# DiscoRap_V11.net
KiCad netlist of a schematic drawn in EAGLE
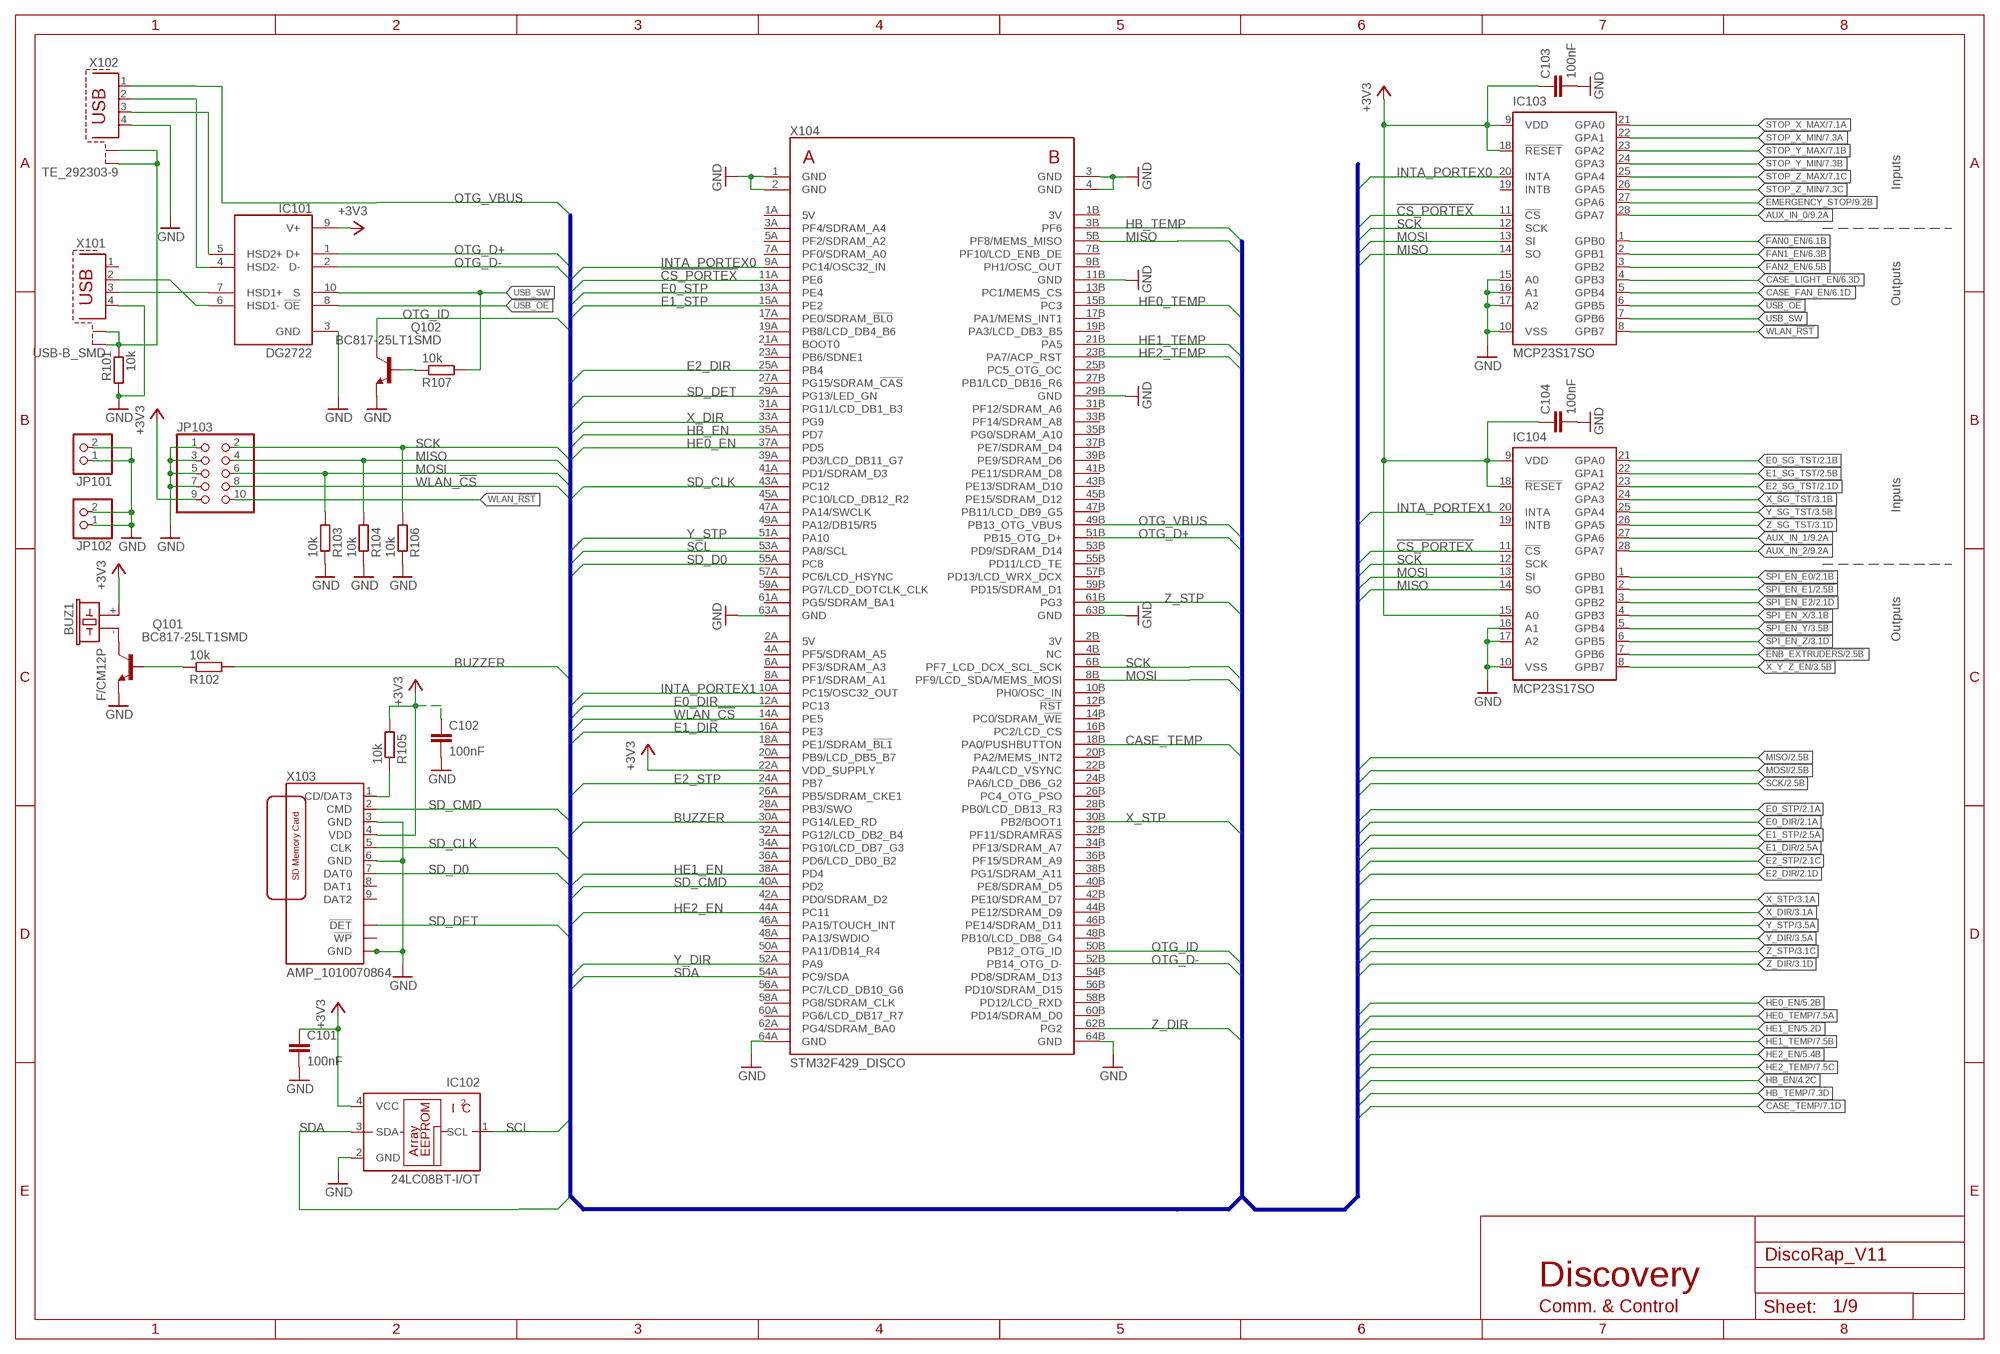
[diagram p0: schematic, sheet 1]
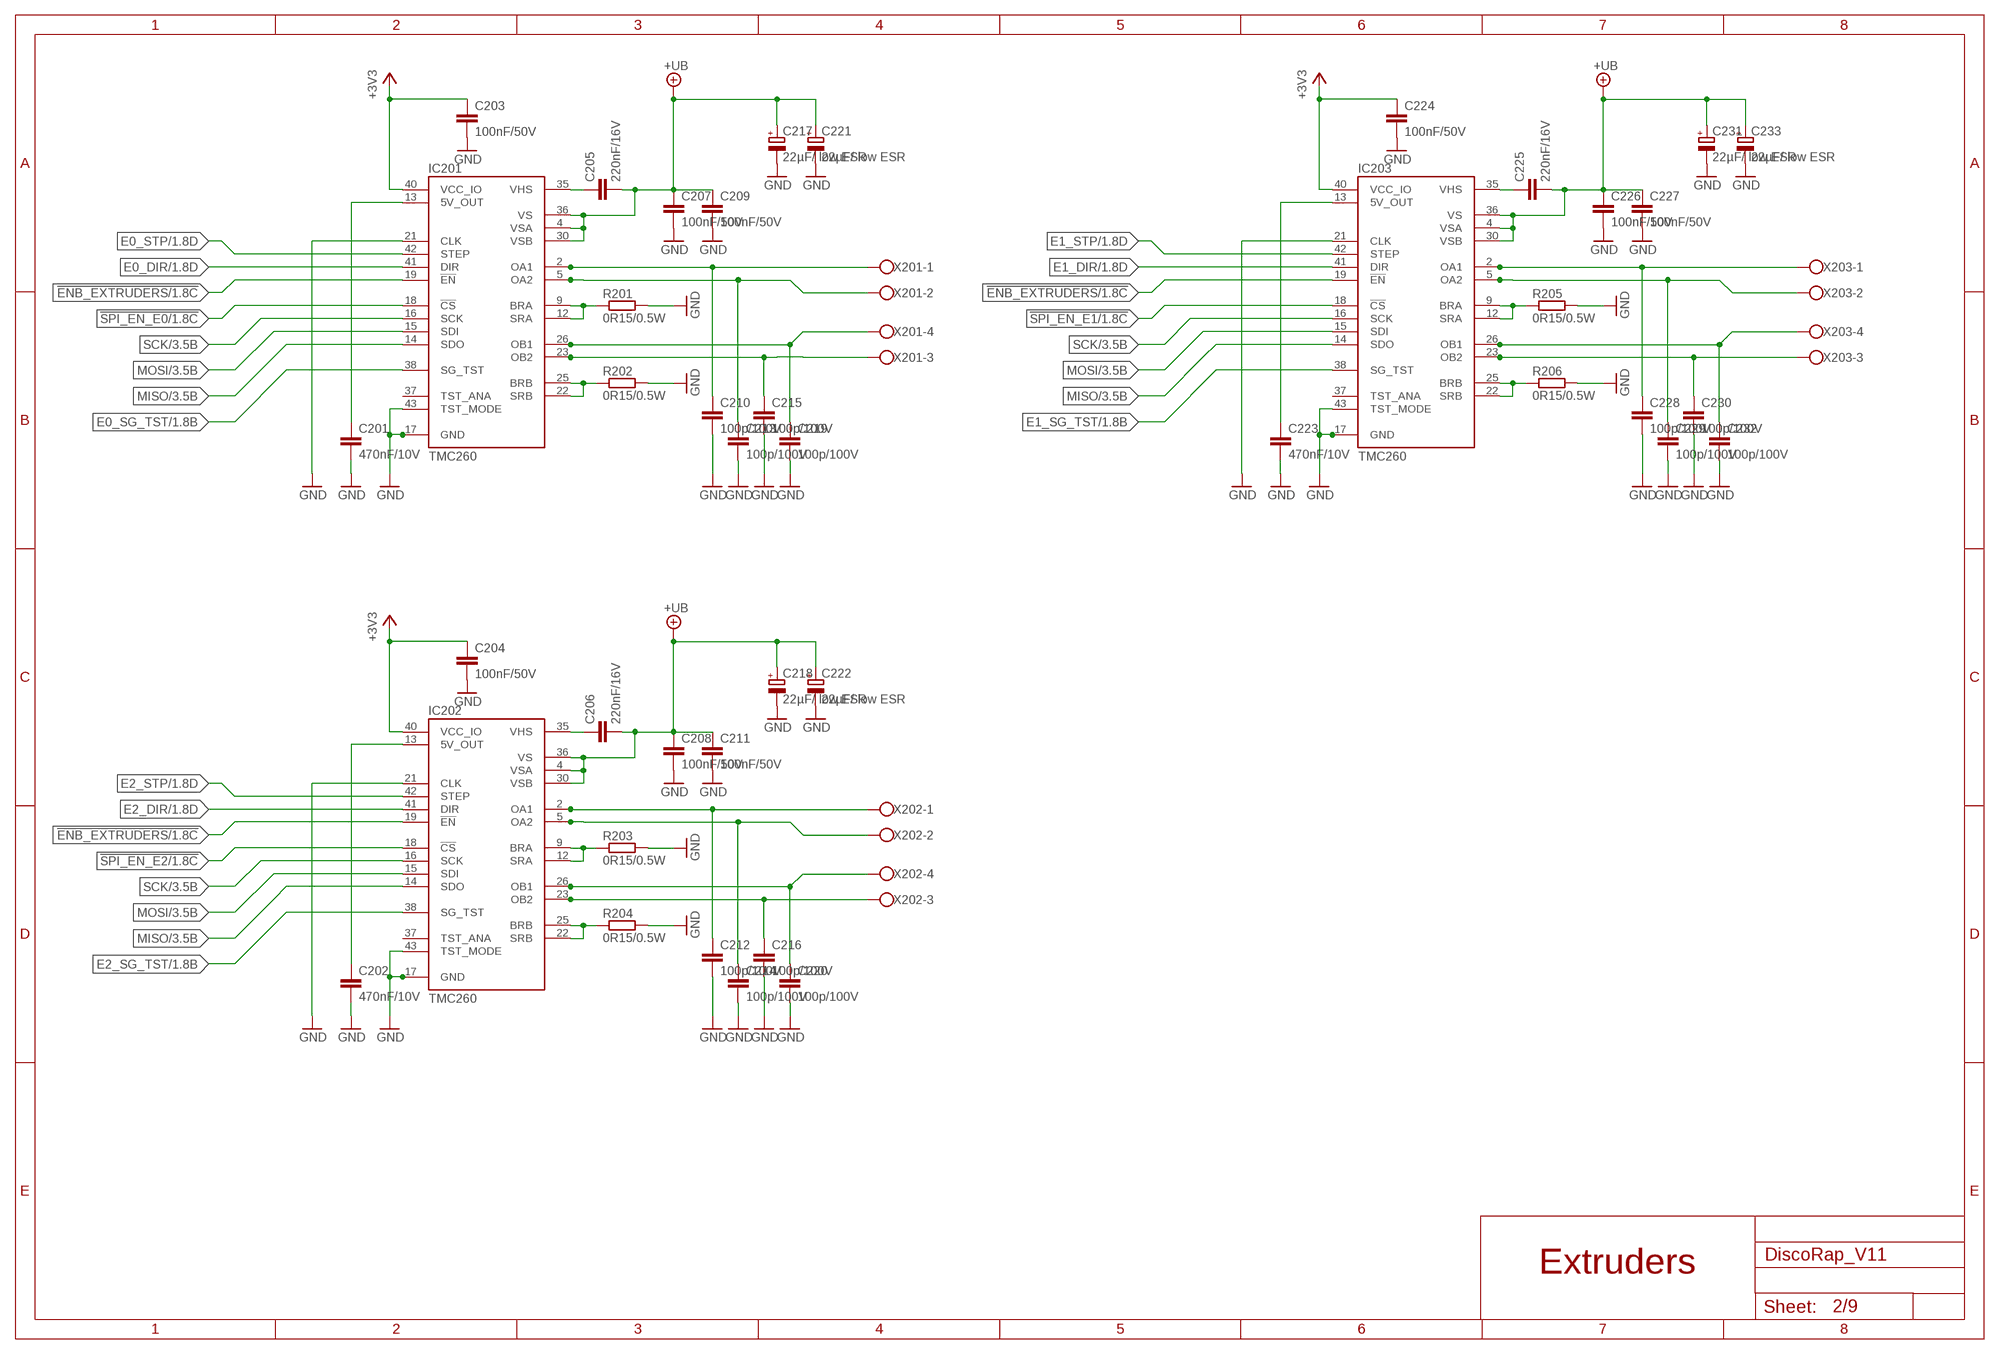
[diagram p1: schematic, sheet 2]
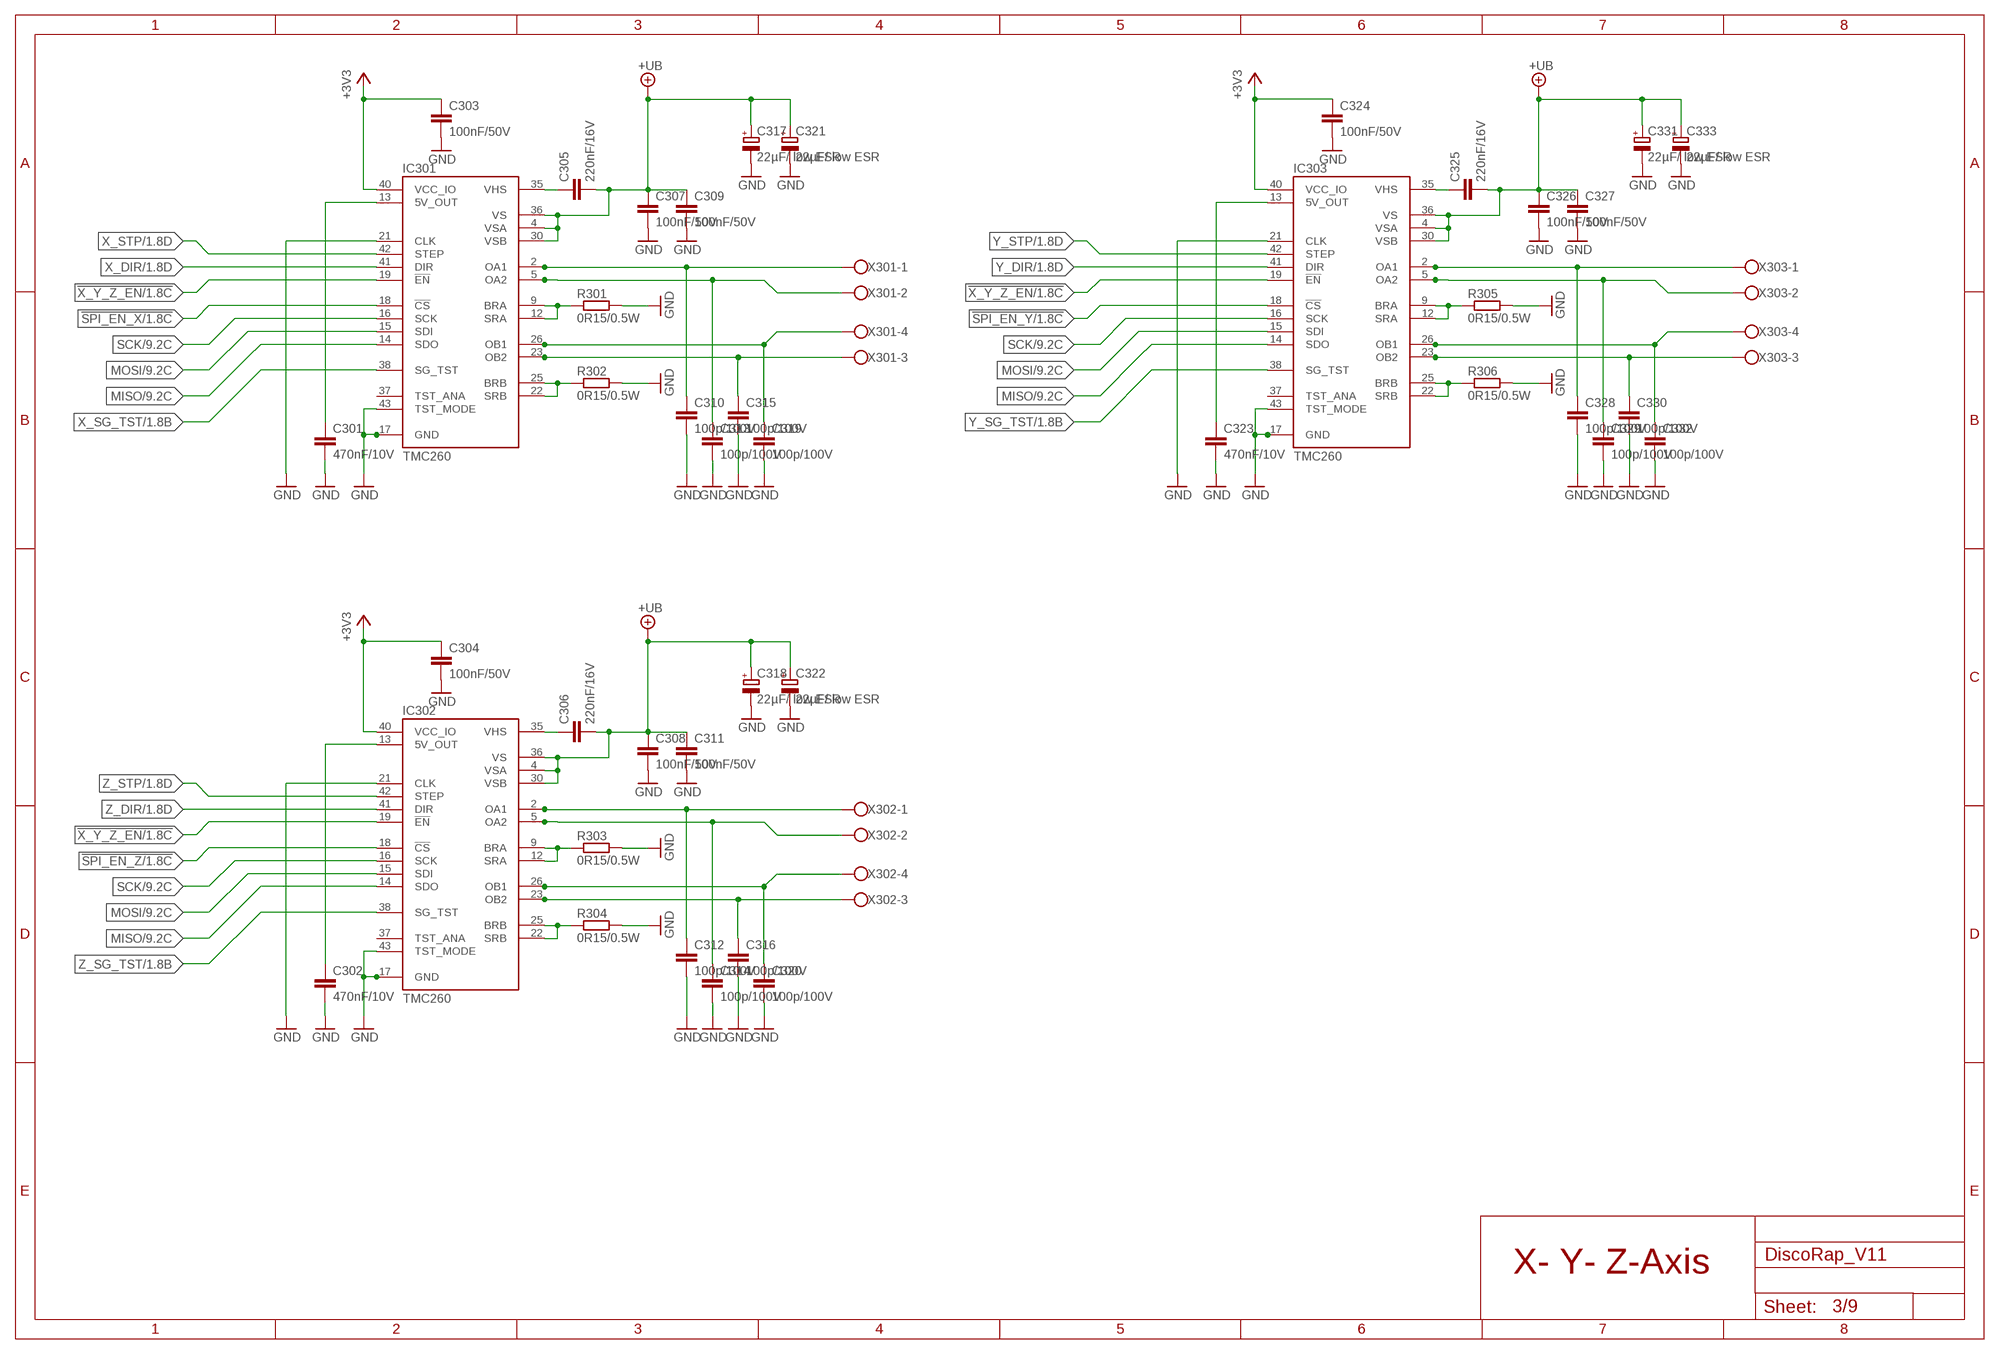
[diagram p2: schematic, sheet 3]
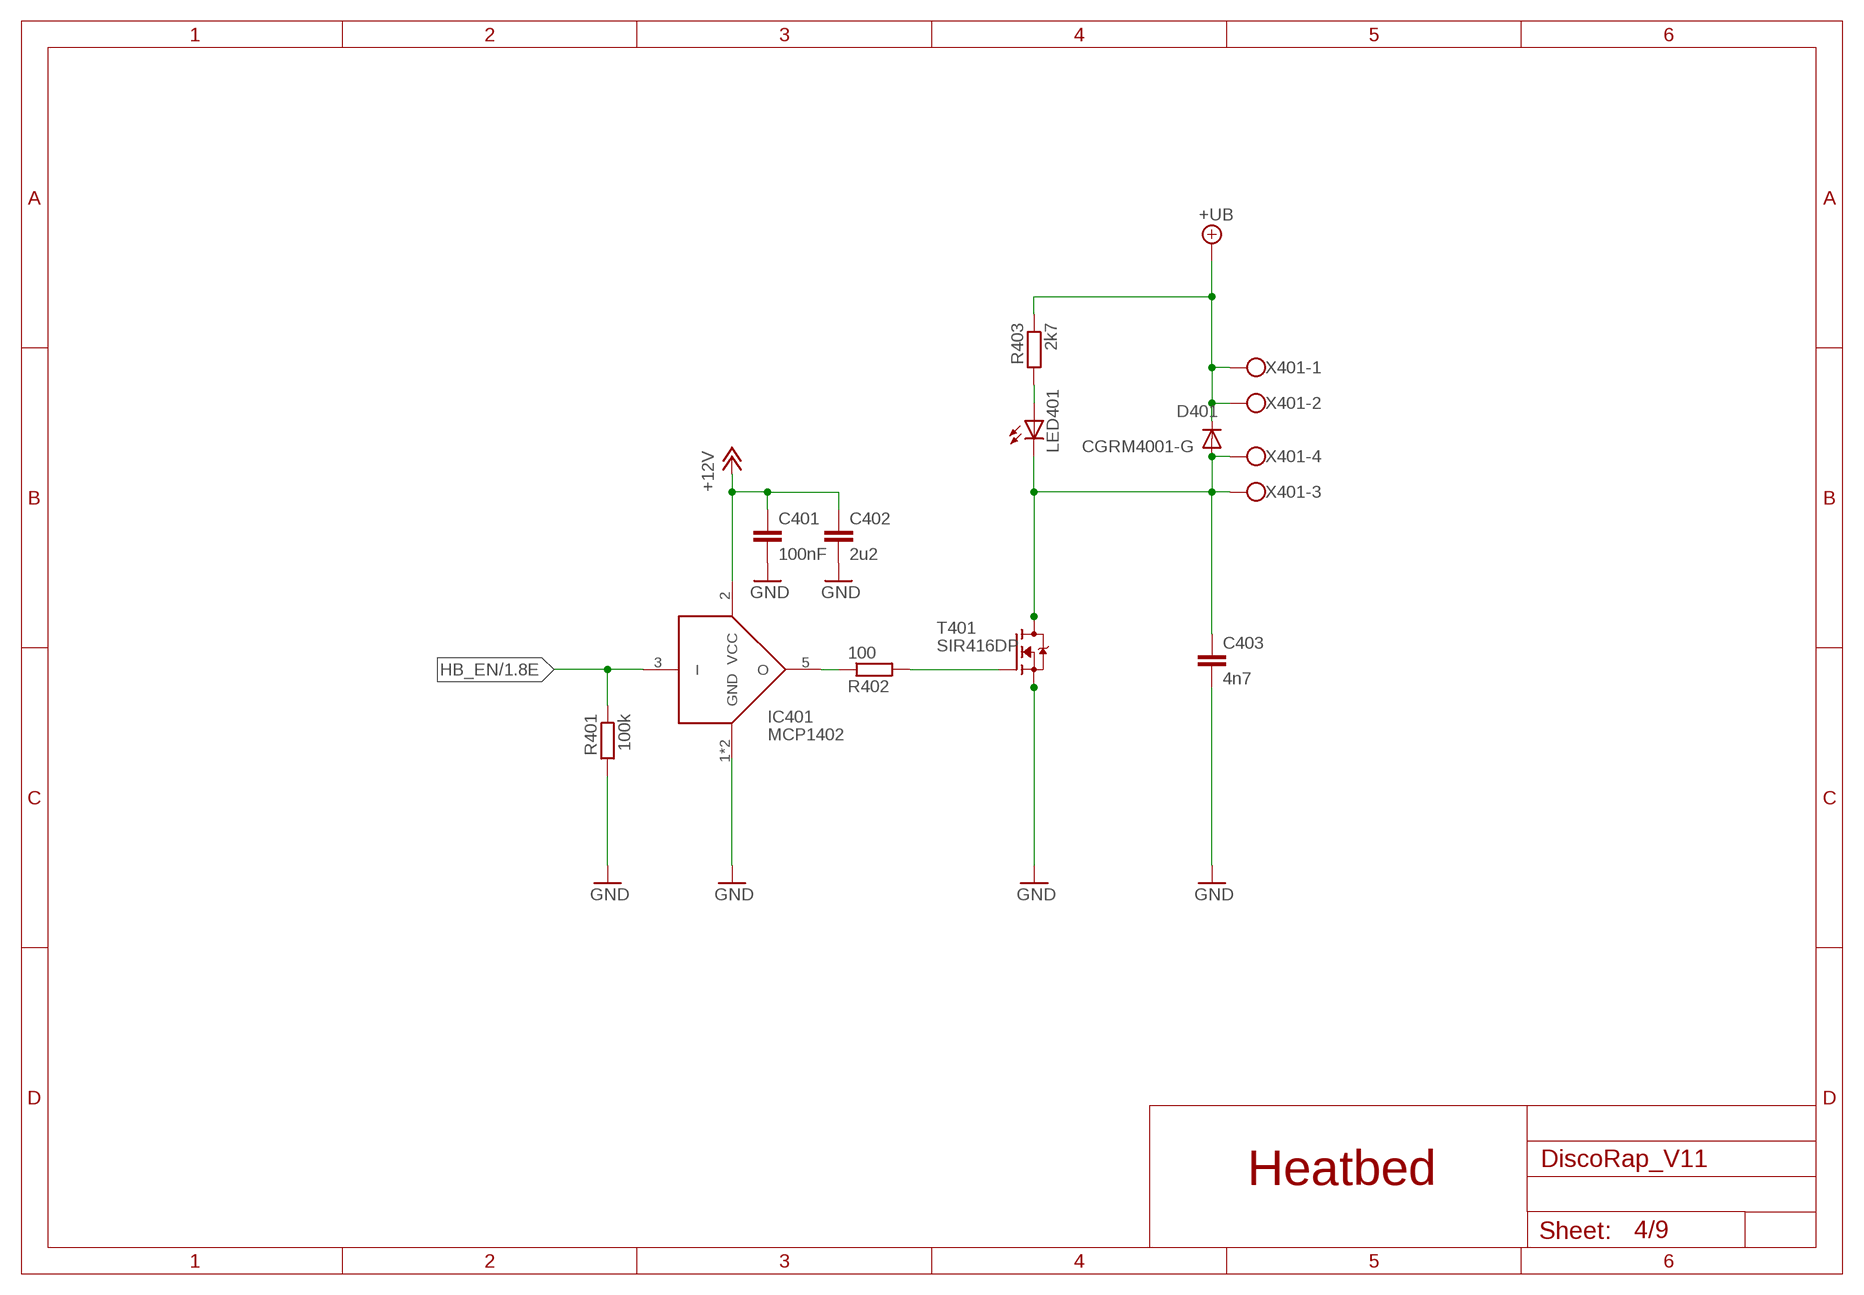
[diagram p3: schematic, sheet 4]
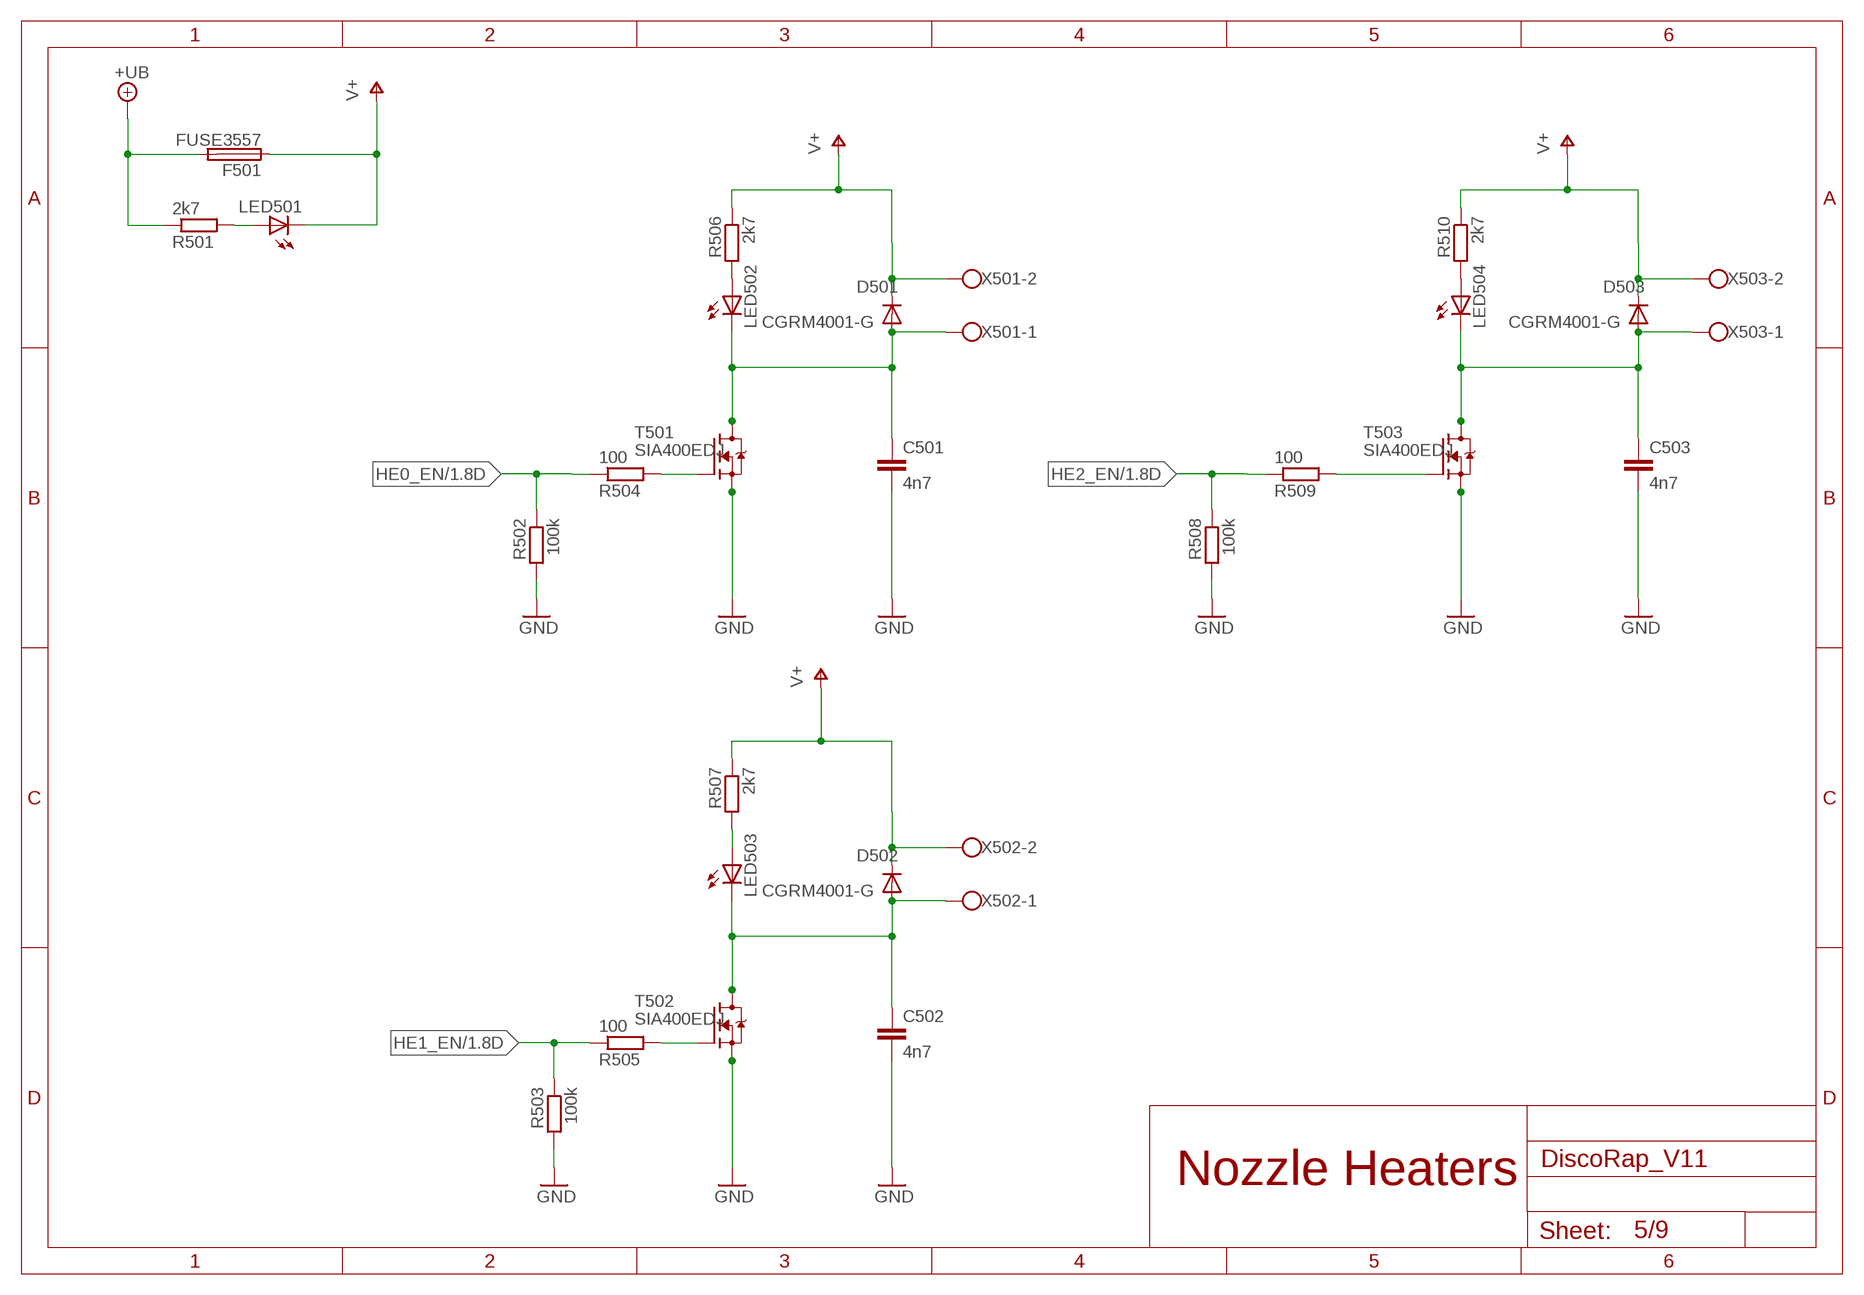
[diagram p4: schematic, sheet 5]
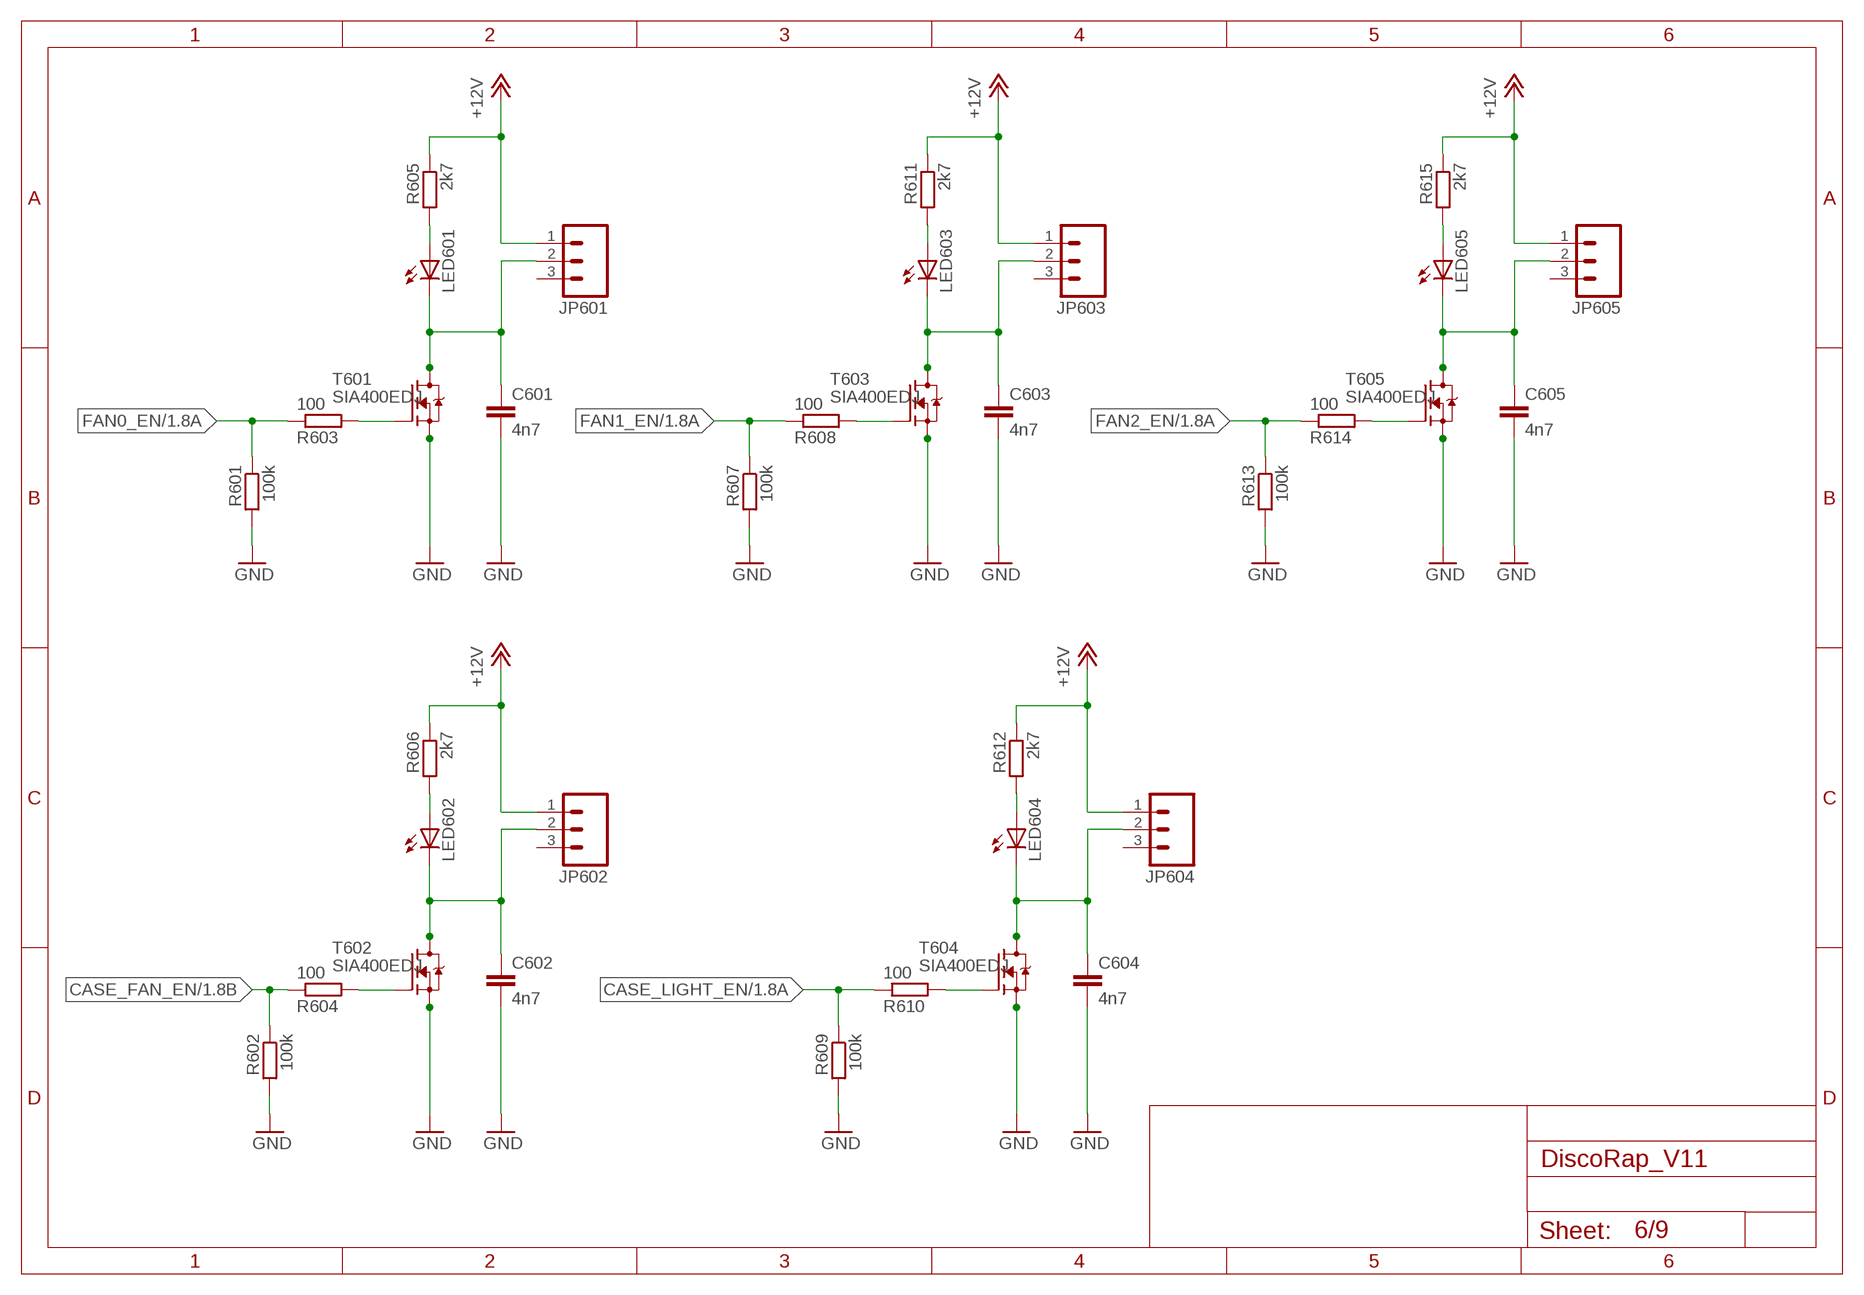
[diagram p5: schematic, sheet 6]
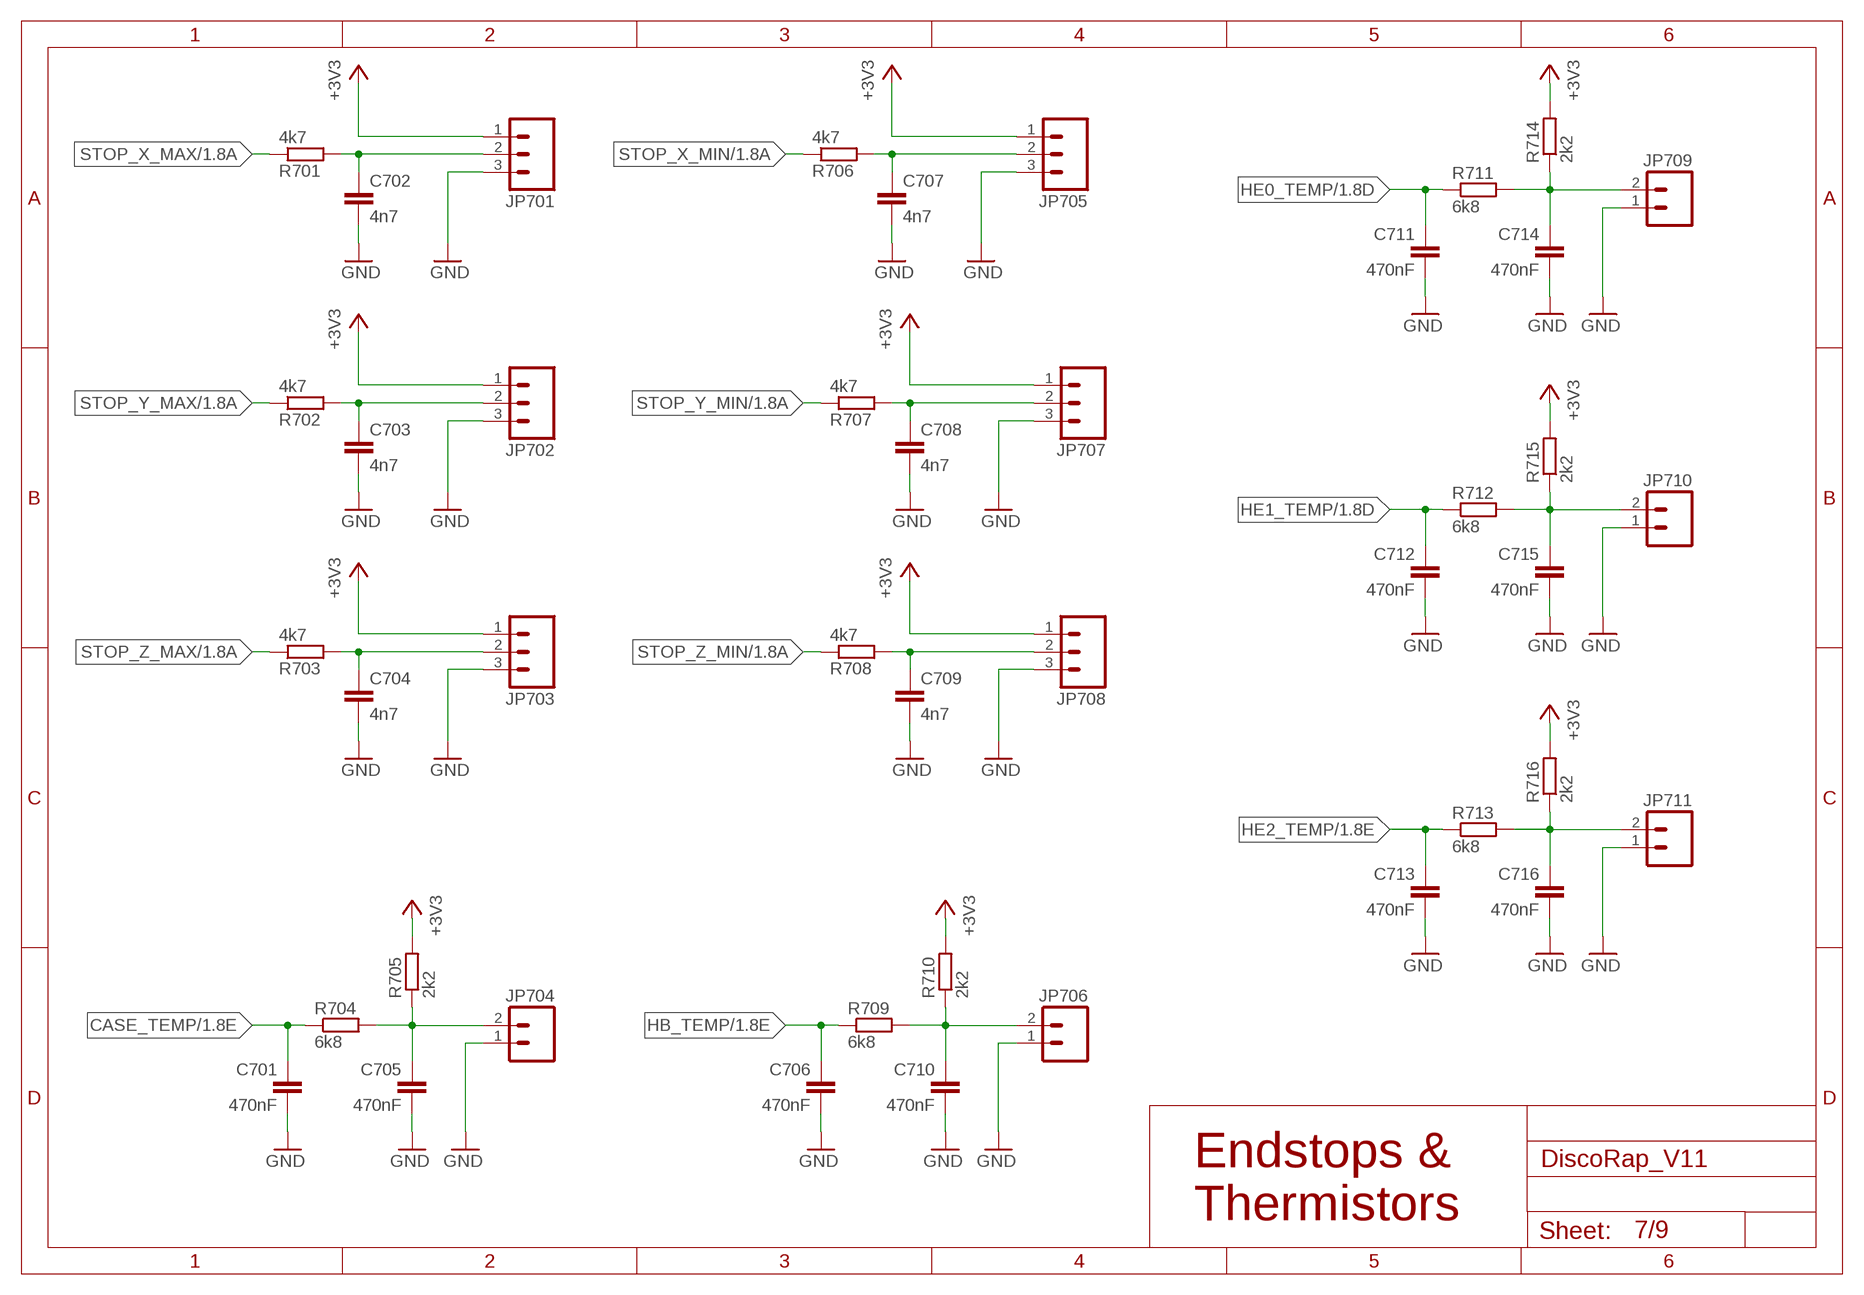
[diagram p6: schematic, sheet 7]
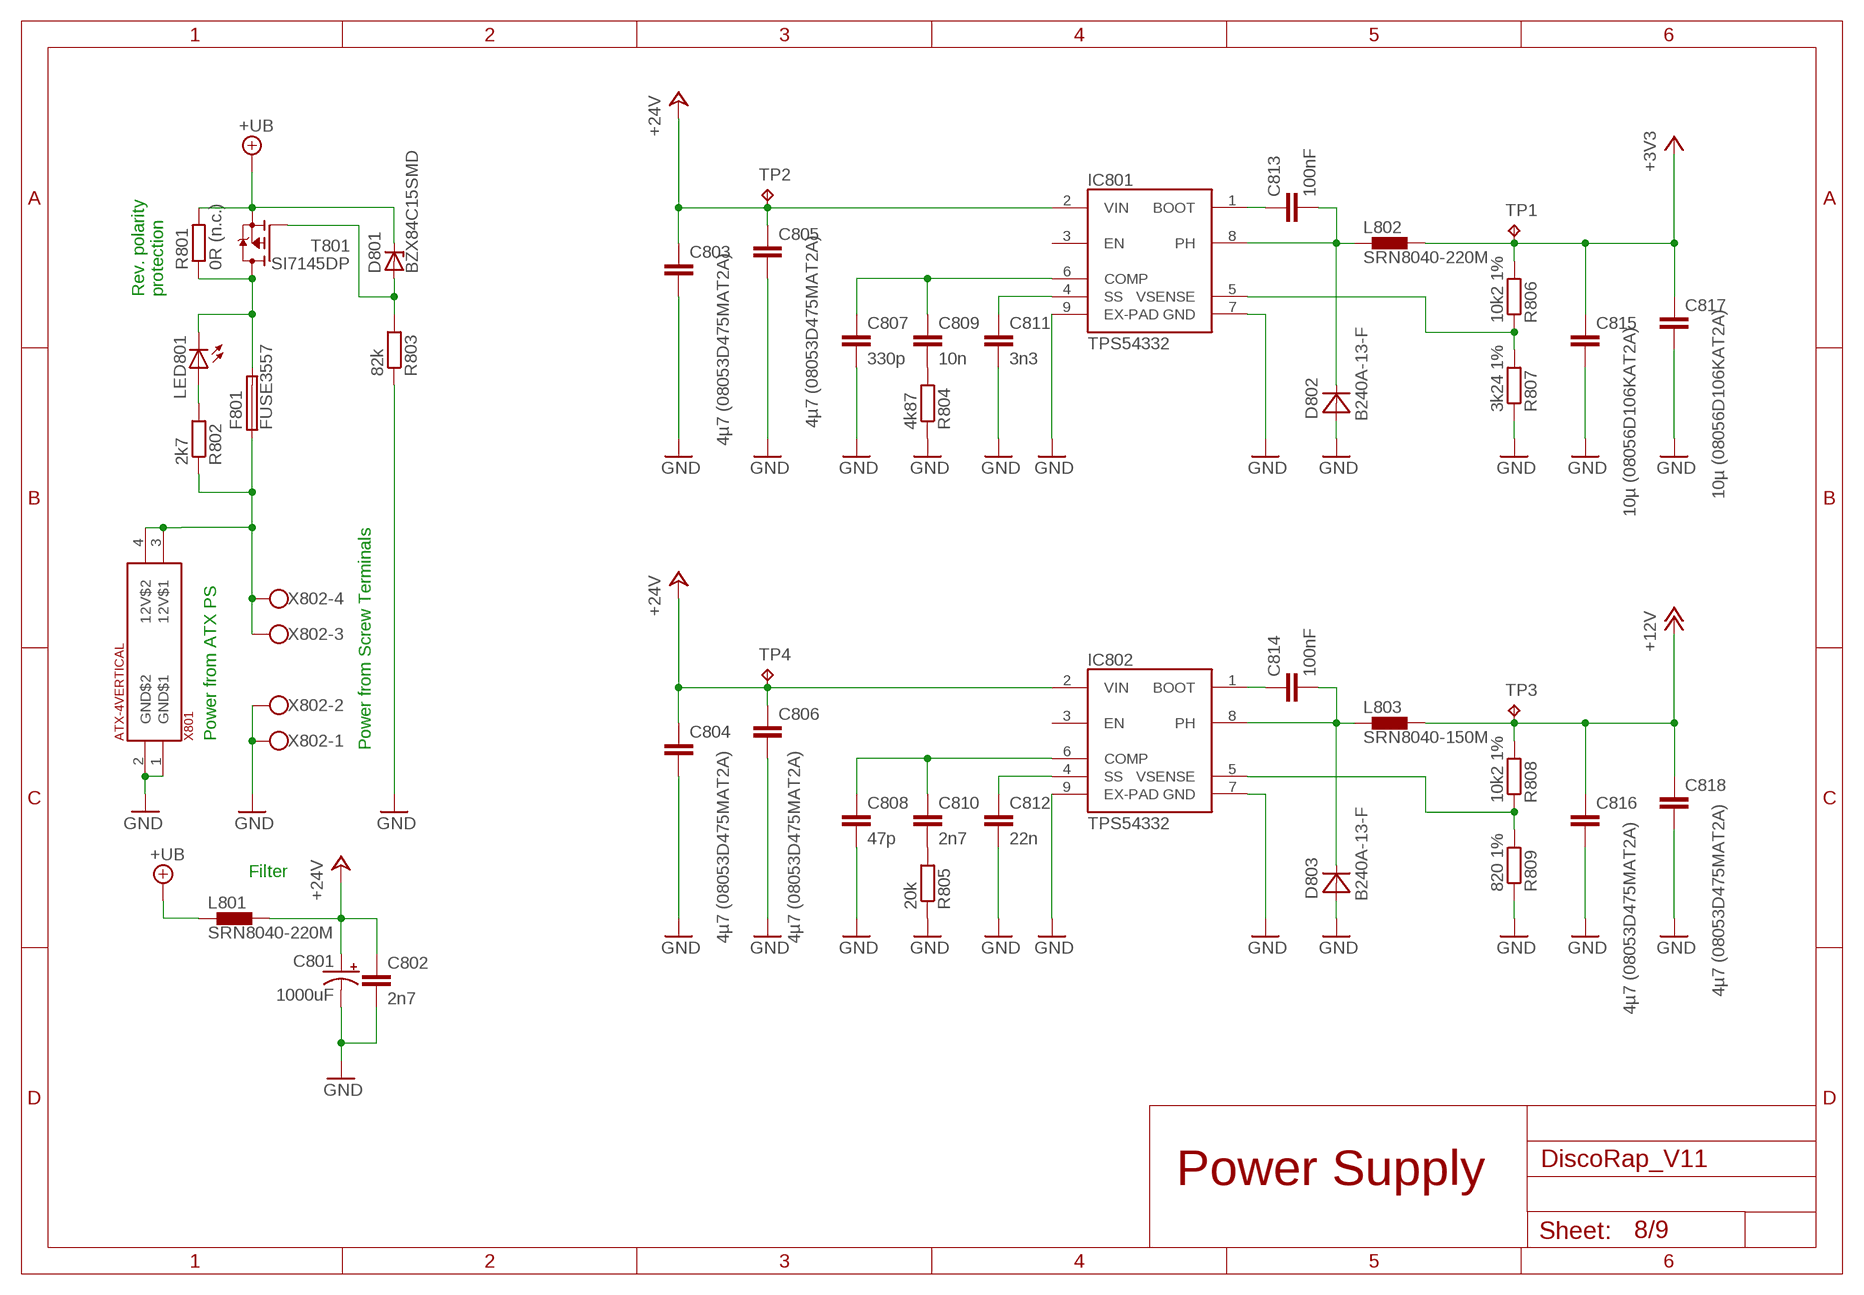
[diagram p7: schematic, sheet 8]
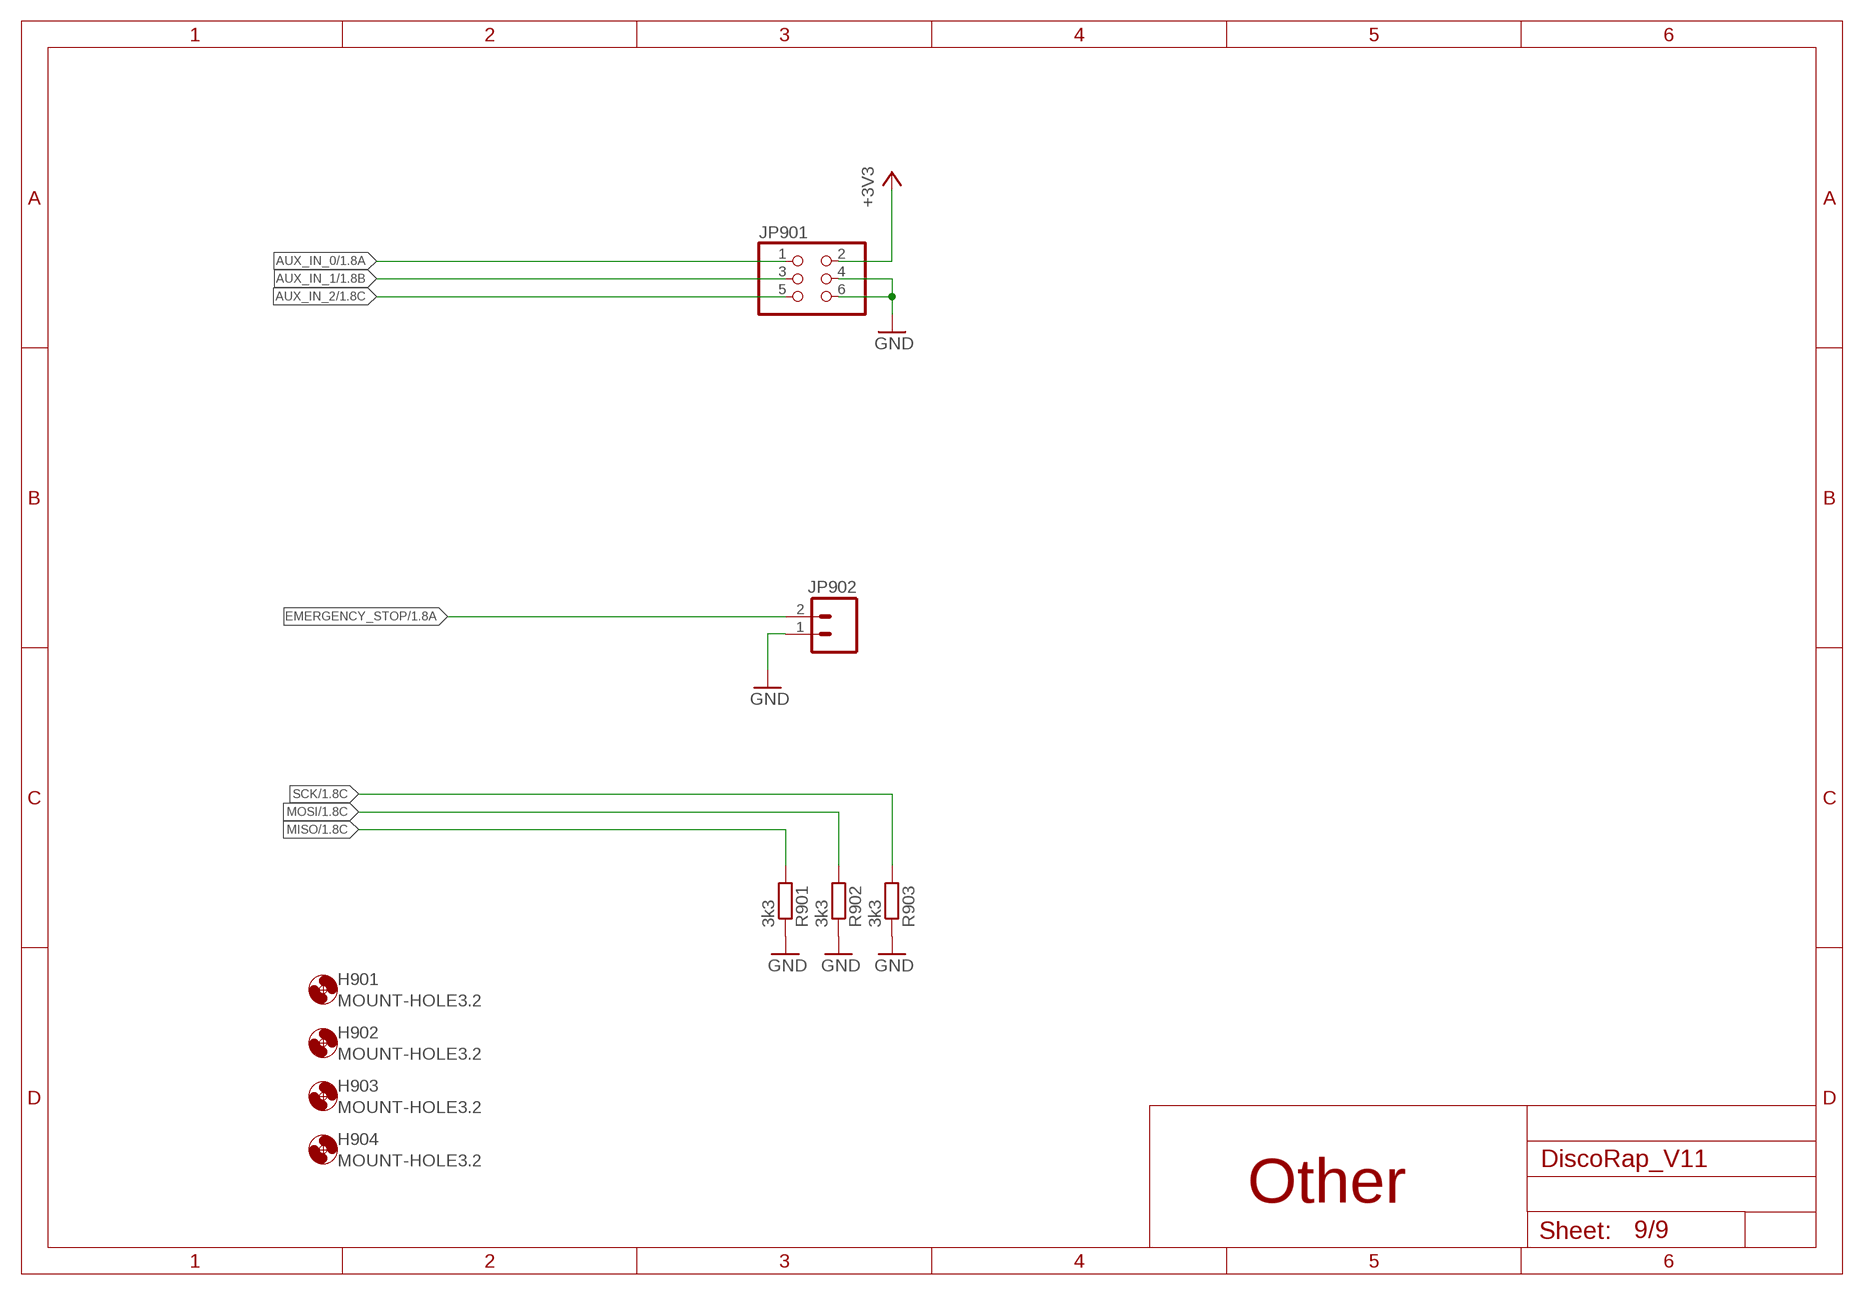
[diagram p8: schematic, sheet 9]

(export (version "E")
  (design (tool "Eeschema 10.0.6"))
  (components
    (comp (ref "H901")
      (value "MOUNT-HOLE3.2")
      (footprint "eagle-import:3,2")
      (libsource (lib "eagle-import") (part "MOUNT-HOLE3.2"))
    )
    (comp (ref "H902")
      (value "MOUNT-HOLE3.2")
      (footprint "eagle-import:3,2")
      (libsource (lib "eagle-import") (part "MOUNT-HOLE3.2"))
    )
    (comp (ref "H903")
      (value "MOUNT-HOLE3.2")
      (footprint "eagle-import:3,2")
      (libsource (lib "eagle-import") (part "MOUNT-HOLE3.2"))
    )
    (comp (ref "H904")
      (value "MOUNT-HOLE3.2")
      (footprint "eagle-import:3,2")
      (libsource (lib "eagle-import") (part "MOUNT-HOLE3.2"))
    )
    (comp (ref "JP901")
      (value "PINHD-2X3")
      (footprint "eagle-import:2X03")
      (libsource (lib "eagle-import") (part "PINHD-2X3"))
    )
    (comp (ref "JP902")
      (value "M02POLAR")
      (footprint "eagle-import:MOLEX-1X2")
      (libsource (lib "eagle-import") (part "M02POLAR"))
    )
    (comp (ref "R901")
      (value "3k3")
      (footprint "eagle-import:0805")
      (libsource (lib "eagle-import") (part "R-EU0805"))
    )
    (comp (ref "R902")
      (value "3k3")
      (footprint "eagle-import:0805")
      (libsource (lib "eagle-import") (part "R-EU0805"))
    )
    (comp (ref "R903")
      (value "3k3")
      (footprint "eagle-import:0805")
      (libsource (lib "eagle-import") (part "R-EU0805"))
    )
    (comp (ref "C301")
      (value "470nF/10V")
      (footprint "eagle-import:0805")
      (libsource (lib "eagle-import") (part "C-EU0805"))
    )
    (comp (ref "C302")
      (value "470nF/10V")
      (footprint "eagle-import:0805")
      (libsource (lib "eagle-import") (part "C-EU0805"))
    )
    (comp (ref "C303")
      (value "100nF/50V")
      (footprint "eagle-import:0805")
      (libsource (lib "eagle-import") (part "C-EU0805"))
    )
    (comp (ref "C304")
      (value "100nF/50V")
      (footprint "eagle-import:0805")
      (libsource (lib "eagle-import") (part "C-EU0805"))
    )
    (comp (ref "C305")
      (value "220nF/16V")
      (footprint "eagle-import:0805")
      (libsource (lib "eagle-import") (part "C-EU0805"))
    )
    (comp (ref "C306")
      (value "220nF/16V")
      (footprint "eagle-import:0805")
      (libsource (lib "eagle-import") (part "C-EU0805"))
    )
    (comp (ref "C307")
      (value "100nF/50V")
      (footprint "eagle-import:0805")
      (libsource (lib "eagle-import") (part "C-EU0805"))
    )
    (comp (ref "C308")
      (value "100nF/50V")
      (footprint "eagle-import:0805")
      (libsource (lib "eagle-import") (part "C-EU0805"))
    )
    (comp (ref "C309")
      (value "100nF/50V")
      (footprint "eagle-import:0805")
      (libsource (lib "eagle-import") (part "C-EU0805"))
    )
    (comp (ref "C310")
      (value "100p/100V")
      (footprint "eagle-import:0805")
      (libsource (lib "eagle-import") (part "C-EU0805"))
    )
    (comp (ref "C311")
      (value "100nF/50V")
      (footprint "eagle-import:0805")
      (libsource (lib "eagle-import") (part "C-EU0805"))
    )
    (comp (ref "C312")
      (value "100p/100V")
      (footprint "eagle-import:0805")
      (libsource (lib "eagle-import") (part "C-EU0805"))
    )
    (comp (ref "C313")
      (value "100p/100V")
      (footprint "eagle-import:0805")
      (libsource (lib "eagle-import") (part "C-EU0805"))
    )
    (comp (ref "C314")
      (value "100p/100V")
      (footprint "eagle-import:0805")
      (libsource (lib "eagle-import") (part "C-EU0805"))
    )
    (comp (ref "C315")
      (value "100p/100V")
      (footprint "eagle-import:0805")
      (libsource (lib "eagle-import") (part "C-EU0805"))
    )
    (comp (ref "C316")
      (value "100p/100V")
      (footprint "eagle-import:0805")
      (libsource (lib "eagle-import") (part "C-EU0805"))
    )
    (comp (ref "C317")
      (value "22µF/ low ESR")
      (footprint "eagle-import:SANYO-OSCON_SMD_B6")
      (libsource (lib "eagle-import") (part "CPOL-EUSANYO_SMD_B6"))
    )
    (comp (ref "C318")
      (value "22µF/ low ESR")
      (footprint "eagle-import:SANYO-OSCON_SMD_B6")
      (libsource (lib "eagle-import") (part "CPOL-EUSANYO_SMD_B6"))
    )
    (comp (ref "C319")
      (value "100p/100V")
      (footprint "eagle-import:0805")
      (libsource (lib "eagle-import") (part "C-EU0805"))
    )
    (comp (ref "C320")
      (value "100p/100V")
      (footprint "eagle-import:0805")
      (libsource (lib "eagle-import") (part "C-EU0805"))
    )
    (comp (ref "C321")
      (value "22µF/ low ESR")
      (footprint "eagle-import:SANYO-OSCON_SMD_B6")
      (libsource (lib "eagle-import") (part "CPOL-EUSANYO_SMD_B6"))
    )
    (comp (ref "C322")
      (value "22µF/ low ESR")
      (footprint "eagle-import:SANYO-OSCON_SMD_B6")
      (libsource (lib "eagle-import") (part "CPOL-EUSANYO_SMD_B6"))
    )
    (comp (ref "C323")
      (value "470nF/10V")
      (footprint "eagle-import:0805")
      (libsource (lib "eagle-import") (part "C-EU0805"))
    )
    (comp (ref "C324")
      (value "100nF/50V")
      (footprint "eagle-import:0805")
      (libsource (lib "eagle-import") (part "C-EU0805"))
    )
    (comp (ref "C325")
      (value "220nF/16V")
      (footprint "eagle-import:0805")
      (libsource (lib "eagle-import") (part "C-EU0805"))
    )
    (comp (ref "C326")
      (value "100nF/50V")
      (footprint "eagle-import:0805")
      (libsource (lib "eagle-import") (part "C-EU0805"))
    )
    (comp (ref "C327")
      (value "100nF/50V")
      (footprint "eagle-import:0805")
      (libsource (lib "eagle-import") (part "C-EU0805"))
    )
    (comp (ref "C328")
      (value "100p/100V")
      (footprint "eagle-import:0805")
      (libsource (lib "eagle-import") (part "C-EU0805"))
    )
    (comp (ref "C329")
      (value "100p/100V")
      (footprint "eagle-import:0805")
      (libsource (lib "eagle-import") (part "C-EU0805"))
    )
    (comp (ref "C330")
      (value "100p/100V")
      (footprint "eagle-import:0805")
      (libsource (lib "eagle-import") (part "C-EU0805"))
    )
    (comp (ref "C331")
      (value "22µF/ low ESR")
      (footprint "eagle-import:SANYO-OSCON_SMD_B6")
      (libsource (lib "eagle-import") (part "CPOL-EUSANYO_SMD_B6"))
    )
    (comp (ref "C332")
      (value "100p/100V")
      (footprint "eagle-import:0805")
      (libsource (lib "eagle-import") (part "C-EU0805"))
    )
    (comp (ref "C333")
      (value "22µF/ low ESR")
      (footprint "eagle-import:SANYO-OSCON_SMD_B6")
      (libsource (lib "eagle-import") (part "CPOL-EUSANYO_SMD_B6"))
    )
    (comp (ref "IC301")
      (value "TMC260")
      (footprint "eagle-import:SQFP-S-10X10-44")
      (libsource (lib "eagle-import") (part "TMC260"))
    )
    (comp (ref "IC302")
      (value "TMC260")
      (footprint "eagle-import:SQFP-S-10X10-44")
      (libsource (lib "eagle-import") (part "TMC260"))
    )
    (comp (ref "IC303")
      (value "TMC260")
      (footprint "eagle-import:SQFP-S-10X10-44")
      (libsource (lib "eagle-import") (part "TMC260"))
    )
    (comp (ref "R301")
      (value "0R15/0.5W")
      (footprint "eagle-import:R1206")
      (libsource (lib "eagle-import") (part "R-EU_R1206"))
    )
    (comp (ref "R302")
      (value "0R15/0.5W")
      (footprint "eagle-import:R1206")
      (libsource (lib "eagle-import") (part "R-EU_R1206"))
    )
    (comp (ref "R303")
      (value "0R15/0.5W")
      (footprint "eagle-import:R1206")
      (libsource (lib "eagle-import") (part "R-EU_R1206"))
    )
    (comp (ref "R304")
      (value "0R15/0.5W")
      (footprint "eagle-import:R1206")
      (libsource (lib "eagle-import") (part "R-EU_R1206"))
    )
    (comp (ref "R305")
      (value "0R15/0.5W")
      (footprint "eagle-import:R1206")
      (libsource (lib "eagle-import") (part "R-EU_R1206"))
    )
    (comp (ref "R306")
      (value "0R15/0.5W")
      (footprint "eagle-import:R1206")
      (libsource (lib "eagle-import") (part "R-EU_R1206"))
    )
    (comp (ref "X301")
      (value "W237-4")
      (footprint "eagle-import:W237-4")
      (libsource (lib "eagle-import") (part "W237-4"))
    )
    (comp (ref "X302")
      (value "W237-4")
      (footprint "eagle-import:W237-4")
      (libsource (lib "eagle-import") (part "W237-4"))
    )
    (comp (ref "X303")
      (value "W237-4")
      (footprint "eagle-import:W237-4")
      (libsource (lib "eagle-import") (part "W237-4"))
    )
    (comp (ref "C701")
      (value "470nF")
      (footprint "eagle-import:0805")
      (libsource (lib "eagle-import") (part "C-EU0805"))
    )
    (comp (ref "C702")
      (value "4n7")
      (footprint "eagle-import:0805")
      (libsource (lib "eagle-import") (part "C-EU0805"))
    )
    (comp (ref "C703")
      (value "4n7")
      (footprint "eagle-import:0805")
      (libsource (lib "eagle-import") (part "C-EU0805"))
    )
    (comp (ref "C704")
      (value "4n7")
      (footprint "eagle-import:0805")
      (libsource (lib "eagle-import") (part "C-EU0805"))
    )
    (comp (ref "C705")
      (value "470nF")
      (footprint "eagle-import:0805")
      (libsource (lib "eagle-import") (part "C-EU0805"))
    )
    (comp (ref "C706")
      (value "470nF")
      (footprint "eagle-import:0805")
      (libsource (lib "eagle-import") (part "C-EU0805"))
    )
    (comp (ref "C707")
      (value "4n7")
      (footprint "eagle-import:0805")
      (libsource (lib "eagle-import") (part "C-EU0805"))
    )
    (comp (ref "C708")
      (value "4n7")
      (footprint "eagle-import:0805")
      (libsource (lib "eagle-import") (part "C-EU0805"))
    )
    (comp (ref "C709")
      (value "4n7")
      (footprint "eagle-import:0805")
      (libsource (lib "eagle-import") (part "C-EU0805"))
    )
    (comp (ref "C710")
      (value "470nF")
      (footprint "eagle-import:0805")
      (libsource (lib "eagle-import") (part "C-EU0805"))
    )
    (comp (ref "C711")
      (value "470nF")
      (footprint "eagle-import:0805")
      (libsource (lib "eagle-import") (part "C-EU0805"))
    )
    (comp (ref "C712")
      (value "470nF")
      (footprint "eagle-import:0805")
      (libsource (lib "eagle-import") (part "C-EU0805"))
    )
    (comp (ref "C713")
      (value "470nF")
      (footprint "eagle-import:0805")
      (libsource (lib "eagle-import") (part "C-EU0805"))
    )
    (comp (ref "C714")
      (value "470nF")
      (footprint "eagle-import:0805")
      (libsource (lib "eagle-import") (part "C-EU0805"))
    )
    (comp (ref "C715")
      (value "470nF")
      (footprint "eagle-import:0805")
      (libsource (lib "eagle-import") (part "C-EU0805"))
    )
    (comp (ref "C716")
      (value "470nF")
      (footprint "eagle-import:0805")
      (libsource (lib "eagle-import") (part "C-EU0805"))
    )
    (comp (ref "JP701")
      (value "M03POLAR")
      (footprint "eagle-import:MOLEX-1X3")
      (libsource (lib "eagle-import") (part "M03POLAR"))
    )
    (comp (ref "JP702")
      (value "M03POLAR")
      (footprint "eagle-import:MOLEX-1X3")
      (libsource (lib "eagle-import") (part "M03POLAR"))
    )
    (comp (ref "JP703")
      (value "M03POLAR")
      (footprint "eagle-import:MOLEX-1X3")
      (libsource (lib "eagle-import") (part "M03POLAR"))
    )
    (comp (ref "JP704")
      (value "M02POLAR")
      (footprint "eagle-import:MOLEX-1X2")
      (libsource (lib "eagle-import") (part "M02POLAR"))
    )
    (comp (ref "JP705")
      (value "M03POLAR")
      (footprint "eagle-import:MOLEX-1X3")
      (libsource (lib "eagle-import") (part "M03POLAR"))
    )
    (comp (ref "JP706")
      (value "M02POLAR")
      (footprint "eagle-import:MOLEX-1X2")
      (libsource (lib "eagle-import") (part "M02POLAR"))
    )
    (comp (ref "JP707")
      (value "M03POLAR")
      (footprint "eagle-import:MOLEX-1X3")
      (libsource (lib "eagle-import") (part "M03POLAR"))
    )
    (comp (ref "JP708")
      (value "M03POLAR")
      (footprint "eagle-import:MOLEX-1X3")
      (libsource (lib "eagle-import") (part "M03POLAR"))
    )
    (comp (ref "JP709")
      (value "M02POLAR")
      (footprint "eagle-import:MOLEX-1X2")
      (libsource (lib "eagle-import") (part "M02POLAR"))
    )
    (comp (ref "JP710")
      (value "M02POLAR")
      (footprint "eagle-import:MOLEX-1X2")
      (libsource (lib "eagle-import") (part "M02POLAR"))
    )
    (comp (ref "JP711")
      (value "M02POLAR")
      (footprint "eagle-import:MOLEX-1X2")
      (libsource (lib "eagle-import") (part "M02POLAR"))
    )
    (comp (ref "R701")
      (value "4k7")
      (footprint "eagle-import:0805")
      (libsource (lib "eagle-import") (part "R-EU0805"))
    )
    (comp (ref "R702")
      (value "4k7")
      (footprint "eagle-import:0805")
      (libsource (lib "eagle-import") (part "R-EU0805"))
    )
    (comp (ref "R703")
      (value "4k7")
      (footprint "eagle-import:0805")
      (libsource (lib "eagle-import") (part "R-EU0805"))
    )
    (comp (ref "R704")
      (value "6k8")
      (footprint "eagle-import:0805")
      (libsource (lib "eagle-import") (part "R-EU0805"))
    )
    (comp (ref "R705")
      (value "2k2")
      (footprint "eagle-import:0805")
      (libsource (lib "eagle-import") (part "R-EU0805"))
    )
    (comp (ref "R706")
      (value "4k7")
      (footprint "eagle-import:0805")
      (libsource (lib "eagle-import") (part "R-EU0805"))
    )
    (comp (ref "R707")
      (value "4k7")
      (footprint "eagle-import:0805")
      (libsource (lib "eagle-import") (part "R-EU0805"))
    )
    (comp (ref "R708")
      (value "4k7")
      (footprint "eagle-import:0805")
      (libsource (lib "eagle-import") (part "R-EU0805"))
    )
    (comp (ref "R709")
      (value "6k8")
      (footprint "eagle-import:0805")
      (libsource (lib "eagle-import") (part "R-EU0805"))
    )
    (comp (ref "R710")
      (value "2k2")
      (footprint "eagle-import:0805")
      (libsource (lib "eagle-import") (part "R-EU0805"))
    )
    (comp (ref "R711")
      (value "6k8")
      (footprint "eagle-import:0805")
      (libsource (lib "eagle-import") (part "R-EU0805"))
    )
    (comp (ref "R712")
      (value "6k8")
      (footprint "eagle-import:0805")
      (libsource (lib "eagle-import") (part "R-EU0805"))
    )
    (comp (ref "R713")
      (value "6k8")
      (footprint "eagle-import:0805")
      (libsource (lib "eagle-import") (part "R-EU0805"))
    )
    (comp (ref "R714")
      (value "2k2")
      (footprint "eagle-import:0805")
      (libsource (lib "eagle-import") (part "R-EU0805"))
    )
    (comp (ref "R715")
      (value "2k2")
      (footprint "eagle-import:0805")
      (libsource (lib "eagle-import") (part "R-EU0805"))
    )
    (comp (ref "R716")
      (value "2k2")
      (footprint "eagle-import:0805")
      (libsource (lib "eagle-import") (part "R-EU0805"))
    )
    (comp (ref "C401")
      (value "100nF")
      (footprint "eagle-import:0805")
      (libsource (lib "eagle-import") (part "C-EU0805"))
    )
    (comp (ref "C402")
      (value "2u2")
      (footprint "eagle-import:0805")
      (libsource (lib "eagle-import") (part "C-EU0805"))
    )
    (comp (ref "C403")
      (value "4n7")
      (footprint "eagle-import:0805")
      (libsource (lib "eagle-import") (part "C-EU0805"))
    )
    (comp (ref "D401")
      (value "CGRM4001-G")
      (footprint "eagle-import:SOD-123_MINI-SMA")
      (libsource (lib "eagle-import") (part "CGRM400-G1"))
    )
    (comp (ref "IC401")
      (value "MCP1402")
      (footprint "eagle-import:SOT23-5L")
      (libsource (lib "eagle-import") (part "MCP1402"))
    )
    (comp (ref "LED401")
      (value "LEDCHIPLED_0805")
      (footprint "eagle-import:CHIPLED_0805")
      (libsource (lib "eagle-import") (part "LEDCHIPLED_0805"))
    )
    (comp (ref "R401")
      (value "100k")
      (footprint "eagle-import:0805")
      (libsource (lib "eagle-import") (part "R-EU0805"))
    )
    (comp (ref "R402")
      (value "100")
      (footprint "eagle-import:0805")
      (libsource (lib "eagle-import") (part "R-EU0805"))
    )
    (comp (ref "R403")
      (value "2k7")
      (footprint "eagle-import:0805")
      (libsource (lib "eagle-import") (part "R-EU0805"))
    )
    (comp (ref "T401")
      (value "SIR416DP")
      (footprint "eagle-import:SO-8_POWERPACK")
      (libsource (lib "eagle-import") (part "SIR416DP"))
    )
    (comp (ref "X401")
      (value "W237-4")
      (footprint "eagle-import:W237-4")
      (libsource (lib "eagle-import") (part "W237-4"))
    )
    (comp (ref "C601")
      (value "4n7")
      (footprint "eagle-import:0805")
      (libsource (lib "eagle-import") (part "C-EU0805"))
    )
    (comp (ref "C602")
      (value "4n7")
      (footprint "eagle-import:0805")
      (libsource (lib "eagle-import") (part "C-EU0805"))
    )
    (comp (ref "C603")
      (value "4n7")
      (footprint "eagle-import:0805")
      (libsource (lib "eagle-import") (part "C-EU0805"))
    )
    (comp (ref "C604")
      (value "4n7")
      (footprint "eagle-import:0805")
      (libsource (lib "eagle-import") (part "C-EU0805"))
    )
    (comp (ref "C605")
      (value "4n7")
      (footprint "eagle-import:0805")
      (libsource (lib "eagle-import") (part "C-EU0805"))
    )
    (comp (ref "JP601")
      (value "M03POLAR")
      (footprint "eagle-import:MOLEX-1X3")
      (libsource (lib "eagle-import") (part "M03POLAR"))
    )
    (comp (ref "JP602")
      (value "M03POLAR")
      (footprint "eagle-import:MOLEX-1X3")
      (libsource (lib "eagle-import") (part "M03POLAR"))
    )
    (comp (ref "JP603")
      (value "M03POLAR")
      (footprint "eagle-import:MOLEX-1X3")
      (libsource (lib "eagle-import") (part "M03POLAR"))
    )
    (comp (ref "JP604")
      (value "M03POLAR")
      (footprint "eagle-import:MOLEX-1X3")
      (libsource (lib "eagle-import") (part "M03POLAR"))
    )
    (comp (ref "JP605")
      (value "M03POLAR")
      (footprint "eagle-import:MOLEX-1X3")
      (libsource (lib "eagle-import") (part "M03POLAR"))
    )
    (comp (ref "LED601")
      (value "LEDCHIPLED_0805")
      (footprint "eagle-import:CHIPLED_0805")
      (libsource (lib "eagle-import") (part "LEDCHIPLED_0805"))
    )
    (comp (ref "LED602")
      (value "LEDCHIPLED_0805")
      (footprint "eagle-import:CHIPLED_0805")
      (libsource (lib "eagle-import") (part "LEDCHIPLED_0805"))
    )
    (comp (ref "LED603")
      (value "LEDCHIPLED_0805")
      (footprint "eagle-import:CHIPLED_0805")
      (libsource (lib "eagle-import") (part "LEDCHIPLED_0805"))
    )
    (comp (ref "LED604")
      (value "LEDCHIPLED_0805")
      (footprint "eagle-import:CHIPLED_0805")
      (libsource (lib "eagle-import") (part "LEDCHIPLED_0805"))
    )
    (comp (ref "LED605")
      (value "LEDCHIPLED_0805")
      (footprint "eagle-import:CHIPLED_0805")
      (libsource (lib "eagle-import") (part "LEDCHIPLED_0805"))
    )
    (comp (ref "R601")
      (value "100k")
      (footprint "eagle-import:0805")
      (libsource (lib "eagle-import") (part "R-EU0805"))
    )
    (comp (ref "R602")
      (value "100k")
      (footprint "eagle-import:0805")
      (libsource (lib "eagle-import") (part "R-EU0805"))
    )
    (comp (ref "R603")
      (value "100")
      (footprint "eagle-import:0805")
      (libsource (lib "eagle-import") (part "R-EU0805"))
    )
    (comp (ref "R604")
      (value "100")
      (footprint "eagle-import:0805")
      (libsource (lib "eagle-import") (part "R-EU0805"))
    )
    (comp (ref "R605")
      (value "2k7")
      (footprint "eagle-import:0805")
      (libsource (lib "eagle-import") (part "R-EU0805"))
    )
    (comp (ref "R606")
      (value "2k7")
      (footprint "eagle-import:0805")
      (libsource (lib "eagle-import") (part "R-EU0805"))
    )
    (comp (ref "R607")
      (value "100k")
      (footprint "eagle-import:0805")
      (libsource (lib "eagle-import") (part "R-EU0805"))
    )
    (comp (ref "R608")
      (value "100")
      (footprint "eagle-import:0805")
      (libsource (lib "eagle-import") (part "R-EU0805"))
    )
    (comp (ref "R609")
      (value "100k")
      (footprint "eagle-import:0805")
      (libsource (lib "eagle-import") (part "R-EU0805"))
    )
    (comp (ref "R610")
      (value "100")
      (footprint "eagle-import:0805")
      (libsource (lib "eagle-import") (part "R-EU0805"))
    )
    (comp (ref "R611")
      (value "2k7")
      (footprint "eagle-import:0805")
      (libsource (lib "eagle-import") (part "R-EU0805"))
    )
    (comp (ref "R612")
      (value "2k7")
      (footprint "eagle-import:0805")
      (libsource (lib "eagle-import") (part "R-EU0805"))
    )
    (comp (ref "R613")
      (value "100k")
      (footprint "eagle-import:0805")
      (libsource (lib "eagle-import") (part "R-EU0805"))
    )
    (comp (ref "R614")
      (value "100")
      (footprint "eagle-import:0805")
      (libsource (lib "eagle-import") (part "R-EU0805"))
    )
    (comp (ref "R615")
      (value "2k7")
      (footprint "eagle-import:0805")
      (libsource (lib "eagle-import") (part "R-EU0805"))
    )
    (comp (ref "T601")
      (value "SIA400EDJ")
      (footprint "eagle-import:SC70-6L")
      (libsource (lib "eagle-import") (part "SIA400EDJ"))
    )
    (comp (ref "T602")
      (value "SIA400EDJ")
      (footprint "eagle-import:SC70-6L")
      (libsource (lib "eagle-import") (part "SIA400EDJ"))
    )
    (comp (ref "T603")
      (value "SIA400EDJ")
      (footprint "eagle-import:SC70-6L")
      (libsource (lib "eagle-import") (part "SIA400EDJ"))
    )
    (comp (ref "T604")
      (value "SIA400EDJ")
      (footprint "eagle-import:SC70-6L")
      (libsource (lib "eagle-import") (part "SIA400EDJ"))
    )
    (comp (ref "T605")
      (value "SIA400EDJ")
      (footprint "eagle-import:SC70-6L")
      (libsource (lib "eagle-import") (part "SIA400EDJ"))
    )
    (comp (ref "C801")
      (value "1000uF")
      (footprint "eagle-import:CPOL-RADIAL-1000UF-25V")
      (libsource (lib "eagle-import") (part "CAP_POLPTH4"))
    )
    (comp (ref "C802")
      (value "2n7")
      (footprint "eagle-import:0805")
      (libsource (lib "eagle-import") (part "C-EU0805"))
    )
    (comp (ref "C803")
      (value "4µ7 (08053D475MAT2A)")
      (footprint "eagle-import:0805")
      (libsource (lib "eagle-import") (part "C-EU0805"))
    )
    (comp (ref "C804")
      (value "4µ7 (08053D475MAT2A)")
      (footprint "eagle-import:0805")
      (libsource (lib "eagle-import") (part "C-EU0805"))
    )
    (comp (ref "C805")
      (value "4µ7 (08053D475MAT2A)")
      (footprint "eagle-import:0805")
      (libsource (lib "eagle-import") (part "C-EU0805"))
    )
    (comp (ref "C806")
      (value "4µ7 (08053D475MAT2A)")
      (footprint "eagle-import:0805")
      (libsource (lib "eagle-import") (part "C-EU0805"))
    )
    (comp (ref "C807")
      (value "330p")
      (footprint "eagle-import:0805")
      (libsource (lib "eagle-import") (part "C-EU0805"))
    )
    (comp (ref "C808")
      (value "47p")
      (footprint "eagle-import:0805")
      (libsource (lib "eagle-import") (part "C-EU0805"))
    )
    (comp (ref "C809")
      (value "10n")
      (footprint "eagle-import:0805")
      (libsource (lib "eagle-import") (part "C-EU0805"))
    )
    (comp (ref "C810")
      (value "2n7")
      (footprint "eagle-import:0805")
      (libsource (lib "eagle-import") (part "C-EU0805"))
    )
    (comp (ref "C811")
      (value "3n3")
      (footprint "eagle-import:0805")
      (libsource (lib "eagle-import") (part "C-EU0805"))
    )
    (comp (ref "C812")
      (value "22n")
      (footprint "eagle-import:0805")
      (libsource (lib "eagle-import") (part "C-EU0805"))
    )
    (comp (ref "C813")
      (value "100nF")
      (footprint "eagle-import:0805")
      (libsource (lib "eagle-import") (part "C-EU0805"))
    )
    (comp (ref "C814")
      (value "100nF")
      (footprint "eagle-import:0805")
      (libsource (lib "eagle-import") (part "C-EU0805"))
    )
    (comp (ref "C815")
      (value "10µ (08056D106KAT2A)")
      (footprint "eagle-import:0805")
      (libsource (lib "eagle-import") (part "C-EU0805"))
    )
    (comp (ref "C816")
      (value "4µ7 (08053D475MAT2A)")
      (footprint "eagle-import:0805")
      (libsource (lib "eagle-import") (part "C-EU0805"))
    )
    (comp (ref "C817")
      (value "10µ (08056D106KAT2A)")
      (footprint "eagle-import:0805")
      (libsource (lib "eagle-import") (part "C-EU0805"))
    )
    (comp (ref "C818")
      (value "4µ7 (08053D475MAT2A)")
      (footprint "eagle-import:0805")
      (libsource (lib "eagle-import") (part "C-EU0805"))
    )
    (comp (ref "D801")
      (value "BZX84C15SMD")
      (footprint "eagle-import:TO236")
      (libsource (lib "eagle-import") (part "BZX84CSMD"))
    )
    (comp (ref "D802")
      (value "B240A-13-F")
      (footprint "eagle-import:SMA")
      (libsource (lib "eagle-import") (part "MBRA340T3"))
    )
    (comp (ref "D803")
      (value "B240A-13-F")
      (footprint "eagle-import:SMA")
      (libsource (lib "eagle-import") (part "MBRA340T3"))
    )
    (comp (ref "F801")
      (value "FUSE3557")
      (footprint "eagle-import:3557")
      (libsource (lib "eagle-import") (part "FUSE3557"))
    )
    (comp (ref "IC801")
      (value "TPS54332")
      (footprint "eagle-import:PDSO-G8")
      (libsource (lib "eagle-import") (part "TPS54332"))
    )
    (comp (ref "IC802")
      (value "TPS54332")
      (footprint "eagle-import:PDSO-G8")
      (libsource (lib "eagle-import") (part "TPS54332"))
    )
    (comp (ref "L801")
      (value "SRN8040-220M")
      (footprint "eagle-import:SRN8040")
      (libsource (lib "eagle-import") (part "SRN8040"))
    )
    (comp (ref "L802")
      (value "SRN8040-220M")
      (footprint "eagle-import:SRN8040")
      (libsource (lib "eagle-import") (part "SRN8040"))
    )
    (comp (ref "L803")
      (value "SRN8040-150M")
      (footprint "eagle-import:SRN8040")
      (libsource (lib "eagle-import") (part "SRN8040"))
    )
    (comp (ref "LED801")
      (value "LEDCHIPLED_0805")
      (footprint "eagle-import:CHIPLED_0805")
      (libsource (lib "eagle-import") (part "LEDCHIPLED_0805"))
    )
    (comp (ref "R801")
      (value "0R (n.c.)")
      (footprint "eagle-import:R2512")
      (libsource (lib "eagle-import") (part "R-EU_R2512"))
    )
    (comp (ref "R802")
      (value "2k7")
      (footprint "eagle-import:0805")
      (libsource (lib "eagle-import") (part "R-EU0805"))
    )
    (comp (ref "R803")
      (value "82k")
      (footprint "eagle-import:0805")
      (libsource (lib "eagle-import") (part "R-EU0805"))
    )
    (comp (ref "R804")
      (value "4k87")
      (footprint "eagle-import:0805")
      (libsource (lib "eagle-import") (part "R-EU0805"))
    )
    (comp (ref "R805")
      (value "20k")
      (footprint "eagle-import:0805")
      (libsource (lib "eagle-import") (part "R-EU0805"))
    )
    (comp (ref "R806")
      (value "10k2 1%")
      (footprint "eagle-import:0805")
      (libsource (lib "eagle-import") (part "R-EU0805"))
    )
    (comp (ref "R807")
      (value "3k24 1%")
      (footprint "eagle-import:0805")
      (libsource (lib "eagle-import") (part "R-EU0805"))
    )
    (comp (ref "R808")
      (value "10k2 1%")
      (footprint "eagle-import:0805")
      (libsource (lib "eagle-import") (part "R-EU0805"))
    )
    (comp (ref "R809")
      (value "820 1%")
      (footprint "eagle-import:0805")
      (libsource (lib "eagle-import") (part "R-EU0805"))
    )
    (comp (ref "T801")
      (value "SI7145DP")
      (footprint "eagle-import:SO-8_POWERPACK")
      (libsource (lib "eagle-import") (part "SI7145DP"))
    )
    (comp (ref "TP1")
      (value "TPB1,27")
      (footprint "eagle-import:B1,27")
      (libsource (lib "eagle-import") (part "TPB1,27"))
    )
    (comp (ref "TP2")
      (value "TPB1,27")
      (footprint "eagle-import:B1,27")
      (libsource (lib "eagle-import") (part "TPB1,27"))
    )
    (comp (ref "TP3")
      (value "TPB1,27")
      (footprint "eagle-import:B1,27")
      (libsource (lib "eagle-import") (part "TPB1,27"))
    )
    (comp (ref "TP4")
      (value "TPB1,27")
      (footprint "eagle-import:B1,27")
      (libsource (lib "eagle-import") (part "TPB1,27"))
    )
    (comp (ref "X801")
      (value "ATX-4VERTICAL")
      (footprint "eagle-import:MINIFITJR-4-VERTICAL")
      (libsource (lib "eagle-import") (part "ATX-4VERTICAL"))
    )
    (comp (ref "X802")
      (value "W237-4")
      (footprint "eagle-import:W237-4")
      (libsource (lib "eagle-import") (part "W237-4"))
    )
    (comp (ref "BUZ1")
      (value "F/CM12P")
      (footprint "eagle-import:F_CM12P")
      (libsource (lib "eagle-import") (part "F/CM12P"))
    )
    (comp (ref "C101")
      (value "100nF")
      (footprint "eagle-import:0805")
      (libsource (lib "eagle-import") (part "C-EU0805"))
    )
    (comp (ref "C102")
      (value "100nF")
      (footprint "eagle-import:0805")
      (libsource (lib "eagle-import") (part "C-EU0805"))
    )
    (comp (ref "C103")
      (value "100nF")
      (footprint "eagle-import:0805")
      (libsource (lib "eagle-import") (part "C-EU0805"))
    )
    (comp (ref "C104")
      (value "100nF")
      (footprint "eagle-import:0805")
      (libsource (lib "eagle-import") (part "C-EU0805"))
    )
    (comp (ref "IC101")
      (value "DG2722")
      (footprint "eagle-import:MINI_QFN_10L")
      (libsource (lib "eagle-import") (part "DG2722"))
    )
    (comp (ref "IC102")
      (value "24LC08BT-I/OT")
      (footprint "eagle-import:SOT23-5L")
      (fields (field (name "MF") "MICROCHIP") (field (name "MPN") "24LC00T-I/OT"))
      (libsource (lib "eagle-import") (part "2400OTLC"))
    )
    (comp (ref "IC103")
      (value "MCP23S17SO")
      (footprint "eagle-import:SO28W")
      (fields (field (name "MF") "MICROCHIP") (field (name "MPN") "MCP23S17-E/SO"))
      (libsource (lib "eagle-import") (part "MCP23S17SO"))
    )
    (comp (ref "IC104")
      (value "MCP23S17SO")
      (footprint "eagle-import:SO28W")
      (fields (field (name "MF") "MICROCHIP") (field (name "MPN") "MCP23S17-E/SO"))
      (libsource (lib "eagle-import") (part "MCP23S17SO"))
    )
    (comp (ref "JP101")
      (value "PINHD-1X2")
      (footprint "eagle-import:1X02")
      (libsource (lib "eagle-import") (part "PINHD-1X2"))
    )
    (comp (ref "JP102")
      (value "PINHD-1X2")
      (footprint "eagle-import:1X02")
      (libsource (lib "eagle-import") (part "PINHD-1X2"))
    )
    (comp (ref "JP103")
      (value "PINHD-2X5")
      (footprint "eagle-import:2X05")
      (libsource (lib "eagle-import") (part "PINHD-2X5"))
    )
    (comp (ref "Q101")
      (value "BC817-25LT1SMD")
      (footprint "eagle-import:SOT23-BEC")
      (libsource (lib "eagle-import") (part "BC817SMD-25LT1"))
    )
    (comp (ref "Q102")
      (value "BC817-25LT1SMD")
      (footprint "eagle-import:SOT23-BEC")
      (libsource (lib "eagle-import") (part "BC817SMD-25LT1"))
    )
    (comp (ref "R101")
      (value "10k")
      (footprint "eagle-import:0805")
      (libsource (lib "eagle-import") (part "R-EU0805"))
    )
    (comp (ref "R102")
      (value "10k")
      (footprint "eagle-import:0805")
      (libsource (lib "eagle-import") (part "R-EU0805"))
    )
    (comp (ref "R103")
      (value "10k")
      (footprint "eagle-import:0805")
      (libsource (lib "eagle-import") (part "R-EU0805"))
    )
    (comp (ref "R104")
      (value "10k")
      (footprint "eagle-import:0805")
      (libsource (lib "eagle-import") (part "R-EU0805"))
    )
    (comp (ref "R105")
      (value "10k")
      (footprint "eagle-import:0805")
      (libsource (lib "eagle-import") (part "R-EU0805"))
    )
    (comp (ref "R106")
      (value "10k")
      (footprint "eagle-import:0805")
      (libsource (lib "eagle-import") (part "R-EU0805"))
    )
    (comp (ref "R107")
      (value "10k")
      (footprint "eagle-import:0805")
      (libsource (lib "eagle-import") (part "R-EU0805"))
    )
    (comp (ref "X101")
      (value "USB-B_SMD")
      (footprint "eagle-import:USB_B_SMD")
      (libsource (lib "eagle-import") (part "USB-B_SMD"))
    )
    (comp (ref "X102")
      (value "TE_292303-9")
      (footprint "eagle-import:TE_USB_A_SMD")
      (libsource (lib "eagle-import") (part "TE_292303-9"))
    )
    (comp (ref "X103")
      (value "AMP_1010070864")
      (footprint "eagle-import:AMP_1010070864")
      (libsource (lib "eagle-import") (part "AMP_1010070864"))
    )
    (comp (ref "X104")
      (value "STM32F429_DISCO")
      (footprint "eagle-import:STM429_DISCOVERY")
      (libsource (lib "eagle-import") (part "STM32F429_DISCO"))
    )
    (comp (ref "C501")
      (value "4n7")
      (footprint "eagle-import:0805")
      (libsource (lib "eagle-import") (part "C-EU0805"))
    )
    (comp (ref "C502")
      (value "4n7")
      (footprint "eagle-import:0805")
      (libsource (lib "eagle-import") (part "C-EU0805"))
    )
    (comp (ref "C503")
      (value "4n7")
      (footprint "eagle-import:0805")
      (libsource (lib "eagle-import") (part "C-EU0805"))
    )
    (comp (ref "D501")
      (value "CGRM4001-G")
      (footprint "eagle-import:SOD-123_MINI-SMA")
      (libsource (lib "eagle-import") (part "CGRM400-G1"))
    )
    (comp (ref "D502")
      (value "CGRM4001-G")
      (footprint "eagle-import:SOD-123_MINI-SMA")
      (libsource (lib "eagle-import") (part "CGRM400-G1"))
    )
    (comp (ref "D503")
      (value "CGRM4001-G")
      (footprint "eagle-import:SOD-123_MINI-SMA")
      (libsource (lib "eagle-import") (part "CGRM400-G1"))
    )
    (comp (ref "F501")
      (value "FUSE3557")
      (footprint "eagle-import:3557")
      (libsource (lib "eagle-import") (part "FUSE3557"))
    )
    (comp (ref "LED501")
      (value "LEDCHIPLED_0805")
      (footprint "eagle-import:CHIPLED_0805")
      (libsource (lib "eagle-import") (part "LEDCHIPLED_0805"))
    )
    (comp (ref "LED502")
      (value "LEDCHIPLED_0805")
      (footprint "eagle-import:CHIPLED_0805")
      (libsource (lib "eagle-import") (part "LEDCHIPLED_0805"))
    )
    (comp (ref "LED503")
      (value "LEDCHIPLED_0805")
      (footprint "eagle-import:CHIPLED_0805")
      (libsource (lib "eagle-import") (part "LEDCHIPLED_0805"))
    )
    (comp (ref "LED504")
      (value "LEDCHIPLED_0805")
      (footprint "eagle-import:CHIPLED_0805")
      (libsource (lib "eagle-import") (part "LEDCHIPLED_0805"))
    )
    (comp (ref "R501")
      (value "2k7")
      (footprint "eagle-import:0805")
      (libsource (lib "eagle-import") (part "R-EU0805"))
    )
    (comp (ref "R502")
      (value "100k")
      (footprint "eagle-import:0805")
      (libsource (lib "eagle-import") (part "R-EU0805"))
    )
    (comp (ref "R503")
      (value "100k")
      (footprint "eagle-import:0805")
      (libsource (lib "eagle-import") (part "R-EU0805"))
    )
    (comp (ref "R504")
      (value "100")
      (footprint "eagle-import:0805")
      (libsource (lib "eagle-import") (part "R-EU0805"))
    )
    (comp (ref "R505")
      (value "100")
      (footprint "eagle-import:0805")
      (libsource (lib "eagle-import") (part "R-EU0805"))
    )
    (comp (ref "R506")
      (value "2k7")
      (footprint "eagle-import:0805")
      (libsource (lib "eagle-import") (part "R-EU0805"))
    )
    (comp (ref "R507")
      (value "2k7")
      (footprint "eagle-import:0805")
      (libsource (lib "eagle-import") (part "R-EU0805"))
    )
    (comp (ref "R508")
      (value "100k")
      (footprint "eagle-import:0805")
      (libsource (lib "eagle-import") (part "R-EU0805"))
    )
    (comp (ref "R509")
      (value "100")
      (footprint "eagle-import:0805")
      (libsource (lib "eagle-import") (part "R-EU0805"))
    )
    (comp (ref "R510")
      (value "2k7")
      (footprint "eagle-import:0805")
      (libsource (lib "eagle-import") (part "R-EU0805"))
    )
    (comp (ref "T501")
      (value "SIA400EDJ")
      (footprint "eagle-import:SC70-6L")
      (libsource (lib "eagle-import") (part "SIA400EDJ"))
    )
    (comp (ref "T502")
      (value "SIA400EDJ")
      (footprint "eagle-import:SC70-6L")
      (libsource (lib "eagle-import") (part "SIA400EDJ"))
    )
    (comp (ref "T503")
      (value "SIA400EDJ")
      (footprint "eagle-import:SC70-6L")
      (libsource (lib "eagle-import") (part "SIA400EDJ"))
    )
    (comp (ref "X501")
      (value "W237-102")
      (footprint "eagle-import:W237-102")
      (fields (field (name "MPN") "237-102"))
      (libsource (lib "eagle-import") (part "W237-102"))
    )
    (comp (ref "X502")
      (value "W237-102")
      (footprint "eagle-import:W237-102")
      (fields (field (name "MPN") "237-102"))
      (libsource (lib "eagle-import") (part "W237-102"))
    )
    (comp (ref "X503")
      (value "W237-102")
      (footprint "eagle-import:W237-102")
      (fields (field (name "MPN") "237-102"))
      (libsource (lib "eagle-import") (part "W237-102"))
    )
    (comp (ref "C201")
      (value "470nF/10V")
      (footprint "eagle-import:0805")
      (libsource (lib "eagle-import") (part "C-EU0805"))
    )
    (comp (ref "C202")
      (value "470nF/10V")
      (footprint "eagle-import:0805")
      (libsource (lib "eagle-import") (part "C-EU0805"))
    )
    (comp (ref "C203")
      (value "100nF/50V")
      (footprint "eagle-import:0805")
      (libsource (lib "eagle-import") (part "C-EU0805"))
    )
    (comp (ref "C204")
      (value "100nF/50V")
      (footprint "eagle-import:0805")
      (libsource (lib "eagle-import") (part "C-EU0805"))
    )
    (comp (ref "C205")
      (value "220nF/16V")
      (footprint "eagle-import:0805")
      (libsource (lib "eagle-import") (part "C-EU0805"))
    )
    (comp (ref "C206")
      (value "220nF/16V")
      (footprint "eagle-import:0805")
      (libsource (lib "eagle-import") (part "C-EU0805"))
    )
    (comp (ref "C207")
      (value "100nF/50V")
      (footprint "eagle-import:0805")
      (libsource (lib "eagle-import") (part "C-EU0805"))
    )
    (comp (ref "C208")
      (value "100nF/50V")
      (footprint "eagle-import:0805")
      (libsource (lib "eagle-import") (part "C-EU0805"))
    )
    (comp (ref "C209")
      (value "100nF/50V")
      (footprint "eagle-import:0805")
      (libsource (lib "eagle-import") (part "C-EU0805"))
    )
    (comp (ref "C210")
      (value "100p/100V")
      (footprint "eagle-import:0805")
      (libsource (lib "eagle-import") (part "C-EU0805"))
    )
    (comp (ref "C211")
      (value "100nF/50V")
      (footprint "eagle-import:0805")
      (libsource (lib "eagle-import") (part "C-EU0805"))
    )
    (comp (ref "C212")
      (value "100p/100V")
      (footprint "eagle-import:0805")
      (libsource (lib "eagle-import") (part "C-EU0805"))
    )
    (comp (ref "C213")
      (value "100p/100V")
      (footprint "eagle-import:0805")
      (libsource (lib "eagle-import") (part "C-EU0805"))
    )
    (comp (ref "C214")
      (value "100p/100V")
      (footprint "eagle-import:0805")
      (libsource (lib "eagle-import") (part "C-EU0805"))
    )
    (comp (ref "C215")
      (value "100p/100V")
      (footprint "eagle-import:0805")
      (libsource (lib "eagle-import") (part "C-EU0805"))
    )
    (comp (ref "C216")
      (value "100p/100V")
      (footprint "eagle-import:0805")
      (libsource (lib "eagle-import") (part "C-EU0805"))
    )
    (comp (ref "C217")
      (value "22µF/ low ESR")
      (footprint "eagle-import:SANYO-OSCON_SMD_B6")
      (libsource (lib "eagle-import") (part "CPOL-EUSANYO_SMD_B6"))
    )
    (comp (ref "C218")
      (value "22µF/ low ESR")
      (footprint "eagle-import:SANYO-OSCON_SMD_B6")
      (libsource (lib "eagle-import") (part "CPOL-EUSANYO_SMD_B6"))
    )
    (comp (ref "C219")
      (value "100p/100V")
      (footprint "eagle-import:0805")
      (libsource (lib "eagle-import") (part "C-EU0805"))
    )
    (comp (ref "C220")
      (value "100p/100V")
      (footprint "eagle-import:0805")
      (libsource (lib "eagle-import") (part "C-EU0805"))
    )
    (comp (ref "C221")
      (value "22µF/ low ESR")
      (footprint "eagle-import:SANYO-OSCON_SMD_B6")
      (libsource (lib "eagle-import") (part "CPOL-EUSANYO_SMD_B6"))
    )
    (comp (ref "C222")
      (value "22µF/ low ESR")
      (footprint "eagle-import:SANYO-OSCON_SMD_B6")
      (libsource (lib "eagle-import") (part "CPOL-EUSANYO_SMD_B6"))
    )
    (comp (ref "C223")
      (value "470nF/10V")
      (footprint "eagle-import:0805")
      (libsource (lib "eagle-import") (part "C-EU0805"))
    )
    (comp (ref "C224")
      (value "100nF/50V")
      (footprint "eagle-import:0805")
      (libsource (lib "eagle-import") (part "C-EU0805"))
    )
    (comp (ref "C225")
      (value "220nF/16V")
      (footprint "eagle-import:0805")
      (libsource (lib "eagle-import") (part "C-EU0805"))
    )
    (comp (ref "C226")
      (value "100nF/50V")
      (footprint "eagle-import:0805")
      (libsource (lib "eagle-import") (part "C-EU0805"))
    )
    (comp (ref "C227")
      (value "100nF/50V")
      (footprint "eagle-import:0805")
      (libsource (lib "eagle-import") (part "C-EU0805"))
    )
    (comp (ref "C228")
      (value "100p/100V")
      (footprint "eagle-import:0805")
      (libsource (lib "eagle-import") (part "C-EU0805"))
    )
    (comp (ref "C229")
      (value "100p/100V")
      (footprint "eagle-import:0805")
      (libsource (lib "eagle-import") (part "C-EU0805"))
    )
    (comp (ref "C230")
      (value "100p/100V")
      (footprint "eagle-import:0805")
      (libsource (lib "eagle-import") (part "C-EU0805"))
    )
    (comp (ref "C231")
      (value "22µF/ low ESR")
      (footprint "eagle-import:SANYO-OSCON_SMD_B6")
      (libsource (lib "eagle-import") (part "CPOL-EUSANYO_SMD_B6"))
    )
    (comp (ref "C232")
      (value "100p/100V")
      (footprint "eagle-import:0805")
      (libsource (lib "eagle-import") (part "C-EU0805"))
    )
    (comp (ref "C233")
      (value "22µF/ low ESR")
      (footprint "eagle-import:SANYO-OSCON_SMD_B6")
      (libsource (lib "eagle-import") (part "CPOL-EUSANYO_SMD_B6"))
    )
    (comp (ref "IC201")
      (value "TMC260")
      (footprint "eagle-import:SQFP-S-10X10-44")
      (libsource (lib "eagle-import") (part "TMC260"))
    )
    (comp (ref "IC202")
      (value "TMC260")
      (footprint "eagle-import:SQFP-S-10X10-44")
      (libsource (lib "eagle-import") (part "TMC260"))
    )
    (comp (ref "IC203")
      (value "TMC260")
      (footprint "eagle-import:SQFP-S-10X10-44")
      (libsource (lib "eagle-import") (part "TMC260"))
    )
    (comp (ref "R201")
      (value "0R15/0.5W")
      (footprint "eagle-import:R1206")
      (libsource (lib "eagle-import") (part "R-EU_R1206"))
    )
    (comp (ref "R202")
      (value "0R15/0.5W")
      (footprint "eagle-import:R1206")
      (libsource (lib "eagle-import") (part "R-EU_R1206"))
    )
    (comp (ref "R203")
      (value "0R15/0.5W")
      (footprint "eagle-import:R1206")
      (libsource (lib "eagle-import") (part "R-EU_R1206"))
    )
    (comp (ref "R204")
      (value "0R15/0.5W")
      (footprint "eagle-import:R1206")
      (libsource (lib "eagle-import") (part "R-EU_R1206"))
    )
    (comp (ref "R205")
      (value "0R15/0.5W")
      (footprint "eagle-import:R1206")
      (libsource (lib "eagle-import") (part "R-EU_R1206"))
    )
    (comp (ref "R206")
      (value "0R15/0.5W")
      (footprint "eagle-import:R1206")
      (libsource (lib "eagle-import") (part "R-EU_R1206"))
    )
    (comp (ref "X201")
      (value "W237-4")
      (footprint "eagle-import:W237-4")
      (libsource (lib "eagle-import") (part "W237-4"))
    )
    (comp (ref "X202")
      (value "W237-4")
      (footprint "eagle-import:W237-4")
      (libsource (lib "eagle-import") (part "W237-4"))
    )
    (comp (ref "X203")
      (value "W237-4")
      (footprint "eagle-import:W237-4")
      (libsource (lib "eagle-import") (part "W237-4"))
    )
  )
  (nets
    (net (code "1") (name "+3V3") (class "Default")
      (node (ref "BUZ1") (pin "+") (pinfunction "1_+") (pintype "passive"))
      (node (ref "C101") (pin "1") (pinfunction "1_1") (pintype "passive"))
      (node (ref "C102") (pin "1") (pinfunction "1_1") (pintype "passive"))
      (node (ref "C103") (pin "1") (pinfunction "1_1") (pintype "passive"))
      (node (ref "C104") (pin "1") (pinfunction "1_1") (pintype "passive"))
      (node (ref "C203") (pin "1") (pinfunction "1_1") (pintype "passive"))
      (node (ref "C204") (pin "1") (pinfunction "1_1") (pintype "passive"))
      (node (ref "C224") (pin "1") (pinfunction "1_1") (pintype "passive"))
      (node (ref "C303") (pin "1") (pinfunction "1_1") (pintype "passive"))
      (node (ref "C304") (pin "1") (pinfunction "1_1") (pintype "passive"))
      (node (ref "C324") (pin "1") (pinfunction "1_1") (pintype "passive"))
      (node (ref "C815") (pin "1") (pinfunction "1_1") (pintype "passive"))
      (node (ref "C817") (pin "1") (pinfunction "1_1") (pintype "passive"))
      (node (ref "IC101") (pin "9") (pinfunction "V+_9") (pintype "passive"))
      (node (ref "IC102") (pin "4") (pinfunction "VCC_4") (pintype "power_in"))
      (node (ref "IC103") (pin "18") (pinfunction "~{RESET}_18") (pintype "input"))
      (node (ref "IC103") (pin "9") (pinfunction "VDD_9") (pintype "power_in"))
      (node (ref "IC104") (pin "15") (pinfunction "A0_15") (pintype "input"))
      (node (ref "IC104") (pin "18") (pinfunction "~{RESET}_18") (pintype "input"))
      (node (ref "IC104") (pin "9") (pinfunction "VDD_9") (pintype "power_in"))
      (node (ref "IC201") (pin "40") (pinfunction "VCC_IO_40") (pintype "passive"))
      (node (ref "IC202") (pin "40") (pinfunction "VCC_IO_40") (pintype "passive"))
      (node (ref "IC203") (pin "40") (pinfunction "VCC_IO_40") (pintype "passive"))
      (node (ref "IC301") (pin "40") (pinfunction "VCC_IO_40") (pintype "passive"))
      (node (ref "IC302") (pin "40") (pinfunction "VCC_IO_40") (pintype "passive"))
      (node (ref "IC303") (pin "40") (pinfunction "VCC_IO_40") (pintype "passive"))
      (node (ref "JP103") (pin "9") (pinfunction "9_9") (pintype "passive"))
      (node (ref "JP701") (pin "1") (pinfunction "1_1") (pintype "passive"))
      (node (ref "JP702") (pin "1") (pinfunction "1_1") (pintype "passive"))
      (node (ref "JP703") (pin "1") (pinfunction "1_1") (pintype "passive"))
      (node (ref "JP705") (pin "1") (pinfunction "1_1") (pintype "passive"))
      (node (ref "JP707") (pin "1") (pinfunction "1_1") (pintype "passive"))
      (node (ref "JP708") (pin "1") (pinfunction "1_1") (pintype "passive"))
      (node (ref "JP901") (pin "2") (pinfunction "2_2") (pintype "passive"))
      (node (ref "L802") (pin "2") (pinfunction "2_2") (pintype "passive"))
      (node (ref "R105") (pin "2") (pinfunction "2_2") (pintype "passive"))
      (node (ref "R705") (pin "2") (pinfunction "2_2") (pintype "passive"))
      (node (ref "R710") (pin "2") (pinfunction "2_2") (pintype "passive"))
      (node (ref "R714") (pin "2") (pinfunction "2_2") (pintype "passive"))
      (node (ref "R715") (pin "2") (pinfunction "2_2") (pintype "passive"))
      (node (ref "R716") (pin "2") (pinfunction "2_2") (pintype "passive"))
      (node (ref "R806") (pin "2") (pinfunction "2_2") (pintype "passive"))
      (node (ref "TP1") (pin "TP") (pinfunction "TP_TP") (pintype "input"))
      (node (ref "X103") (pin "4") (pinfunction "VDD_4") (pintype "passive"))
      (node (ref "X104") (pin "22A") (pinfunction "VDD_SUPPLY_22A") (pintype "input"))
    )
    (net (code "2") (name "+12V") (class "Default")
      (node (ref "C401") (pin "1") (pinfunction "1_1") (pintype "passive"))
      (node (ref "C402") (pin "1") (pinfunction "1_1") (pintype "passive"))
      (node (ref "C816") (pin "1") (pinfunction "1_1") (pintype "passive"))
      (node (ref "C818") (pin "1") (pinfunction "1_1") (pintype "passive"))
      (node (ref "IC401") (pin "2") (pinfunction "VCC_2") (pintype "power_in"))
      (node (ref "JP601") (pin "1") (pinfunction "1_1") (pintype "passive"))
      (node (ref "JP602") (pin "1") (pinfunction "1_1") (pintype "passive"))
      (node (ref "JP603") (pin "1") (pinfunction "1_1") (pintype "passive"))
      (node (ref "JP604") (pin "1") (pinfunction "1_1") (pintype "passive"))
      (node (ref "JP605") (pin "1") (pinfunction "1_1") (pintype "passive"))
      (node (ref "L803") (pin "2") (pinfunction "2_2") (pintype "passive"))
      (node (ref "R605") (pin "1") (pinfunction "1_1") (pintype "passive"))
      (node (ref "R606") (pin "1") (pinfunction "1_1") (pintype "passive"))
      (node (ref "R611") (pin "1") (pinfunction "1_1") (pintype "passive"))
      (node (ref "R612") (pin "1") (pinfunction "1_1") (pintype "passive"))
      (node (ref "R615") (pin "1") (pinfunction "1_1") (pintype "passive"))
      (node (ref "R808") (pin "2") (pinfunction "2_2") (pintype "passive"))
      (node (ref "TP3") (pin "TP") (pinfunction "TP_TP") (pintype "input"))
    )
    (net (code "3") (name "+24V") (class "Default")
      (node (ref "C801") (pin "1") (pinfunction "+_1") (pintype "passive"))
      (node (ref "C802") (pin "1") (pinfunction "1_1") (pintype "passive"))
      (node (ref "C803") (pin "1") (pinfunction "1_1") (pintype "passive"))
      (node (ref "C804") (pin "1") (pinfunction "1_1") (pintype "passive"))
      (node (ref "C805") (pin "1") (pinfunction "1_1") (pintype "passive"))
      (node (ref "C806") (pin "1") (pinfunction "1_1") (pintype "passive"))
      (node (ref "IC801") (pin "2") (pinfunction "VIN_2") (pintype "passive"))
      (node (ref "IC802") (pin "2") (pinfunction "VIN_2") (pintype "passive"))
      (node (ref "L801") (pin "2") (pinfunction "2_2") (pintype "passive"))
      (node (ref "TP2") (pin "TP") (pinfunction "TP_TP") (pintype "input"))
      (node (ref "TP4") (pin "TP") (pinfunction "TP_TP") (pintype "input"))
    )
    (net (code "4") (name "+UB") (class "Default")
      (node (ref "C205") (pin "2") (pinfunction "2_2") (pintype "passive"))
      (node (ref "C206") (pin "2") (pinfunction "2_2") (pintype "passive"))
      (node (ref "C207") (pin "1") (pinfunction "1_1") (pintype "passive"))
      (node (ref "C208") (pin "1") (pinfunction "1_1") (pintype "passive"))
      (node (ref "C209") (pin "1") (pinfunction "1_1") (pintype "passive"))
      (node (ref "C211") (pin "1") (pinfunction "1_1") (pintype "passive"))
      (node (ref "C217") (pin "+") (pinfunction "+_+") (pintype "passive"))
      (node (ref "C218") (pin "+") (pinfunction "+_+") (pintype "passive"))
      (node (ref "C221") (pin "+") (pinfunction "+_+") (pintype "passive"))
      (node (ref "C222") (pin "+") (pinfunction "+_+") (pintype "passive"))
      (node (ref "C225") (pin "2") (pinfunction "2_2") (pintype "passive"))
      (node (ref "C226") (pin "1") (pinfunction "1_1") (pintype "passive"))
      (node (ref "C227") (pin "1") (pinfunction "1_1") (pintype "passive"))
      (node (ref "C231") (pin "+") (pinfunction "+_+") (pintype "passive"))
      (node (ref "C233") (pin "+") (pinfunction "+_+") (pintype "passive"))
      (node (ref "C305") (pin "2") (pinfunction "2_2") (pintype "passive"))
      (node (ref "C306") (pin "2") (pinfunction "2_2") (pintype "passive"))
      (node (ref "C307") (pin "1") (pinfunction "1_1") (pintype "passive"))
      (node (ref "C308") (pin "1") (pinfunction "1_1") (pintype "passive"))
      (node (ref "C309") (pin "1") (pinfunction "1_1") (pintype "passive"))
      (node (ref "C311") (pin "1") (pinfunction "1_1") (pintype "passive"))
      (node (ref "C317") (pin "+") (pinfunction "+_+") (pintype "passive"))
      (node (ref "C318") (pin "+") (pinfunction "+_+") (pintype "passive"))
      (node (ref "C321") (pin "+") (pinfunction "+_+") (pintype "passive"))
      (node (ref "C322") (pin "+") (pinfunction "+_+") (pintype "passive"))
      (node (ref "C325") (pin "2") (pinfunction "2_2") (pintype "passive"))
      (node (ref "C326") (pin "1") (pinfunction "1_1") (pintype "passive"))
      (node (ref "C327") (pin "1") (pinfunction "1_1") (pintype "passive"))
      (node (ref "C331") (pin "+") (pinfunction "+_+") (pintype "passive"))
      (node (ref "C333") (pin "+") (pinfunction "+_+") (pintype "passive"))
      (node (ref "D401") (pin "C") (pinfunction "C_C") (pintype "passive"))
      (node (ref "D801") (pin "C") (pinfunction "C_C") (pintype "passive"))
      (node (ref "F501") (pin "3") (pinfunction "2_3") (pintype "passive"))
      (node (ref "F501") (pin "4") (pinfunction "2_4") (pintype "passive"))
      (node (ref "IC201") (pin "30") (pinfunction "VSB_30") (pintype "passive"))
      (node (ref "IC201") (pin "36") (pinfunction "VS_36") (pintype "passive"))
      (node (ref "IC201") (pin "4") (pinfunction "VSA_4") (pintype "passive"))
      (node (ref "IC202") (pin "30") (pinfunction "VSB_30") (pintype "passive"))
      (node (ref "IC202") (pin "36") (pinfunction "VS_36") (pintype "passive"))
      (node (ref "IC202") (pin "4") (pinfunction "VSA_4") (pintype "passive"))
      (node (ref "IC203") (pin "30") (pinfunction "VSB_30") (pintype "passive"))
      (node (ref "IC203") (pin "36") (pinfunction "VS_36") (pintype "passive"))
      (node (ref "IC203") (pin "4") (pinfunction "VSA_4") (pintype "passive"))
      (node (ref "IC301") (pin "30") (pinfunction "VSB_30") (pintype "passive"))
      (node (ref "IC301") (pin "36") (pinfunction "VS_36") (pintype "passive"))
      (node (ref "IC301") (pin "4") (pinfunction "VSA_4") (pintype "passive"))
      (node (ref "IC302") (pin "30") (pinfunction "VSB_30") (pintype "passive"))
      (node (ref "IC302") (pin "36") (pinfunction "VS_36") (pintype "passive"))
      (node (ref "IC302") (pin "4") (pinfunction "VSA_4") (pintype "passive"))
      (node (ref "IC303") (pin "30") (pinfunction "VSB_30") (pintype "passive"))
      (node (ref "IC303") (pin "36") (pinfunction "VS_36") (pintype "passive"))
      (node (ref "IC303") (pin "4") (pinfunction "VSA_4") (pintype "passive"))
      (node (ref "L801") (pin "1") (pinfunction "1_1") (pintype "passive"))
      (node (ref "R403") (pin "1") (pinfunction "1_1") (pintype "passive"))
      (node (ref "R501") (pin "1") (pinfunction "1_1") (pintype "passive"))
      (node (ref "R801") (pin "2") (pinfunction "2_2") (pintype "passive"))
      (node (ref "T801") (pin "1") (pinfunction "S_1") (pintype "passive"))
      (node (ref "T801") (pin "2") (pinfunction "S_2") (pintype "passive"))
      (node (ref "T801") (pin "3") (pinfunction "S_3") (pintype "passive"))
      (node (ref "X401") (pin "1") (pinfunction "KL_1") (pintype "passive"))
      (node (ref "X401") (pin "2") (pinfunction "KL_2") (pintype "passive"))
    )
    (net (code "5") (name "AUX_IN_0") (class "Default")
      (node (ref "IC103") (pin "28") (pinfunction "GPA7_28") (pintype "bidirectional"))
      (node (ref "JP901") (pin "1") (pinfunction "1_1") (pintype "passive"))
    )
    (net (code "6") (name "AUX_IN_1") (class "Default")
      (node (ref "IC104") (pin "27") (pinfunction "GPA6_27") (pintype "bidirectional"))
      (node (ref "JP901") (pin "3") (pinfunction "3_3") (pintype "passive"))
    )
    (net (code "7") (name "AUX_IN_2") (class "Default")
      (node (ref "IC104") (pin "28") (pinfunction "GPA7_28") (pintype "bidirectional"))
      (node (ref "JP901") (pin "5") (pinfunction "5_5") (pintype "passive"))
    )
    (net (code "8") (name "BUZZER") (class "Default")
      (node (ref "R102") (pin "2") (pinfunction "2_2") (pintype "passive"))
      (node (ref "X104") (pin "30A") (pinfunction "PG14/LED_RD_30A") (pintype "bidirectional"))
    )
    (net (code "9") (name "CASE_FAN_EN") (class "Default")
      (node (ref "IC103") (pin "5") (pinfunction "GPB4_5") (pintype "bidirectional"))
      (node (ref "R602") (pin "1") (pinfunction "1_1") (pintype "passive"))
      (node (ref "R604") (pin "1") (pinfunction "1_1") (pintype "passive"))
    )
    (net (code "10") (name "CASE_LIGHT_EN") (class "Default")
      (node (ref "IC103") (pin "4") (pinfunction "GPB3_4") (pintype "bidirectional"))
      (node (ref "R609") (pin "1") (pinfunction "1_1") (pintype "passive"))
      (node (ref "R610") (pin "1") (pinfunction "1_1") (pintype "passive"))
    )
    (net (code "11") (name "CASE_TEMP") (class "Default")
      (node (ref "C701") (pin "1") (pinfunction "1_1") (pintype "passive"))
      (node (ref "R704") (pin "1") (pinfunction "1_1") (pintype "passive"))
      (node (ref "X104") (pin "18B") (pinfunction "PA0/PUSHBUTTON_18B") (pintype "bidirectional"))
    )
    (net (code "12") (name "E0_DIR") (class "Default")
      (node (ref "IC201") (pin "41") (pinfunction "DIR_41") (pintype "input"))
      (node (ref "X104") (pin "12A") (pinfunction "PC13_12A") (pintype "bidirectional"))
    )
    (net (code "13") (name "E0_SG_TST") (class "Default")
      (node (ref "IC104") (pin "21") (pinfunction "GPA0_21") (pintype "bidirectional"))
      (node (ref "IC201") (pin "38") (pinfunction "SG_TST_38") (pintype "output"))
    )
    (net (code "14") (name "E0_STP") (class "Default")
      (node (ref "IC201") (pin "42") (pinfunction "STEP_42") (pintype "input"))
      (node (ref "X104") (pin "13A") (pinfunction "PE4_13A") (pintype "bidirectional"))
    )
    (net (code "15") (name "E1_DIR") (class "Default")
      (node (ref "IC203") (pin "41") (pinfunction "DIR_41") (pintype "input"))
      (node (ref "X104") (pin "16A") (pinfunction "PE3_16A") (pintype "bidirectional"))
    )
    (net (code "16") (name "E1_SG_TST") (class "Default")
      (node (ref "IC104") (pin "22") (pinfunction "GPA1_22") (pintype "bidirectional"))
      (node (ref "IC203") (pin "38") (pinfunction "SG_TST_38") (pintype "output"))
    )
    (net (code "17") (name "E1_STP") (class "Default")
      (node (ref "IC203") (pin "42") (pinfunction "STEP_42") (pintype "input"))
      (node (ref "X104") (pin "15A") (pinfunction "PE2_15A") (pintype "bidirectional"))
    )
    (net (code "18") (name "E2_DIR") (class "Default")
      (node (ref "IC202") (pin "41") (pinfunction "DIR_41") (pintype "input"))
      (node (ref "X104") (pin "25A") (pinfunction "PB4_25A") (pintype "bidirectional"))
    )
    (net (code "19") (name "E2_SG_TST") (class "Default")
      (node (ref "IC104") (pin "23") (pinfunction "GPA2_23") (pintype "bidirectional"))
      (node (ref "IC202") (pin "38") (pinfunction "SG_TST_38") (pintype "output"))
    )
    (net (code "20") (name "E2_STP") (class "Default")
      (node (ref "IC202") (pin "42") (pinfunction "STEP_42") (pintype "input"))
      (node (ref "X104") (pin "24A") (pinfunction "PB7_24A") (pintype "bidirectional"))
    )
    (net (code "21") (name "EMERGENCY_STOP") (class "Default")
      (node (ref "IC103") (pin "27") (pinfunction "GPA6_27") (pintype "bidirectional"))
      (node (ref "JP902") (pin "2") (pinfunction "2_2") (pintype "passive"))
    )
    (net (code "22") (name "FAN0_EN") (class "Default")
      (node (ref "IC103") (pin "1") (pinfunction "GPB0_1") (pintype "bidirectional"))
      (node (ref "R601") (pin "1") (pinfunction "1_1") (pintype "passive"))
      (node (ref "R603") (pin "1") (pinfunction "1_1") (pintype "passive"))
    )
    (net (code "23") (name "FAN1_EN") (class "Default")
      (node (ref "IC103") (pin "2") (pinfunction "GPB1_2") (pintype "bidirectional"))
      (node (ref "R607") (pin "1") (pinfunction "1_1") (pintype "passive"))
      (node (ref "R608") (pin "1") (pinfunction "1_1") (pintype "passive"))
    )
    (net (code "24") (name "FAN2_EN") (class "Default")
      (node (ref "IC103") (pin "3") (pinfunction "GPB2_3") (pintype "bidirectional"))
      (node (ref "R613") (pin "1") (pinfunction "1_1") (pintype "passive"))
      (node (ref "R614") (pin "1") (pinfunction "1_1") (pintype "passive"))
    )
    (net (code "25") (name "GND") (class "Default")
      (node (ref "C101") (pin "2") (pinfunction "2_2") (pintype "passive"))
      (node (ref "C102") (pin "2") (pinfunction "2_2") (pintype "passive"))
      (node (ref "C103") (pin "2") (pinfunction "2_2") (pintype "passive"))
      (node (ref "C104") (pin "2") (pinfunction "2_2") (pintype "passive"))
      (node (ref "C201") (pin "2") (pinfunction "2_2") (pintype "passive"))
      (node (ref "C202") (pin "2") (pinfunction "2_2") (pintype "passive"))
      (node (ref "C203") (pin "2") (pinfunction "2_2") (pintype "passive"))
      (node (ref "C204") (pin "2") (pinfunction "2_2") (pintype "passive"))
      (node (ref "C207") (pin "2") (pinfunction "2_2") (pintype "passive"))
      (node (ref "C208") (pin "2") (pinfunction "2_2") (pintype "passive"))
      (node (ref "C209") (pin "2") (pinfunction "2_2") (pintype "passive"))
      (node (ref "C210") (pin "2") (pinfunction "2_2") (pintype "passive"))
      (node (ref "C211") (pin "2") (pinfunction "2_2") (pintype "passive"))
      (node (ref "C212") (pin "2") (pinfunction "2_2") (pintype "passive"))
      (node (ref "C213") (pin "2") (pinfunction "2_2") (pintype "passive"))
      (node (ref "C214") (pin "2") (pinfunction "2_2") (pintype "passive"))
      (node (ref "C215") (pin "2") (pinfunction "2_2") (pintype "passive"))
      (node (ref "C216") (pin "2") (pinfunction "2_2") (pintype "passive"))
      (node (ref "C217") (pin "-") (pinfunction "-_-") (pintype "passive"))
      (node (ref "C218") (pin "-") (pinfunction "-_-") (pintype "passive"))
      (node (ref "C219") (pin "2") (pinfunction "2_2") (pintype "passive"))
      (node (ref "C220") (pin "2") (pinfunction "2_2") (pintype "passive"))
      (node (ref "C221") (pin "-") (pinfunction "-_-") (pintype "passive"))
      (node (ref "C222") (pin "-") (pinfunction "-_-") (pintype "passive"))
      (node (ref "C223") (pin "2") (pinfunction "2_2") (pintype "passive"))
      (node (ref "C224") (pin "2") (pinfunction "2_2") (pintype "passive"))
      (node (ref "C226") (pin "2") (pinfunction "2_2") (pintype "passive"))
      (node (ref "C227") (pin "2") (pinfunction "2_2") (pintype "passive"))
      (node (ref "C228") (pin "2") (pinfunction "2_2") (pintype "passive"))
      (node (ref "C229") (pin "2") (pinfunction "2_2") (pintype "passive"))
      (node (ref "C230") (pin "2") (pinfunction "2_2") (pintype "passive"))
      (node (ref "C231") (pin "-") (pinfunction "-_-") (pintype "passive"))
      (node (ref "C232") (pin "2") (pinfunction "2_2") (pintype "passive"))
      (node (ref "C233") (pin "-") (pinfunction "-_-") (pintype "passive"))
      (node (ref "C301") (pin "2") (pinfunction "2_2") (pintype "passive"))
      (node (ref "C302") (pin "2") (pinfunction "2_2") (pintype "passive"))
      (node (ref "C303") (pin "2") (pinfunction "2_2") (pintype "passive"))
      (node (ref "C304") (pin "2") (pinfunction "2_2") (pintype "passive"))
      (node (ref "C307") (pin "2") (pinfunction "2_2") (pintype "passive"))
      (node (ref "C308") (pin "2") (pinfunction "2_2") (pintype "passive"))
      (node (ref "C309") (pin "2") (pinfunction "2_2") (pintype "passive"))
      (node (ref "C310") (pin "2") (pinfunction "2_2") (pintype "passive"))
      (node (ref "C311") (pin "2") (pinfunction "2_2") (pintype "passive"))
      (node (ref "C312") (pin "2") (pinfunction "2_2") (pintype "passive"))
      (node (ref "C313") (pin "2") (pinfunction "2_2") (pintype "passive"))
      (node (ref "C314") (pin "2") (pinfunction "2_2") (pintype "passive"))
      (node (ref "C315") (pin "2") (pinfunction "2_2") (pintype "passive"))
      (node (ref "C316") (pin "2") (pinfunction "2_2") (pintype "passive"))
      (node (ref "C317") (pin "-") (pinfunction "-_-") (pintype "passive"))
      (node (ref "C318") (pin "-") (pinfunction "-_-") (pintype "passive"))
      (node (ref "C319") (pin "2") (pinfunction "2_2") (pintype "passive"))
      (node (ref "C320") (pin "2") (pinfunction "2_2") (pintype "passive"))
      (node (ref "C321") (pin "-") (pinfunction "-_-") (pintype "passive"))
      (node (ref "C322") (pin "-") (pinfunction "-_-") (pintype "passive"))
      (node (ref "C323") (pin "2") (pinfunction "2_2") (pintype "passive"))
      (node (ref "C324") (pin "2") (pinfunction "2_2") (pintype "passive"))
      (node (ref "C326") (pin "2") (pinfunction "2_2") (pintype "passive"))
      (node (ref "C327") (pin "2") (pinfunction "2_2") (pintype "passive"))
      (node (ref "C328") (pin "2") (pinfunction "2_2") (pintype "passive"))
      (node (ref "C329") (pin "2") (pinfunction "2_2") (pintype "passive"))
      (node (ref "C330") (pin "2") (pinfunction "2_2") (pintype "passive"))
      (node (ref "C331") (pin "-") (pinfunction "-_-") (pintype "passive"))
      (node (ref "C332") (pin "2") (pinfunction "2_2") (pintype "passive"))
      (node (ref "C333") (pin "-") (pinfunction "-_-") (pintype "passive"))
      (node (ref "C401") (pin "2") (pinfunction "2_2") (pintype "passive"))
      (node (ref "C402") (pin "2") (pinfunction "2_2") (pintype "passive"))
      (node (ref "C403") (pin "2") (pinfunction "2_2") (pintype "passive"))
      (node (ref "C501") (pin "2") (pinfunction "2_2") (pintype "passive"))
      (node (ref "C502") (pin "2") (pinfunction "2_2") (pintype "passive"))
      (node (ref "C503") (pin "2") (pinfunction "2_2") (pintype "passive"))
      (node (ref "C601") (pin "2") (pinfunction "2_2") (pintype "passive"))
      (node (ref "C602") (pin "2") (pinfunction "2_2") (pintype "passive"))
      (node (ref "C603") (pin "2") (pinfunction "2_2") (pintype "passive"))
      (node (ref "C604") (pin "2") (pinfunction "2_2") (pintype "passive"))
      (node (ref "C605") (pin "2") (pinfunction "2_2") (pintype "passive"))
      (node (ref "C701") (pin "2") (pinfunction "2_2") (pintype "passive"))
      (node (ref "C702") (pin "2") (pinfunction "2_2") (pintype "passive"))
      (node (ref "C703") (pin "2") (pinfunction "2_2") (pintype "passive"))
      (node (ref "C704") (pin "2") (pinfunction "2_2") (pintype "passive"))
      (node (ref "C705") (pin "2") (pinfunction "2_2") (pintype "passive"))
      (node (ref "C706") (pin "2") (pinfunction "2_2") (pintype "passive"))
      (node (ref "C707") (pin "2") (pinfunction "2_2") (pintype "passive"))
      (node (ref "C708") (pin "2") (pinfunction "2_2") (pintype "passive"))
      (node (ref "C709") (pin "2") (pinfunction "2_2") (pintype "passive"))
      (node (ref "C710") (pin "2") (pinfunction "2_2") (pintype "passive"))
      (node (ref "C711") (pin "2") (pinfunction "2_2") (pintype "passive"))
      (node (ref "C712") (pin "2") (pinfunction "2_2") (pintype "passive"))
      (node (ref "C713") (pin "2") (pinfunction "2_2") (pintype "passive"))
      (node (ref "C714") (pin "2") (pinfunction "2_2") (pintype "passive"))
      (node (ref "C715") (pin "2") (pinfunction "2_2") (pintype "passive"))
      (node (ref "C716") (pin "2") (pinfunction "2_2") (pintype "passive"))
      (node (ref "C801") (pin "2") (pinfunction "-_2") (pintype "passive"))
      (node (ref "C802") (pin "2") (pinfunction "2_2") (pintype "passive"))
      (node (ref "C803") (pin "2") (pinfunction "2_2") (pintype "passive"))
      (node (ref "C804") (pin "2") (pinfunction "2_2") (pintype "passive"))
      (node (ref "C805") (pin "2") (pinfunction "2_2") (pintype "passive"))
      (node (ref "C806") (pin "2") (pinfunction "2_2") (pintype "passive"))
      (node (ref "C807") (pin "2") (pinfunction "2_2") (pintype "passive"))
      (node (ref "C808") (pin "2") (pinfunction "2_2") (pintype "passive"))
      (node (ref "C811") (pin "2") (pinfunction "2_2") (pintype "passive"))
      (node (ref "C812") (pin "2") (pinfunction "2_2") (pintype "passive"))
      (node (ref "C815") (pin "2") (pinfunction "2_2") (pintype "passive"))
      (node (ref "C816") (pin "2") (pinfunction "2_2") (pintype "passive"))
      (node (ref "C817") (pin "2") (pinfunction "2_2") (pintype "passive"))
      (node (ref "C818") (pin "2") (pinfunction "2_2") (pintype "passive"))
      (node (ref "D802") (pin "A") (pinfunction "A_A") (pintype "passive"))
      (node (ref "D803") (pin "A") (pinfunction "A_A") (pintype "passive"))
      (node (ref "IC101") (pin "3") (pinfunction "GND_3") (pintype "passive"))
      (node (ref "IC102") (pin "2") (pinfunction "GND_2") (pintype "power_in"))
      (node (ref "IC103") (pin "10") (pinfunction "VSS_10") (pintype "power_in"))
      (node (ref "IC103") (pin "15") (pinfunction "A0_15") (pintype "input"))
      (node (ref "IC103") (pin "16") (pinfunction "A1_16") (pintype "input"))
      (node (ref "IC103") (pin "17") (pinfunction "A2_17") (pintype "input"))
      (node (ref "IC104") (pin "10") (pinfunction "VSS_10") (pintype "power_in"))
      (node (ref "IC104") (pin "16") (pinfunction "A1_16") (pintype "input"))
      (node (ref "IC104") (pin "17") (pinfunction "A2_17") (pintype "input"))
      (node (ref "IC201") (pin "17") (pinfunction "GND_17") (pintype "passive"))
      (node (ref "IC201") (pin "21") (pinfunction "CLK_21") (pintype "input"))
      (node (ref "IC201") (pin "39") (pinfunction "GND_39") (pintype "passive"))
      (node (ref "IC201") (pin "43") (pinfunction "TST_MODE_43") (pintype "input"))
      (node (ref "IC201") (pin "44") (pinfunction "GND_44") (pintype "passive"))
      (node (ref "IC202") (pin "17") (pinfunction "GND_17") (pintype "passive"))
      (node (ref "IC202") (pin "21") (pinfunction "CLK_21") (pintype "input"))
      (node (ref "IC202") (pin "39") (pinfunction "GND_39") (pintype "passive"))
      (node (ref "IC202") (pin "43") (pinfunction "TST_MODE_43") (pintype "input"))
      (node (ref "IC202") (pin "44") (pinfunction "GND_44") (pintype "passive"))
      (node (ref "IC203") (pin "17") (pinfunction "GND_17") (pintype "passive"))
      (node (ref "IC203") (pin "21") (pinfunction "CLK_21") (pintype "input"))
      (node (ref "IC203") (pin "39") (pinfunction "GND_39") (pintype "passive"))
      (node (ref "IC203") (pin "43") (pinfunction "TST_MODE_43") (pintype "input"))
      (node (ref "IC203") (pin "44") (pinfunction "GND_44") (pintype "passive"))
      (node (ref "IC301") (pin "17") (pinfunction "GND_17") (pintype "passive"))
      (node (ref "IC301") (pin "21") (pinfunction "CLK_21") (pintype "input"))
      (node (ref "IC301") (pin "39") (pinfunction "GND_39") (pintype "passive"))
      (node (ref "IC301") (pin "43") (pinfunction "TST_MODE_43") (pintype "input"))
      (node (ref "IC301") (pin "44") (pinfunction "GND_44") (pintype "passive"))
      (node (ref "IC302") (pin "17") (pinfunction "GND_17") (pintype "passive"))
      (node (ref "IC302") (pin "21") (pinfunction "CLK_21") (pintype "input"))
      (node (ref "IC302") (pin "39") (pinfunction "GND_39") (pintype "passive"))
      (node (ref "IC302") (pin "43") (pinfunction "TST_MODE_43") (pintype "input"))
      (node (ref "IC302") (pin "44") (pinfunction "GND_44") (pintype "passive"))
      (node (ref "IC303") (pin "17") (pinfunction "GND_17") (pintype "passive"))
      (node (ref "IC303") (pin "21") (pinfunction "CLK_21") (pintype "input"))
      (node (ref "IC303") (pin "39") (pinfunction "GND_39") (pintype "passive"))
      (node (ref "IC303") (pin "43") (pinfunction "TST_MODE_43") (pintype "input"))
      (node (ref "IC303") (pin "44") (pinfunction "GND_44") (pintype "passive"))
      (node (ref "IC401") (pin "1") (pinfunction "GND_1") (pintype "power_in"))
      (node (ref "IC401") (pin "4") (pinfunction "GND_4") (pintype "power_in"))
      (node (ref "IC801") (pin "7") (pinfunction "GND_7") (pintype "passive"))
      (node (ref "IC801") (pin "9") (pinfunction "EX-PAD_9") (pintype "passive"))
      (node (ref "IC802") (pin "7") (pinfunction "GND_7") (pintype "passive"))
      (node (ref "IC802") (pin "9") (pinfunction "EX-PAD_9") (pintype "passive"))
      (node (ref "JP101") (pin "1") (pinfunction "1_1") (pintype "passive"))
      (node (ref "JP101") (pin "2") (pinfunction "2_2") (pintype "passive"))
      (node (ref "JP102") (pin "1") (pinfunction "1_1") (pintype "passive"))
      (node (ref "JP102") (pin "2") (pinfunction "2_2") (pintype "passive"))
      (node (ref "JP103") (pin "1") (pinfunction "1_1") (pintype "passive"))
      (node (ref "JP103") (pin "3") (pinfunction "3_3") (pintype "passive"))
      (node (ref "JP103") (pin "5") (pinfunction "5_5") (pintype "passive"))
      (node (ref "JP103") (pin "7") (pinfunction "7_7") (pintype "passive"))
      (node (ref "JP701") (pin "3") (pinfunction "3_3") (pintype "passive"))
      (node (ref "JP702") (pin "3") (pinfunction "3_3") (pintype "passive"))
      (node (ref "JP703") (pin "3") (pinfunction "3_3") (pintype "passive"))
      (node (ref "JP704") (pin "1") (pinfunction "1_1") (pintype "passive"))
      (node (ref "JP705") (pin "3") (pinfunction "3_3") (pintype "passive"))
      (node (ref "JP706") (pin "1") (pinfunction "1_1") (pintype "passive"))
      (node (ref "JP707") (pin "3") (pinfunction "3_3") (pintype "passive"))
      (node (ref "JP708") (pin "3") (pinfunction "3_3") (pintype "passive"))
      (node (ref "JP709") (pin "1") (pinfunction "1_1") (pintype "passive"))
      (node (ref "JP710") (pin "1") (pinfunction "1_1") (pintype "passive"))
      (node (ref "JP711") (pin "1") (pinfunction "1_1") (pintype "passive"))
      (node (ref "JP901") (pin "4") (pinfunction "4_4") (pintype "passive"))
      (node (ref "JP901") (pin "6") (pinfunction "6_6") (pintype "passive"))
      (node (ref "JP902") (pin "1") (pinfunction "1_1") (pintype "passive"))
      (node (ref "Q101") (pin "E") (pinfunction "E_E") (pintype "passive"))
      (node (ref "Q102") (pin "E") (pinfunction "E_E") (pintype "passive"))
      (node (ref "R101") (pin "2") (pinfunction "2_2") (pintype "passive"))
      (node (ref "R103") (pin "1") (pinfunction "1_1") (pintype "passive"))
      (node (ref "R104") (pin "1") (pinfunction "1_1") (pintype "passive"))
      (node (ref "R106") (pin "1") (pinfunction "1_1") (pintype "passive"))
      (node (ref "R201") (pin "2") (pinfunction "2_2") (pintype "passive"))
      (node (ref "R202") (pin "2") (pinfunction "2_2") (pintype "passive"))
      (node (ref "R203") (pin "2") (pinfunction "2_2") (pintype "passive"))
      (node (ref "R204") (pin "2") (pinfunction "2_2") (pintype "passive"))
      (node (ref "R205") (pin "2") (pinfunction "2_2") (pintype "passive"))
      (node (ref "R206") (pin "2") (pinfunction "2_2") (pintype "passive"))
      (node (ref "R301") (pin "2") (pinfunction "2_2") (pintype "passive"))
      (node (ref "R302") (pin "2") (pinfunction "2_2") (pintype "passive"))
      (node (ref "R303") (pin "2") (pinfunction "2_2") (pintype "passive"))
      (node (ref "R304") (pin "2") (pinfunction "2_2") (pintype "passive"))
      (node (ref "R305") (pin "2") (pinfunction "2_2") (pintype "passive"))
      (node (ref "R306") (pin "2") (pinfunction "2_2") (pintype "passive"))
      (node (ref "R401") (pin "2") (pinfunction "2_2") (pintype "passive"))
      (node (ref "R502") (pin "2") (pinfunction "2_2") (pintype "passive"))
      (node (ref "R503") (pin "2") (pinfunction "2_2") (pintype "passive"))
      (node (ref "R508") (pin "2") (pinfunction "2_2") (pintype "passive"))
      (node (ref "R601") (pin "2") (pinfunction "2_2") (pintype "passive"))
      (node (ref "R602") (pin "2") (pinfunction "2_2") (pintype "passive"))
      (node (ref "R607") (pin "2") (pinfunction "2_2") (pintype "passive"))
      (node (ref "R609") (pin "2") (pinfunction "2_2") (pintype "passive"))
      (node (ref "R613") (pin "2") (pinfunction "2_2") (pintype "passive"))
      (node (ref "R803") (pin "1") (pinfunction "1_1") (pintype "passive"))
      (node (ref "R804") (pin "1") (pinfunction "1_1") (pintype "passive"))
      (node (ref "R805") (pin "1") (pinfunction "1_1") (pintype "passive"))
      (node (ref "R807") (pin "1") (pinfunction "1_1") (pintype "passive"))
      (node (ref "R809") (pin "1") (pinfunction "1_1") (pintype "passive"))
      (node (ref "R901") (pin "1") (pinfunction "1_1") (pintype "passive"))
      (node (ref "R902") (pin "1") (pinfunction "1_1") (pintype "passive"))
      (node (ref "R903") (pin "1") (pinfunction "1_1") (pintype "passive"))
      (node (ref "T401") (pin "1") (pinfunction "S_1") (pintype "passive"))
      (node (ref "T401") (pin "2") (pinfunction "S_2") (pintype "passive"))
      (node (ref "T401") (pin "3") (pinfunction "S_3") (pintype "passive"))
      (node (ref "T501") (pin "4") (pinfunction "S_4") (pintype "passive"))
      (node (ref "T501") (pin "EXP_SOURCE") (pinfunction "S_EXP_SOURCE") (pintype "passive"))
      (node (ref "T502") (pin "4") (pinfunction "S_4") (pintype "passive"))
      (node (ref "T502") (pin "EXP_SOURCE") (pinfunction "S_EXP_SOURCE") (pintype "passive"))
      (node (ref "T503") (pin "4") (pinfunction "S_4") (pintype "passive"))
      (node (ref "T503") (pin "EXP_SOURCE") (pinfunction "S_EXP_SOURCE") (pintype "passive"))
      (node (ref "T601") (pin "4") (pinfunction "S_4") (pintype "passive"))
      (node (ref "T601") (pin "EXP_SOURCE") (pinfunction "S_EXP_SOURCE") (pintype "passive"))
      (node (ref "T602") (pin "4") (pinfunction "S_4") (pintype "passive"))
      (node (ref "T602") (pin "EXP_SOURCE") (pinfunction "S_EXP_SOURCE") (pintype "passive"))
      (node (ref "T603") (pin "4") (pinfunction "S_4") (pintype "passive"))
      (node (ref "T603") (pin "EXP_SOURCE") (pinfunction "S_EXP_SOURCE") (pintype "passive"))
      (node (ref "T604") (pin "4") (pinfunction "S_4") (pintype "passive"))
      (node (ref "T604") (pin "EXP_SOURCE") (pinfunction "S_EXP_SOURCE") (pintype "passive"))
      (node (ref "T605") (pin "4") (pinfunction "S_4") (pintype "passive"))
      (node (ref "T605") (pin "EXP_SOURCE") (pinfunction "S_EXP_SOURCE") (pintype "passive"))
      (node (ref "X101") (pin "4") (pinfunction "4_4") (pintype "passive"))
      (node (ref "X102") (pin "4") (pinfunction "4_4") (pintype "passive"))
      (node (ref "X103") (pin "3") (pinfunction "GND_3") (pintype "passive"))
      (node (ref "X103") (pin "6") (pinfunction "GND_6") (pintype "passive"))
      (node (ref "X103") (pin "GND1") (pinfunction "GND_GND1") (pintype "passive"))
      (node (ref "X103") (pin "GND2") (pinfunction "GND_GND2") (pintype "passive"))
      (node (ref "X103") (pin "GND3") (pinfunction "GND_GND3") (pintype "passive"))
      (node (ref "X103") (pin "GND4") (pinfunction "GND_GND4") (pintype "passive"))
      (node (ref "X104") (pin "1") (pinfunction "GND_1") (pintype "passive"))
      (node (ref "X104") (pin "11B") (pinfunction "GND_11B") (pintype "bidirectional"))
      (node (ref "X104") (pin "2") (pinfunction "GND_2") (pintype "passive"))
      (node (ref "X104") (pin "29B") (pinfunction "GND_29B") (pintype "bidirectional"))
      (node (ref "X104") (pin "3") (pinfunction "GND_3") (pintype "passive"))
      (node (ref "X104") (pin "4") (pinfunction "GND_4") (pintype "passive"))
      (node (ref "X104") (pin "63A") (pinfunction "GND_63A") (pintype "passive"))
      (node (ref "X104") (pin "63B") (pinfunction "GND_63B") (pintype "bidirectional"))
      (node (ref "X104") (pin "64A") (pinfunction "GND_64A") (pintype "passive"))
      (node (ref "X104") (pin "64B") (pinfunction "GND_64B") (pintype "bidirectional"))
      (node (ref "X801") (pin "1") (pinfunction "GND$1_1") (pintype "power_in"))
      (node (ref "X801") (pin "2") (pinfunction "GND$2_2") (pintype "power_in"))
      (node (ref "X802") (pin "1") (pinfunction "KL_1") (pintype "passive"))
      (node (ref "X802") (pin "2") (pinfunction "KL_2") (pintype "passive"))
    )
    (net (code "26") (name "HB_EN") (class "Default")
      (node (ref "IC401") (pin "3") (pinfunction "I_3") (pintype "input"))
      (node (ref "R401") (pin "1") (pinfunction "1_1") (pintype "passive"))
      (node (ref "X104") (pin "35A") (pinfunction "PD7_35A") (pintype "bidirectional"))
    )
    (net (code "27") (name "HB_TEMP") (class "Default")
      (node (ref "C706") (pin "1") (pinfunction "1_1") (pintype "passive"))
      (node (ref "R709") (pin "1") (pinfunction "1_1") (pintype "passive"))
      (node (ref "X104") (pin "3B") (pinfunction "PF6_3B") (pintype "bidirectional"))
    )
    (net (code "28") (name "HE0_EN") (class "Default")
      (node (ref "R502") (pin "1") (pinfunction "1_1") (pintype "passive"))
      (node (ref "R504") (pin "1") (pinfunction "1_1") (pintype "passive"))
      (node (ref "X104") (pin "37A") (pinfunction "PD5_37A") (pintype "bidirectional"))
    )
    (net (code "29") (name "HE0_TEMP") (class "Default")
      (node (ref "C711") (pin "1") (pinfunction "1_1") (pintype "passive"))
      (node (ref "R711") (pin "1") (pinfunction "1_1") (pintype "passive"))
      (node (ref "X104") (pin "15B") (pinfunction "PC3_15B") (pintype "bidirectional"))
    )
    (net (code "30") (name "HE1_EN") (class "Default")
      (node (ref "R503") (pin "1") (pinfunction "1_1") (pintype "passive"))
      (node (ref "R505") (pin "1") (pinfunction "1_1") (pintype "passive"))
      (node (ref "X104") (pin "38A") (pinfunction "PD4_38A") (pintype "bidirectional"))
    )
    (net (code "31") (name "HE1_TEMP") (class "Default")
      (node (ref "C712") (pin "1") (pinfunction "1_1") (pintype "passive"))
      (node (ref "R712") (pin "1") (pinfunction "1_1") (pintype "passive"))
      (node (ref "X104") (pin "21B") (pinfunction "PA5_21B") (pintype "bidirectional"))
    )
    (net (code "32") (name "HE2_EN") (class "Default")
      (node (ref "R508") (pin "1") (pinfunction "1_1") (pintype "passive"))
      (node (ref "R509") (pin "1") (pinfunction "1_1") (pintype "passive"))
      (node (ref "X104") (pin "44A") (pinfunction "PC11_44A") (pintype "bidirectional"))
    )
    (net (code "33") (name "HE2_TEMP") (class "Default")
      (node (ref "C713") (pin "1") (pinfunction "1_1") (pintype "passive"))
      (node (ref "R713") (pin "1") (pinfunction "1_1") (pintype "passive"))
      (node (ref "X104") (pin "23B") (pinfunction "PA7/ACP_RST_23B") (pintype "bidirectional"))
    )
    (net (code "34") (name "INTA_PORTEX0") (class "Default")
      (node (ref "IC103") (pin "20") (pinfunction "INTA_20") (pintype "output"))
      (node (ref "X104") (pin "9A") (pinfunction "PC14/OSC32_IN_9A") (pintype "bidirectional"))
    )
    (net (code "35") (name "INTA_PORTEX1") (class "Default")
      (node (ref "IC104") (pin "20") (pinfunction "INTA_20") (pintype "output"))
      (node (ref "X104") (pin "10A") (pinfunction "PC15/OSC32_OUT_10A") (pintype "bidirectional"))
    )
    (net (code "36") (name "MISO") (class "Default")
      (node (ref "IC103") (pin "14") (pinfunction "SO_14") (pintype "output"))
      (node (ref "IC104") (pin "14") (pinfunction "SO_14") (pintype "output"))
      (node (ref "IC201") (pin "14") (pinfunction "SDO_14") (pintype "output"))
      (node (ref "IC202") (pin "14") (pinfunction "SDO_14") (pintype "output"))
      (node (ref "IC203") (pin "14") (pinfunction "SDO_14") (pintype "output"))
      (node (ref "IC301") (pin "14") (pinfunction "SDO_14") (pintype "output"))
      (node (ref "IC302") (pin "14") (pinfunction "SDO_14") (pintype "output"))
      (node (ref "IC303") (pin "14") (pinfunction "SDO_14") (pintype "output"))
      (node (ref "JP103") (pin "4") (pinfunction "4_4") (pintype "passive"))
      (node (ref "R104") (pin "2") (pinfunction "2_2") (pintype "passive"))
      (node (ref "R901") (pin "2") (pinfunction "2_2") (pintype "passive"))
      (node (ref "X104") (pin "5B") (pinfunction "PF8/MEMS_MISO_5B") (pintype "bidirectional"))
    )
    (net (code "37") (name "MOSI") (class "Default")
      (node (ref "IC103") (pin "13") (pinfunction "SI_13") (pintype "input"))
      (node (ref "IC104") (pin "13") (pinfunction "SI_13") (pintype "input"))
      (node (ref "IC201") (pin "15") (pinfunction "SDI_15") (pintype "input"))
      (node (ref "IC202") (pin "15") (pinfunction "SDI_15") (pintype "input"))
      (node (ref "IC203") (pin "15") (pinfunction "SDI_15") (pintype "input"))
      (node (ref "IC301") (pin "15") (pinfunction "SDI_15") (pintype "input"))
      (node (ref "IC302") (pin "15") (pinfunction "SDI_15") (pintype "input"))
      (node (ref "IC303") (pin "15") (pinfunction "SDI_15") (pintype "input"))
      (node (ref "JP103") (pin "6") (pinfunction "6_6") (pintype "passive"))
      (node (ref "R103") (pin "2") (pinfunction "2_2") (pintype "passive"))
      (node (ref "R902") (pin "2") (pinfunction "2_2") (pintype "passive"))
      (node (ref "X104") (pin "8B") (pinfunction "PF9/LCD_SDA/MEMS_MOSI_8B") (pintype "bidirectional"))
    )
    (net (code "38") (name "Net-(BUZ1-2)") (class "Default")
      (node (ref "BUZ1") (pin "-") (pinfunction "2_-") (pintype "passive"))
      (node (ref "Q101") (pin "C") (pinfunction "C_C") (pintype "passive"))
    )
    (net (code "39") (name "Net-(C601-Pad1)") (class "Default")
      (node (ref "C601") (pin "1") (pinfunction "1_1") (pintype "passive"))
      (node (ref "JP601") (pin "2") (pinfunction "2_2") (pintype "passive"))
      (node (ref "LED601") (pin "C") (pinfunction "C_C") (pintype "passive"))
      (node (ref "T601") (pin "1") (pinfunction "D_1") (pintype "passive"))
      (node (ref "T601") (pin "2") (pinfunction "D_2") (pintype "passive"))
      (node (ref "T601") (pin "5") (pinfunction "D_5") (pintype "passive"))
      (node (ref "T601") (pin "6") (pinfunction "D_6") (pintype "passive"))
      (node (ref "T601") (pin "EXP_DRAIN") (pinfunction "D_EXP_DRAIN") (pintype "passive"))
    )
    (net (code "40") (name "Net-(C602-Pad1)") (class "Default")
      (node (ref "C602") (pin "1") (pinfunction "1_1") (pintype "passive"))
      (node (ref "JP602") (pin "2") (pinfunction "2_2") (pintype "passive"))
      (node (ref "LED602") (pin "C") (pinfunction "C_C") (pintype "passive"))
      (node (ref "T602") (pin "1") (pinfunction "D_1") (pintype "passive"))
      (node (ref "T602") (pin "2") (pinfunction "D_2") (pintype "passive"))
      (node (ref "T602") (pin "5") (pinfunction "D_5") (pintype "passive"))
      (node (ref "T602") (pin "6") (pinfunction "D_6") (pintype "passive"))
      (node (ref "T602") (pin "EXP_DRAIN") (pinfunction "D_EXP_DRAIN") (pintype "passive"))
    )
    (net (code "41") (name "Net-(C603-Pad1)") (class "Default")
      (node (ref "C603") (pin "1") (pinfunction "1_1") (pintype "passive"))
      (node (ref "JP603") (pin "2") (pinfunction "2_2") (pintype "passive"))
      (node (ref "LED603") (pin "C") (pinfunction "C_C") (pintype "passive"))
      (node (ref "T603") (pin "1") (pinfunction "D_1") (pintype "passive"))
      (node (ref "T603") (pin "2") (pinfunction "D_2") (pintype "passive"))
      (node (ref "T603") (pin "5") (pinfunction "D_5") (pintype "passive"))
      (node (ref "T603") (pin "6") (pinfunction "D_6") (pintype "passive"))
      (node (ref "T603") (pin "EXP_DRAIN") (pinfunction "D_EXP_DRAIN") (pintype "passive"))
    )
    (net (code "42") (name "Net-(C604-Pad1)") (class "Default")
      (node (ref "C604") (pin "1") (pinfunction "1_1") (pintype "passive"))
      (node (ref "JP604") (pin "2") (pinfunction "2_2") (pintype "passive"))
      (node (ref "LED604") (pin "C") (pinfunction "C_C") (pintype "passive"))
      (node (ref "T604") (pin "1") (pinfunction "D_1") (pintype "passive"))
      (node (ref "T604") (pin "2") (pinfunction "D_2") (pintype "passive"))
      (node (ref "T604") (pin "5") (pinfunction "D_5") (pintype "passive"))
      (node (ref "T604") (pin "6") (pinfunction "D_6") (pintype "passive"))
      (node (ref "T604") (pin "EXP_DRAIN") (pinfunction "D_EXP_DRAIN") (pintype "passive"))
    )
    (net (code "43") (name "Net-(C605-Pad1)") (class "Default")
      (node (ref "C605") (pin "1") (pinfunction "1_1") (pintype "passive"))
      (node (ref "JP605") (pin "2") (pinfunction "2_2") (pintype "passive"))
      (node (ref "LED605") (pin "C") (pinfunction "C_C") (pintype "passive"))
      (node (ref "T605") (pin "1") (pinfunction "D_1") (pintype "passive"))
      (node (ref "T605") (pin "2") (pinfunction "D_2") (pintype "passive"))
      (node (ref "T605") (pin "5") (pinfunction "D_5") (pintype "passive"))
      (node (ref "T605") (pin "6") (pinfunction "D_6") (pintype "passive"))
      (node (ref "T605") (pin "EXP_DRAIN") (pinfunction "D_EXP_DRAIN") (pintype "passive"))
    )
    (net (code "44") (name "Net-(C702-Pad1)") (class "Default")
      (node (ref "C702") (pin "1") (pinfunction "1_1") (pintype "passive"))
      (node (ref "JP701") (pin "2") (pinfunction "2_2") (pintype "passive"))
      (node (ref "R701") (pin "2") (pinfunction "2_2") (pintype "passive"))
    )
    (net (code "45") (name "Net-(C703-Pad1)") (class "Default")
      (node (ref "C703") (pin "1") (pinfunction "1_1") (pintype "passive"))
      (node (ref "JP702") (pin "2") (pinfunction "2_2") (pintype "passive"))
      (node (ref "R702") (pin "2") (pinfunction "2_2") (pintype "passive"))
    )
    (net (code "46") (name "Net-(C704-Pad1)") (class "Default")
      (node (ref "C704") (pin "1") (pinfunction "1_1") (pintype "passive"))
      (node (ref "JP703") (pin "2") (pinfunction "2_2") (pintype "passive"))
      (node (ref "R703") (pin "2") (pinfunction "2_2") (pintype "passive"))
    )
    (net (code "47") (name "Net-(C705-Pad1)") (class "Default")
      (node (ref "C705") (pin "1") (pinfunction "1_1") (pintype "passive"))
      (node (ref "JP704") (pin "2") (pinfunction "2_2") (pintype "passive"))
      (node (ref "R704") (pin "2") (pinfunction "2_2") (pintype "passive"))
      (node (ref "R705") (pin "1") (pinfunction "1_1") (pintype "passive"))
    )
    (net (code "48") (name "Net-(C707-Pad1)") (class "Default")
      (node (ref "C707") (pin "1") (pinfunction "1_1") (pintype "passive"))
      (node (ref "JP705") (pin "2") (pinfunction "2_2") (pintype "passive"))
      (node (ref "R706") (pin "2") (pinfunction "2_2") (pintype "passive"))
    )
    (net (code "49") (name "Net-(C708-Pad1)") (class "Default")
      (node (ref "C708") (pin "1") (pinfunction "1_1") (pintype "passive"))
      (node (ref "JP707") (pin "2") (pinfunction "2_2") (pintype "passive"))
      (node (ref "R707") (pin "2") (pinfunction "2_2") (pintype "passive"))
    )
    (net (code "50") (name "Net-(C709-Pad1)") (class "Default")
      (node (ref "C709") (pin "1") (pinfunction "1_1") (pintype "passive"))
      (node (ref "JP708") (pin "2") (pinfunction "2_2") (pintype "passive"))
      (node (ref "R708") (pin "2") (pinfunction "2_2") (pintype "passive"))
    )
    (net (code "51") (name "Net-(C710-Pad1)") (class "Default")
      (node (ref "C710") (pin "1") (pinfunction "1_1") (pintype "passive"))
      (node (ref "JP706") (pin "2") (pinfunction "2_2") (pintype "passive"))
      (node (ref "R709") (pin "2") (pinfunction "2_2") (pintype "passive"))
      (node (ref "R710") (pin "1") (pinfunction "1_1") (pintype "passive"))
    )
    (net (code "52") (name "Net-(C714-Pad1)") (class "Default")
      (node (ref "C714") (pin "1") (pinfunction "1_1") (pintype "passive"))
      (node (ref "JP709") (pin "2") (pinfunction "2_2") (pintype "passive"))
      (node (ref "R711") (pin "2") (pinfunction "2_2") (pintype "passive"))
      (node (ref "R714") (pin "1") (pinfunction "1_1") (pintype "passive"))
    )
    (net (code "53") (name "Net-(C715-Pad1)") (class "Default")
      (node (ref "C715") (pin "1") (pinfunction "1_1") (pintype "passive"))
      (node (ref "JP710") (pin "2") (pinfunction "2_2") (pintype "passive"))
      (node (ref "R712") (pin "2") (pinfunction "2_2") (pintype "passive"))
      (node (ref "R715") (pin "1") (pinfunction "1_1") (pintype "passive"))
    )
    (net (code "54") (name "Net-(C716-Pad1)") (class "Default")
      (node (ref "C716") (pin "1") (pinfunction "1_1") (pintype "passive"))
      (node (ref "JP711") (pin "2") (pinfunction "2_2") (pintype "passive"))
      (node (ref "R713") (pin "2") (pinfunction "2_2") (pintype "passive"))
      (node (ref "R716") (pin "1") (pinfunction "1_1") (pintype "passive"))
    )
    (net (code "55") (name "Net-(C809-Pad2)") (class "Default")
      (node (ref "C809") (pin "2") (pinfunction "2_2") (pintype "passive"))
      (node (ref "R804") (pin "2") (pinfunction "2_2") (pintype "passive"))
    )
    (net (code "56") (name "Net-(C810-Pad2)") (class "Default")
      (node (ref "C810") (pin "2") (pinfunction "2_2") (pintype "passive"))
      (node (ref "R805") (pin "2") (pinfunction "2_2") (pintype "passive"))
    )
    (net (code "57") (name "Net-(F801-2-Pad3)") (class "Default")
      (node (ref "F801") (pin "3") (pinfunction "2_3") (pintype "passive"))
      (node (ref "F801") (pin "4") (pinfunction "2_4") (pintype "passive"))
      (node (ref "LED801") (pin "C") (pinfunction "C_C") (pintype "passive"))
      (node (ref "R801") (pin "1") (pinfunction "1_1") (pintype "passive"))
      (node (ref "T801") (pin "5") (pinfunction "D_5") (pintype "passive"))
      (node (ref "T801") (pin "6") (pinfunction "D_6") (pintype "passive"))
      (node (ref "T801") (pin "7") (pinfunction "D_7") (pintype "passive"))
      (node (ref "T801") (pin "8") (pinfunction "D_8") (pintype "passive"))
      (node (ref "T801") (pin "EXP_PAD") (pinfunction "D_EXP_PAD") (pintype "passive"))
    )
    (net (code "58") (name "Net-(IC101-HSD1+)") (class "Default")
      (node (ref "IC101") (pin "7") (pinfunction "HSD1+_7") (pintype "bidirectional"))
      (node (ref "X101") (pin "3") (pinfunction "3_3") (pintype "passive"))
    )
    (net (code "59") (name "Net-(IC101-HSD1-)") (class "Default")
      (node (ref "IC101") (pin "6") (pinfunction "HSD1-_6") (pintype "bidirectional"))
      (node (ref "X101") (pin "2") (pinfunction "2_2") (pintype "passive"))
    )
    (net (code "60") (name "Net-(IC101-HSD2+)") (class "Default")
      (node (ref "IC101") (pin "5") (pinfunction "HSD2+_5") (pintype "bidirectional"))
      (node (ref "X102") (pin "3") (pinfunction "3_3") (pintype "passive"))
    )
    (net (code "61") (name "Net-(IC101-HSD2-)") (class "Default")
      (node (ref "IC101") (pin "4") (pinfunction "HSD2-_4") (pintype "bidirectional"))
      (node (ref "X102") (pin "2") (pinfunction "2_2") (pintype "passive"))
    )
    (net (code "62") (name "Net-(IC201-5V_OUT)") (class "Default")
      (node (ref "C201") (pin "1") (pinfunction "1_1") (pintype "passive"))
      (node (ref "IC201") (pin "13") (pinfunction "5V_OUT_13") (pintype "output"))
    )
    (net (code "63") (name "Net-(IC201-BRA)") (class "Default")
      (node (ref "IC201") (pin "12") (pinfunction "SRA_12") (pintype "passive"))
      (node (ref "IC201") (pin "9") (pinfunction "BRA_9") (pintype "passive"))
      (node (ref "R201") (pin "1") (pinfunction "1_1") (pintype "passive"))
    )
    (net (code "64") (name "Net-(IC201-BRB)") (class "Default")
      (node (ref "IC201") (pin "22") (pinfunction "SRB_22") (pintype "passive"))
      (node (ref "IC201") (pin "25") (pinfunction "BRB_25") (pintype "passive"))
      (node (ref "R202") (pin "1") (pinfunction "1_1") (pintype "passive"))
    )
    (net (code "65") (name "Net-(IC201-VHS)") (class "Default")
      (node (ref "C205") (pin "1") (pinfunction "1_1") (pintype "passive"))
      (node (ref "IC201") (pin "35") (pinfunction "VHS_35") (pintype "passive"))
    )
    (net (code "66") (name "Net-(IC202-5V_OUT)") (class "Default")
      (node (ref "C202") (pin "1") (pinfunction "1_1") (pintype "passive"))
      (node (ref "IC202") (pin "13") (pinfunction "5V_OUT_13") (pintype "output"))
    )
    (net (code "67") (name "Net-(IC202-BRA)") (class "Default")
      (node (ref "IC202") (pin "12") (pinfunction "SRA_12") (pintype "passive"))
      (node (ref "IC202") (pin "9") (pinfunction "BRA_9") (pintype "passive"))
      (node (ref "R203") (pin "1") (pinfunction "1_1") (pintype "passive"))
    )
    (net (code "68") (name "Net-(IC202-BRB)") (class "Default")
      (node (ref "IC202") (pin "22") (pinfunction "SRB_22") (pintype "passive"))
      (node (ref "IC202") (pin "25") (pinfunction "BRB_25") (pintype "passive"))
      (node (ref "R204") (pin "1") (pinfunction "1_1") (pintype "passive"))
    )
    (net (code "69") (name "Net-(IC202-VHS)") (class "Default")
      (node (ref "C206") (pin "1") (pinfunction "1_1") (pintype "passive"))
      (node (ref "IC202") (pin "35") (pinfunction "VHS_35") (pintype "passive"))
    )
    (net (code "70") (name "Net-(IC203-5V_OUT)") (class "Default")
      (node (ref "C223") (pin "1") (pinfunction "1_1") (pintype "passive"))
      (node (ref "IC203") (pin "13") (pinfunction "5V_OUT_13") (pintype "output"))
    )
    (net (code "71") (name "Net-(IC203-BRA)") (class "Default")
      (node (ref "IC203") (pin "12") (pinfunction "SRA_12") (pintype "passive"))
      (node (ref "IC203") (pin "9") (pinfunction "BRA_9") (pintype "passive"))
      (node (ref "R205") (pin "1") (pinfunction "1_1") (pintype "passive"))
    )
    (net (code "72") (name "Net-(IC203-BRB)") (class "Default")
      (node (ref "IC203") (pin "22") (pinfunction "SRB_22") (pintype "passive"))
      (node (ref "IC203") (pin "25") (pinfunction "BRB_25") (pintype "passive"))
      (node (ref "R206") (pin "1") (pinfunction "1_1") (pintype "passive"))
    )
    (net (code "73") (name "Net-(IC203-VHS)") (class "Default")
      (node (ref "C225") (pin "1") (pinfunction "1_1") (pintype "passive"))
      (node (ref "IC203") (pin "35") (pinfunction "VHS_35") (pintype "passive"))
    )
    (net (code "74") (name "Net-(IC301-5V_OUT)") (class "Default")
      (node (ref "C301") (pin "1") (pinfunction "1_1") (pintype "passive"))
      (node (ref "IC301") (pin "13") (pinfunction "5V_OUT_13") (pintype "output"))
    )
    (net (code "75") (name "Net-(IC301-BRA)") (class "Default")
      (node (ref "IC301") (pin "12") (pinfunction "SRA_12") (pintype "passive"))
      (node (ref "IC301") (pin "9") (pinfunction "BRA_9") (pintype "passive"))
      (node (ref "R301") (pin "1") (pinfunction "1_1") (pintype "passive"))
    )
    (net (code "76") (name "Net-(IC301-BRB)") (class "Default")
      (node (ref "IC301") (pin "22") (pinfunction "SRB_22") (pintype "passive"))
      (node (ref "IC301") (pin "25") (pinfunction "BRB_25") (pintype "passive"))
      (node (ref "R302") (pin "1") (pinfunction "1_1") (pintype "passive"))
    )
    (net (code "77") (name "Net-(IC301-VHS)") (class "Default")
      (node (ref "C305") (pin "1") (pinfunction "1_1") (pintype "passive"))
      (node (ref "IC301") (pin "35") (pinfunction "VHS_35") (pintype "passive"))
    )
    (net (code "78") (name "Net-(IC302-5V_OUT)") (class "Default")
      (node (ref "C302") (pin "1") (pinfunction "1_1") (pintype "passive"))
      (node (ref "IC302") (pin "13") (pinfunction "5V_OUT_13") (pintype "output"))
    )
    (net (code "79") (name "Net-(IC302-BRA)") (class "Default")
      (node (ref "IC302") (pin "12") (pinfunction "SRA_12") (pintype "passive"))
      (node (ref "IC302") (pin "9") (pinfunction "BRA_9") (pintype "passive"))
      (node (ref "R303") (pin "1") (pinfunction "1_1") (pintype "passive"))
    )
    (net (code "80") (name "Net-(IC302-BRB)") (class "Default")
      (node (ref "IC302") (pin "22") (pinfunction "SRB_22") (pintype "passive"))
      (node (ref "IC302") (pin "25") (pinfunction "BRB_25") (pintype "passive"))
      (node (ref "R304") (pin "1") (pinfunction "1_1") (pintype "passive"))
    )
    (net (code "81") (name "Net-(IC302-VHS)") (class "Default")
      (node (ref "C306") (pin "1") (pinfunction "1_1") (pintype "passive"))
      (node (ref "IC302") (pin "35") (pinfunction "VHS_35") (pintype "passive"))
    )
    (net (code "82") (name "Net-(IC303-5V_OUT)") (class "Default")
      (node (ref "C323") (pin "1") (pinfunction "1_1") (pintype "passive"))
      (node (ref "IC303") (pin "13") (pinfunction "5V_OUT_13") (pintype "output"))
    )
    (net (code "83") (name "Net-(IC303-BRA)") (class "Default")
      (node (ref "IC303") (pin "12") (pinfunction "SRA_12") (pintype "passive"))
      (node (ref "IC303") (pin "9") (pinfunction "BRA_9") (pintype "passive"))
      (node (ref "R305") (pin "1") (pinfunction "1_1") (pintype "passive"))
    )
    (net (code "84") (name "Net-(IC303-BRB)") (class "Default")
      (node (ref "IC303") (pin "22") (pinfunction "SRB_22") (pintype "passive"))
      (node (ref "IC303") (pin "25") (pinfunction "BRB_25") (pintype "passive"))
      (node (ref "R306") (pin "1") (pinfunction "1_1") (pintype "passive"))
    )
    (net (code "85") (name "Net-(IC303-VHS)") (class "Default")
      (node (ref "C325") (pin "1") (pinfunction "1_1") (pintype "passive"))
      (node (ref "IC303") (pin "35") (pinfunction "VHS_35") (pintype "passive"))
    )
    (net (code "86") (name "Net-(IC401-O)") (class "Default")
      (node (ref "IC401") (pin "5") (pinfunction "O_5") (pintype "output"))
      (node (ref "R402") (pin "1") (pinfunction "1_1") (pintype "passive"))
    )
    (net (code "87") (name "Net-(IC801-BOOT)") (class "Default")
      (node (ref "C813") (pin "1") (pinfunction "1_1") (pintype "passive"))
      (node (ref "IC801") (pin "1") (pinfunction "BOOT_1") (pintype "output"))
    )
    (net (code "88") (name "Net-(IC801-COMP)") (class "Default")
      (node (ref "C807") (pin "1") (pinfunction "1_1") (pintype "passive"))
      (node (ref "C809") (pin "1") (pinfunction "1_1") (pintype "passive"))
      (node (ref "IC801") (pin "6") (pinfunction "COMP_6") (pintype "output"))
    )
    (net (code "89") (name "Net-(IC801-PH)") (class "Default")
      (node (ref "C813") (pin "2") (pinfunction "2_2") (pintype "passive"))
      (node (ref "D802") (pin "C") (pinfunction "C_C") (pintype "passive"))
      (node (ref "IC801") (pin "8") (pinfunction "PH_8") (pintype "output"))
      (node (ref "L802") (pin "1") (pinfunction "1_1") (pintype "passive"))
    )
    (net (code "90") (name "Net-(IC801-SS)") (class "Default")
      (node (ref "C811") (pin "1") (pinfunction "1_1") (pintype "passive"))
      (node (ref "IC801") (pin "4") (pinfunction "SS_4") (pintype "input"))
    )
    (net (code "91") (name "Net-(IC801-VSENSE)") (class "Default")
      (node (ref "IC801") (pin "5") (pinfunction "VSENSE_5") (pintype "input"))
      (node (ref "R806") (pin "1") (pinfunction "1_1") (pintype "passive"))
      (node (ref "R807") (pin "2") (pinfunction "2_2") (pintype "passive"))
    )
    (net (code "92") (name "Net-(IC802-BOOT)") (class "Default")
      (node (ref "C814") (pin "1") (pinfunction "1_1") (pintype "passive"))
      (node (ref "IC802") (pin "1") (pinfunction "BOOT_1") (pintype "output"))
    )
    (net (code "93") (name "Net-(IC802-COMP)") (class "Default")
      (node (ref "C808") (pin "1") (pinfunction "1_1") (pintype "passive"))
      (node (ref "C810") (pin "1") (pinfunction "1_1") (pintype "passive"))
      (node (ref "IC802") (pin "6") (pinfunction "COMP_6") (pintype "output"))
    )
    (net (code "94") (name "Net-(IC802-PH)") (class "Default")
      (node (ref "C814") (pin "2") (pinfunction "2_2") (pintype "passive"))
      (node (ref "D803") (pin "C") (pinfunction "C_C") (pintype "passive"))
      (node (ref "IC802") (pin "8") (pinfunction "PH_8") (pintype "output"))
      (node (ref "L803") (pin "1") (pinfunction "1_1") (pintype "passive"))
    )
    (net (code "95") (name "Net-(IC802-SS)") (class "Default")
      (node (ref "C812") (pin "1") (pinfunction "1_1") (pintype "passive"))
      (node (ref "IC802") (pin "4") (pinfunction "SS_4") (pintype "input"))
    )
    (net (code "96") (name "Net-(IC802-VSENSE)") (class "Default")
      (node (ref "IC802") (pin "5") (pinfunction "VSENSE_5") (pintype "input"))
      (node (ref "R808") (pin "1") (pinfunction "1_1") (pintype "passive"))
      (node (ref "R809") (pin "2") (pinfunction "2_2") (pintype "passive"))
    )
    (net (code "97") (name "Net-(LED401-PadA)") (class "Default")
      (node (ref "LED401") (pin "A") (pinfunction "A_A") (pintype "passive"))
      (node (ref "R403") (pin "2") (pinfunction "2_2") (pintype "passive"))
    )
    (net (code "98") (name "Net-(LED501-PadA)") (class "Default")
      (node (ref "LED501") (pin "A") (pinfunction "A_A") (pintype "passive"))
      (node (ref "R501") (pin "2") (pinfunction "2_2") (pintype "passive"))
    )
    (net (code "99") (name "Net-(LED502-PadA)") (class "Default")
      (node (ref "LED502") (pin "A") (pinfunction "A_A") (pintype "passive"))
      (node (ref "R506") (pin "2") (pinfunction "2_2") (pintype "passive"))
    )
    (net (code "100") (name "Net-(LED503-PadA)") (class "Default")
      (node (ref "LED503") (pin "A") (pinfunction "A_A") (pintype "passive"))
      (node (ref "R507") (pin "2") (pinfunction "2_2") (pintype "passive"))
    )
    (net (code "101") (name "Net-(LED504-PadA)") (class "Default")
      (node (ref "LED504") (pin "A") (pinfunction "A_A") (pintype "passive"))
      (node (ref "R510") (pin "2") (pinfunction "2_2") (pintype "passive"))
    )
    (net (code "102") (name "Net-(LED601-PadA)") (class "Default")
      (node (ref "LED601") (pin "A") (pinfunction "A_A") (pintype "passive"))
      (node (ref "R605") (pin "2") (pinfunction "2_2") (pintype "passive"))
    )
    (net (code "103") (name "Net-(LED602-PadA)") (class "Default")
      (node (ref "LED602") (pin "A") (pinfunction "A_A") (pintype "passive"))
      (node (ref "R606") (pin "2") (pinfunction "2_2") (pintype "passive"))
    )
    (net (code "104") (name "Net-(LED603-PadA)") (class "Default")
      (node (ref "LED603") (pin "A") (pinfunction "A_A") (pintype "passive"))
      (node (ref "R611") (pin "2") (pinfunction "2_2") (pintype "passive"))
    )
    (net (code "105") (name "Net-(LED604-PadA)") (class "Default")
      (node (ref "LED604") (pin "A") (pinfunction "A_A") (pintype "passive"))
      (node (ref "R612") (pin "2") (pinfunction "2_2") (pintype "passive"))
    )
    (net (code "106") (name "Net-(LED605-PadA)") (class "Default")
      (node (ref "LED605") (pin "A") (pinfunction "A_A") (pintype "passive"))
      (node (ref "R615") (pin "2") (pinfunction "2_2") (pintype "passive"))
    )
    (net (code "107") (name "Net-(LED801-PadA)") (class "Default")
      (node (ref "LED801") (pin "A") (pinfunction "A_A") (pintype "passive"))
      (node (ref "R802") (pin "2") (pinfunction "2_2") (pintype "passive"))
    )
    (net (code "108") (name "Net-(Q101-PadB)") (class "Default")
      (node (ref "Q101") (pin "B") (pinfunction "B_B") (pintype "passive"))
      (node (ref "R102") (pin "1") (pinfunction "1_1") (pintype "passive"))
    )
    (net (code "109") (name "Net-(Q102-PadB)") (class "Default")
      (node (ref "Q102") (pin "B") (pinfunction "B_B") (pintype "passive"))
      (node (ref "R107") (pin "1") (pinfunction "1_1") (pintype "passive"))
    )
    (net (code "110") (name "Net-(T401-G)") (class "Default")
      (node (ref "R402") (pin "2") (pinfunction "2_2") (pintype "passive"))
      (node (ref "T401") (pin "4") (pinfunction "G_4") (pintype "passive"))
    )
    (net (code "111") (name "Net-(T501-G)") (class "Default")
      (node (ref "R504") (pin "2") (pinfunction "2_2") (pintype "passive"))
      (node (ref "T501") (pin "3") (pinfunction "G_3") (pintype "passive"))
    )
    (net (code "112") (name "Net-(T502-G)") (class "Default")
      (node (ref "R505") (pin "2") (pinfunction "2_2") (pintype "passive"))
      (node (ref "T502") (pin "3") (pinfunction "G_3") (pintype "passive"))
    )
    (net (code "113") (name "Net-(T503-G)") (class "Default")
      (node (ref "R509") (pin "2") (pinfunction "2_2") (pintype "passive"))
      (node (ref "T503") (pin "3") (pinfunction "G_3") (pintype "passive"))
    )
    (net (code "114") (name "Net-(T601-G)") (class "Default")
      (node (ref "R603") (pin "2") (pinfunction "2_2") (pintype "passive"))
      (node (ref "T601") (pin "3") (pinfunction "G_3") (pintype "passive"))
    )
    (net (code "115") (name "Net-(T602-G)") (class "Default")
      (node (ref "R604") (pin "2") (pinfunction "2_2") (pintype "passive"))
      (node (ref "T602") (pin "3") (pinfunction "G_3") (pintype "passive"))
    )
    (net (code "116") (name "Net-(T603-G)") (class "Default")
      (node (ref "R608") (pin "2") (pinfunction "2_2") (pintype "passive"))
      (node (ref "T603") (pin "3") (pinfunction "G_3") (pintype "passive"))
    )
    (net (code "117") (name "Net-(T604-G)") (class "Default")
      (node (ref "R610") (pin "2") (pinfunction "2_2") (pintype "passive"))
      (node (ref "T604") (pin "3") (pinfunction "G_3") (pintype "passive"))
    )
    (net (code "118") (name "Net-(T605-G)") (class "Default")
      (node (ref "R614") (pin "2") (pinfunction "2_2") (pintype "passive"))
      (node (ref "T605") (pin "3") (pinfunction "G_3") (pintype "passive"))
    )
    (net (code "119") (name "Net-(T801-G)") (class "Default")
      (node (ref "D801") (pin "A") (pinfunction "A_A") (pintype "passive"))
      (node (ref "R803") (pin "2") (pinfunction "2_2") (pintype "passive"))
      (node (ref "T801") (pin "4") (pinfunction "G_4") (pintype "passive"))
    )
    (net (code "120") (name "Net-(X101-S1)") (class "Default")
      (node (ref "R101") (pin "1") (pinfunction "1_1") (pintype "passive"))
      (node (ref "X101") (pin "5") (pinfunction "S1_5") (pintype "passive"))
      (node (ref "X101") (pin "6") (pinfunction "S2_6") (pintype "passive"))
      (node (ref "X102") (pin "5") (pinfunction "S1_5") (pintype "passive"))
      (node (ref "X102") (pin "6") (pinfunction "S2_6") (pintype "passive"))
    )
    (net (code "121") (name "Net-(X103-CD{slash}DAT3)") (class "Default")
      (node (ref "R105") (pin "1") (pinfunction "1_1") (pintype "passive"))
      (node (ref "X103") (pin "1") (pinfunction "CD/DAT3_1") (pintype "bidirectional"))
    )
    (net (code "122") (name "Net-(X201A-KL)") (class "Default")
      (node (ref "C210") (pin "1") (pinfunction "1_1") (pintype "passive"))
      (node (ref "IC201") (pin "2") (pinfunction "OA1_2") (pintype "output"))
      (node (ref "IC201") (pin "3") (pinfunction "OA1_3") (pintype "output"))
      (node (ref "IC201") (pin "7") (pinfunction "OA1_7") (pintype "output"))
      (node (ref "IC201") (pin "8") (pinfunction "OA1_8") (pintype "output"))
      (node (ref "X201") (pin "1") (pinfunction "KL_1") (pintype "passive"))
    )
    (net (code "123") (name "Net-(X201B-KL)") (class "Default")
      (node (ref "C213") (pin "1") (pinfunction "1_1") (pintype "passive"))
      (node (ref "IC201") (pin "10") (pinfunction "OA2_10") (pintype "output"))
      (node (ref "IC201") (pin "11") (pinfunction "OA2_11") (pintype "output"))
      (node (ref "IC201") (pin "5") (pinfunction "OA2_5") (pintype "output"))
      (node (ref "IC201") (pin "6") (pinfunction "OA2_6") (pintype "output"))
      (node (ref "X201") (pin "2") (pinfunction "KL_2") (pintype "passive"))
    )
    (net (code "124") (name "Net-(X201C-KL)") (class "Default")
      (node (ref "C215") (pin "1") (pinfunction "1_1") (pintype "passive"))
      (node (ref "IC201") (pin "23") (pinfunction "OB2_23") (pintype "output"))
      (node (ref "IC201") (pin "24") (pinfunction "OB2_24") (pintype "output"))
      (node (ref "IC201") (pin "28") (pinfunction "OB2_28") (pintype "output"))
      (node (ref "IC201") (pin "29") (pinfunction "OB2_29") (pintype "output"))
      (node (ref "X201") (pin "3") (pinfunction "KL_3") (pintype "passive"))
    )
    (net (code "125") (name "Net-(X201D-KL)") (class "Default")
      (node (ref "C219") (pin "1") (pinfunction "1_1") (pintype "passive"))
      (node (ref "IC201") (pin "26") (pinfunction "OB1_26") (pintype "output"))
      (node (ref "IC201") (pin "27") (pinfunction "OB1_27") (pintype "output"))
      (node (ref "IC201") (pin "31") (pinfunction "OB1_31") (pintype "output"))
      (node (ref "IC201") (pin "32") (pinfunction "OB1_32") (pintype "output"))
      (node (ref "X201") (pin "4") (pinfunction "KL_4") (pintype "passive"))
    )
    (net (code "126") (name "Net-(X202A-KL)") (class "Default")
      (node (ref "C212") (pin "1") (pinfunction "1_1") (pintype "passive"))
      (node (ref "IC202") (pin "2") (pinfunction "OA1_2") (pintype "output"))
      (node (ref "IC202") (pin "3") (pinfunction "OA1_3") (pintype "output"))
      (node (ref "IC202") (pin "7") (pinfunction "OA1_7") (pintype "output"))
      (node (ref "IC202") (pin "8") (pinfunction "OA1_8") (pintype "output"))
      (node (ref "X202") (pin "1") (pinfunction "KL_1") (pintype "passive"))
    )
    (net (code "127") (name "Net-(X202B-KL)") (class "Default")
      (node (ref "C214") (pin "1") (pinfunction "1_1") (pintype "passive"))
      (node (ref "IC202") (pin "10") (pinfunction "OA2_10") (pintype "output"))
      (node (ref "IC202") (pin "11") (pinfunction "OA2_11") (pintype "output"))
      (node (ref "IC202") (pin "5") (pinfunction "OA2_5") (pintype "output"))
      (node (ref "IC202") (pin "6") (pinfunction "OA2_6") (pintype "output"))
      (node (ref "X202") (pin "2") (pinfunction "KL_2") (pintype "passive"))
    )
    (net (code "128") (name "Net-(X202C-KL)") (class "Default")
      (node (ref "C216") (pin "1") (pinfunction "1_1") (pintype "passive"))
      (node (ref "IC202") (pin "23") (pinfunction "OB2_23") (pintype "output"))
      (node (ref "IC202") (pin "24") (pinfunction "OB2_24") (pintype "output"))
      (node (ref "IC202") (pin "28") (pinfunction "OB2_28") (pintype "output"))
      (node (ref "IC202") (pin "29") (pinfunction "OB2_29") (pintype "output"))
      (node (ref "X202") (pin "3") (pinfunction "KL_3") (pintype "passive"))
    )
    (net (code "129") (name "Net-(X202D-KL)") (class "Default")
      (node (ref "C220") (pin "1") (pinfunction "1_1") (pintype "passive"))
      (node (ref "IC202") (pin "26") (pinfunction "OB1_26") (pintype "output"))
      (node (ref "IC202") (pin "27") (pinfunction "OB1_27") (pintype "output"))
      (node (ref "IC202") (pin "31") (pinfunction "OB1_31") (pintype "output"))
      (node (ref "IC202") (pin "32") (pinfunction "OB1_32") (pintype "output"))
      (node (ref "X202") (pin "4") (pinfunction "KL_4") (pintype "passive"))
    )
    (net (code "130") (name "Net-(X203A-KL)") (class "Default")
      (node (ref "C228") (pin "1") (pinfunction "1_1") (pintype "passive"))
      (node (ref "IC203") (pin "2") (pinfunction "OA1_2") (pintype "output"))
      (node (ref "IC203") (pin "3") (pinfunction "OA1_3") (pintype "output"))
      (node (ref "IC203") (pin "7") (pinfunction "OA1_7") (pintype "output"))
      (node (ref "IC203") (pin "8") (pinfunction "OA1_8") (pintype "output"))
      (node (ref "X203") (pin "1") (pinfunction "KL_1") (pintype "passive"))
    )
    (net (code "131") (name "Net-(X203B-KL)") (class "Default")
      (node (ref "C229") (pin "1") (pinfunction "1_1") (pintype "passive"))
      (node (ref "IC203") (pin "10") (pinfunction "OA2_10") (pintype "output"))
      (node (ref "IC203") (pin "11") (pinfunction "OA2_11") (pintype "output"))
      (node (ref "IC203") (pin "5") (pinfunction "OA2_5") (pintype "output"))
      (node (ref "IC203") (pin "6") (pinfunction "OA2_6") (pintype "output"))
      (node (ref "X203") (pin "2") (pinfunction "KL_2") (pintype "passive"))
    )
    (net (code "132") (name "Net-(X203C-KL)") (class "Default")
      (node (ref "C230") (pin "1") (pinfunction "1_1") (pintype "passive"))
      (node (ref "IC203") (pin "23") (pinfunction "OB2_23") (pintype "output"))
      (node (ref "IC203") (pin "24") (pinfunction "OB2_24") (pintype "output"))
      (node (ref "IC203") (pin "28") (pinfunction "OB2_28") (pintype "output"))
      (node (ref "IC203") (pin "29") (pinfunction "OB2_29") (pintype "output"))
      (node (ref "X203") (pin "3") (pinfunction "KL_3") (pintype "passive"))
    )
    (net (code "133") (name "Net-(X203D-KL)") (class "Default")
      (node (ref "C232") (pin "1") (pinfunction "1_1") (pintype "passive"))
      (node (ref "IC203") (pin "26") (pinfunction "OB1_26") (pintype "output"))
      (node (ref "IC203") (pin "27") (pinfunction "OB1_27") (pintype "output"))
      (node (ref "IC203") (pin "31") (pinfunction "OB1_31") (pintype "output"))
      (node (ref "IC203") (pin "32") (pinfunction "OB1_32") (pintype "output"))
      (node (ref "X203") (pin "4") (pinfunction "KL_4") (pintype "passive"))
    )
    (net (code "134") (name "Net-(X301A-KL)") (class "Default")
      (node (ref "C310") (pin "1") (pinfunction "1_1") (pintype "passive"))
      (node (ref "IC301") (pin "2") (pinfunction "OA1_2") (pintype "output"))
      (node (ref "IC301") (pin "3") (pinfunction "OA1_3") (pintype "output"))
      (node (ref "IC301") (pin "7") (pinfunction "OA1_7") (pintype "output"))
      (node (ref "IC301") (pin "8") (pinfunction "OA1_8") (pintype "output"))
      (node (ref "X301") (pin "1") (pinfunction "KL_1") (pintype "passive"))
    )
    (net (code "135") (name "Net-(X301B-KL)") (class "Default")
      (node (ref "C313") (pin "1") (pinfunction "1_1") (pintype "passive"))
      (node (ref "IC301") (pin "10") (pinfunction "OA2_10") (pintype "output"))
      (node (ref "IC301") (pin "11") (pinfunction "OA2_11") (pintype "output"))
      (node (ref "IC301") (pin "5") (pinfunction "OA2_5") (pintype "output"))
      (node (ref "IC301") (pin "6") (pinfunction "OA2_6") (pintype "output"))
      (node (ref "X301") (pin "2") (pinfunction "KL_2") (pintype "passive"))
    )
    (net (code "136") (name "Net-(X301C-KL)") (class "Default")
      (node (ref "C315") (pin "1") (pinfunction "1_1") (pintype "passive"))
      (node (ref "IC301") (pin "23") (pinfunction "OB2_23") (pintype "output"))
      (node (ref "IC301") (pin "24") (pinfunction "OB2_24") (pintype "output"))
      (node (ref "IC301") (pin "28") (pinfunction "OB2_28") (pintype "output"))
      (node (ref "IC301") (pin "29") (pinfunction "OB2_29") (pintype "output"))
      (node (ref "X301") (pin "3") (pinfunction "KL_3") (pintype "passive"))
    )
    (net (code "137") (name "Net-(X301D-KL)") (class "Default")
      (node (ref "C319") (pin "1") (pinfunction "1_1") (pintype "passive"))
      (node (ref "IC301") (pin "26") (pinfunction "OB1_26") (pintype "output"))
      (node (ref "IC301") (pin "27") (pinfunction "OB1_27") (pintype "output"))
      (node (ref "IC301") (pin "31") (pinfunction "OB1_31") (pintype "output"))
      (node (ref "IC301") (pin "32") (pinfunction "OB1_32") (pintype "output"))
      (node (ref "X301") (pin "4") (pinfunction "KL_4") (pintype "passive"))
    )
    (net (code "138") (name "Net-(X302A-KL)") (class "Default")
      (node (ref "C312") (pin "1") (pinfunction "1_1") (pintype "passive"))
      (node (ref "IC302") (pin "2") (pinfunction "OA1_2") (pintype "output"))
      (node (ref "IC302") (pin "3") (pinfunction "OA1_3") (pintype "output"))
      (node (ref "IC302") (pin "7") (pinfunction "OA1_7") (pintype "output"))
      (node (ref "IC302") (pin "8") (pinfunction "OA1_8") (pintype "output"))
      (node (ref "X302") (pin "1") (pinfunction "KL_1") (pintype "passive"))
    )
    (net (code "139") (name "Net-(X302B-KL)") (class "Default")
      (node (ref "C314") (pin "1") (pinfunction "1_1") (pintype "passive"))
      (node (ref "IC302") (pin "10") (pinfunction "OA2_10") (pintype "output"))
      (node (ref "IC302") (pin "11") (pinfunction "OA2_11") (pintype "output"))
      (node (ref "IC302") (pin "5") (pinfunction "OA2_5") (pintype "output"))
      (node (ref "IC302") (pin "6") (pinfunction "OA2_6") (pintype "output"))
      (node (ref "X302") (pin "2") (pinfunction "KL_2") (pintype "passive"))
    )
    (net (code "140") (name "Net-(X302C-KL)") (class "Default")
      (node (ref "C316") (pin "1") (pinfunction "1_1") (pintype "passive"))
      (node (ref "IC302") (pin "23") (pinfunction "OB2_23") (pintype "output"))
      (node (ref "IC302") (pin "24") (pinfunction "OB2_24") (pintype "output"))
      (node (ref "IC302") (pin "28") (pinfunction "OB2_28") (pintype "output"))
      (node (ref "IC302") (pin "29") (pinfunction "OB2_29") (pintype "output"))
      (node (ref "X302") (pin "3") (pinfunction "KL_3") (pintype "passive"))
    )
    (net (code "141") (name "Net-(X302D-KL)") (class "Default")
      (node (ref "C320") (pin "1") (pinfunction "1_1") (pintype "passive"))
      (node (ref "IC302") (pin "26") (pinfunction "OB1_26") (pintype "output"))
      (node (ref "IC302") (pin "27") (pinfunction "OB1_27") (pintype "output"))
      (node (ref "IC302") (pin "31") (pinfunction "OB1_31") (pintype "output"))
      (node (ref "IC302") (pin "32") (pinfunction "OB1_32") (pintype "output"))
      (node (ref "X302") (pin "4") (pinfunction "KL_4") (pintype "passive"))
    )
    (net (code "142") (name "Net-(X303A-KL)") (class "Default")
      (node (ref "C328") (pin "1") (pinfunction "1_1") (pintype "passive"))
      (node (ref "IC303") (pin "2") (pinfunction "OA1_2") (pintype "output"))
      (node (ref "IC303") (pin "3") (pinfunction "OA1_3") (pintype "output"))
      (node (ref "IC303") (pin "7") (pinfunction "OA1_7") (pintype "output"))
      (node (ref "IC303") (pin "8") (pinfunction "OA1_8") (pintype "output"))
      (node (ref "X303") (pin "1") (pinfunction "KL_1") (pintype "passive"))
    )
    (net (code "143") (name "Net-(X303B-KL)") (class "Default")
      (node (ref "C329") (pin "1") (pinfunction "1_1") (pintype "passive"))
      (node (ref "IC303") (pin "10") (pinfunction "OA2_10") (pintype "output"))
      (node (ref "IC303") (pin "11") (pinfunction "OA2_11") (pintype "output"))
      (node (ref "IC303") (pin "5") (pinfunction "OA2_5") (pintype "output"))
      (node (ref "IC303") (pin "6") (pinfunction "OA2_6") (pintype "output"))
      (node (ref "X303") (pin "2") (pinfunction "KL_2") (pintype "passive"))
    )
    (net (code "144") (name "Net-(X303C-KL)") (class "Default")
      (node (ref "C330") (pin "1") (pinfunction "1_1") (pintype "passive"))
      (node (ref "IC303") (pin "23") (pinfunction "OB2_23") (pintype "output"))
      (node (ref "IC303") (pin "24") (pinfunction "OB2_24") (pintype "output"))
      (node (ref "IC303") (pin "28") (pinfunction "OB2_28") (pintype "output"))
      (node (ref "IC303") (pin "29") (pinfunction "OB2_29") (pintype "output"))
      (node (ref "X303") (pin "3") (pinfunction "KL_3") (pintype "passive"))
    )
    (net (code "145") (name "Net-(X303D-KL)") (class "Default")
      (node (ref "C332") (pin "1") (pinfunction "1_1") (pintype "passive"))
      (node (ref "IC303") (pin "26") (pinfunction "OB1_26") (pintype "output"))
      (node (ref "IC303") (pin "27") (pinfunction "OB1_27") (pintype "output"))
      (node (ref "IC303") (pin "31") (pinfunction "OB1_31") (pintype "output"))
      (node (ref "IC303") (pin "32") (pinfunction "OB1_32") (pintype "output"))
      (node (ref "X303") (pin "4") (pinfunction "KL_4") (pintype "passive"))
    )
    (net (code "146") (name "Net-(X401C-KL)") (class "Default")
      (node (ref "C403") (pin "1") (pinfunction "1_1") (pintype "passive"))
      (node (ref "D401") (pin "A") (pinfunction "A_A") (pintype "passive"))
      (node (ref "LED401") (pin "C") (pinfunction "C_C") (pintype "passive"))
      (node (ref "T401") (pin "5") (pinfunction "D_5") (pintype "passive"))
      (node (ref "T401") (pin "6") (pinfunction "D_6") (pintype "passive"))
      (node (ref "T401") (pin "7") (pinfunction "D_7") (pintype "passive"))
      (node (ref "T401") (pin "8") (pinfunction "D_8") (pintype "passive"))
      (node (ref "T401") (pin "EXP_PAD") (pinfunction "D_EXP_PAD") (pintype "passive"))
      (node (ref "X401") (pin "3") (pinfunction "KL_3") (pintype "passive"))
      (node (ref "X401") (pin "4") (pinfunction "KL_4") (pintype "passive"))
    )
    (net (code "147") (name "Net-(X501A-KL)") (class "Default")
      (node (ref "C501") (pin "1") (pinfunction "1_1") (pintype "passive"))
      (node (ref "D501") (pin "A") (pinfunction "A_A") (pintype "passive"))
      (node (ref "LED502") (pin "C") (pinfunction "C_C") (pintype "passive"))
      (node (ref "T501") (pin "1") (pinfunction "D_1") (pintype "passive"))
      (node (ref "T501") (pin "2") (pinfunction "D_2") (pintype "passive"))
      (node (ref "T501") (pin "5") (pinfunction "D_5") (pintype "passive"))
      (node (ref "T501") (pin "6") (pinfunction "D_6") (pintype "passive"))
      (node (ref "T501") (pin "EXP_DRAIN") (pinfunction "D_EXP_DRAIN") (pintype "passive"))
      (node (ref "X501") (pin "1") (pinfunction "KL_1") (pintype "passive"))
    )
    (net (code "148") (name "Net-(X502A-KL)") (class "Default")
      (node (ref "C502") (pin "1") (pinfunction "1_1") (pintype "passive"))
      (node (ref "D502") (pin "A") (pinfunction "A_A") (pintype "passive"))
      (node (ref "LED503") (pin "C") (pinfunction "C_C") (pintype "passive"))
      (node (ref "T502") (pin "1") (pinfunction "D_1") (pintype "passive"))
      (node (ref "T502") (pin "2") (pinfunction "D_2") (pintype "passive"))
      (node (ref "T502") (pin "5") (pinfunction "D_5") (pintype "passive"))
      (node (ref "T502") (pin "6") (pinfunction "D_6") (pintype "passive"))
      (node (ref "T502") (pin "EXP_DRAIN") (pinfunction "D_EXP_DRAIN") (pintype "passive"))
      (node (ref "X502") (pin "1") (pinfunction "KL_1") (pintype "passive"))
    )
    (net (code "149") (name "Net-(X503A-KL)") (class "Default")
      (node (ref "C503") (pin "1") (pinfunction "1_1") (pintype "passive"))
      (node (ref "D503") (pin "A") (pinfunction "A_A") (pintype "passive"))
      (node (ref "LED504") (pin "C") (pinfunction "C_C") (pintype "passive"))
      (node (ref "T503") (pin "1") (pinfunction "D_1") (pintype "passive"))
      (node (ref "T503") (pin "2") (pinfunction "D_2") (pintype "passive"))
      (node (ref "T503") (pin "5") (pinfunction "D_5") (pintype "passive"))
      (node (ref "T503") (pin "6") (pinfunction "D_6") (pintype "passive"))
      (node (ref "T503") (pin "EXP_DRAIN") (pinfunction "D_EXP_DRAIN") (pintype "passive"))
      (node (ref "X503") (pin "1") (pinfunction "KL_1") (pintype "passive"))
    )
    (net (code "150") (name "Net-(X801-12V$1)") (class "Default")
      (node (ref "F801") (pin "1") (pinfunction "1_1") (pintype "passive"))
      (node (ref "F801") (pin "2") (pinfunction "1_2") (pintype "passive"))
      (node (ref "R802") (pin "1") (pinfunction "1_1") (pintype "passive"))
      (node (ref "X801") (pin "3") (pinfunction "12V$1_3") (pintype "power_in"))
      (node (ref "X801") (pin "4") (pinfunction "12V$2_4") (pintype "power_in"))
      (node (ref "X802") (pin "3") (pinfunction "KL_3") (pintype "passive"))
      (node (ref "X802") (pin "4") (pinfunction "KL_4") (pintype "passive"))
    )
    (net (code "151") (name "OTG_D+") (class "Default")
      (node (ref "IC101") (pin "1") (pinfunction "D+_1") (pintype "bidirectional"))
      (node (ref "X104") (pin "51B") (pinfunction "PB15_OTG_D+_51B") (pintype "bidirectional"))
    )
    (net (code "152") (name "OTG_D-") (class "Default")
      (node (ref "IC101") (pin "2") (pinfunction "D-_2") (pintype "bidirectional"))
      (node (ref "X104") (pin "52B") (pinfunction "PB14_OTG_D-_52B") (pintype "bidirectional"))
    )
    (net (code "153") (name "OTG_ID") (class "Default")
      (node (ref "Q102") (pin "C") (pinfunction "C_C") (pintype "passive"))
      (node (ref "X104") (pin "50B") (pinfunction "PB12_OTG_ID_50B") (pintype "input"))
    )
    (net (code "154") (name "OTG_VBUS") (class "Default")
      (node (ref "X102") (pin "1") (pinfunction "1_1") (pintype "passive"))
      (node (ref "X104") (pin "49B") (pinfunction "PB13_OTG_VBUS_49B") (pintype "passive"))
    )
    (net (code "155") (name "SCK") (class "Default")
      (node (ref "IC103") (pin "12") (pinfunction "SCK_12") (pintype "input"))
      (node (ref "IC104") (pin "12") (pinfunction "SCK_12") (pintype "input"))
      (node (ref "IC201") (pin "16") (pinfunction "SCK_16") (pintype "input"))
      (node (ref "IC202") (pin "16") (pinfunction "SCK_16") (pintype "input"))
      (node (ref "IC203") (pin "16") (pinfunction "SCK_16") (pintype "input"))
      (node (ref "IC301") (pin "16") (pinfunction "SCK_16") (pintype "input"))
      (node (ref "IC302") (pin "16") (pinfunction "SCK_16") (pintype "input"))
      (node (ref "IC303") (pin "16") (pinfunction "SCK_16") (pintype "input"))
      (node (ref "JP103") (pin "2") (pinfunction "2_2") (pintype "passive"))
      (node (ref "R106") (pin "2") (pinfunction "2_2") (pintype "passive"))
      (node (ref "R903") (pin "2") (pinfunction "2_2") (pintype "passive"))
      (node (ref "X104") (pin "6B") (pinfunction "PF7_LCD_DCX_SCL_SCK_6B") (pintype "bidirectional"))
    )
    (net (code "156") (name "SCL") (class "Default")
      (node (ref "IC102") (pin "1") (pinfunction "SCL_1") (pintype "input"))
      (node (ref "X104") (pin "53A") (pinfunction "PA8/SCL_53A") (pintype "bidirectional"))
    )
    (net (code "157") (name "SDA") (class "Default")
      (node (ref "IC102") (pin "3") (pinfunction "SDA_3") (pintype "bidirectional"))
      (node (ref "X104") (pin "54A") (pinfunction "PC9/SDA_54A") (pintype "bidirectional"))
    )
    (net (code "158") (name "SD_CLK") (class "Default")
      (node (ref "X103") (pin "5") (pinfunction "CLK_5") (pintype "input"))
      (node (ref "X104") (pin "43A") (pinfunction "PC12_43A") (pintype "bidirectional"))
    )
    (net (code "159") (name "SD_CMD") (class "Default")
      (node (ref "X103") (pin "2") (pinfunction "CMD_2") (pintype "bidirectional"))
      (node (ref "X104") (pin "40A") (pinfunction "PD2_40A") (pintype "bidirectional"))
    )
    (net (code "160") (name "SD_D0") (class "Default")
      (node (ref "X103") (pin "7") (pinfunction "DAT0_7") (pintype "bidirectional"))
      (node (ref "X104") (pin "55A") (pinfunction "PC8_55A") (pintype "bidirectional"))
    )
    (net (code "161") (name "SD_DET") (class "Default")
      (node (ref "X103") (pin "DET") (pinfunction "~{DET}_DET") (pintype "output"))
      (node (ref "X104") (pin "29A") (pinfunction "PG13/LED_GN_29A") (pintype "bidirectional"))
    )
    (net (code "162") (name "STOP_X_MAX") (class "Default")
      (node (ref "IC103") (pin "21") (pinfunction "GPA0_21") (pintype "bidirectional"))
      (node (ref "R701") (pin "1") (pinfunction "1_1") (pintype "passive"))
    )
    (net (code "163") (name "STOP_X_MIN") (class "Default")
      (node (ref "IC103") (pin "22") (pinfunction "GPA1_22") (pintype "bidirectional"))
      (node (ref "R706") (pin "1") (pinfunction "1_1") (pintype "passive"))
    )
    (net (code "164") (name "STOP_Y_MAX") (class "Default")
      (node (ref "IC103") (pin "23") (pinfunction "GPA2_23") (pintype "bidirectional"))
      (node (ref "R702") (pin "1") (pinfunction "1_1") (pintype "passive"))
    )
    (net (code "165") (name "STOP_Y_MIN") (class "Default")
      (node (ref "IC103") (pin "24") (pinfunction "GPA3_24") (pintype "bidirectional"))
      (node (ref "R707") (pin "1") (pinfunction "1_1") (pintype "passive"))
    )
    (net (code "166") (name "STOP_Z_MAX") (class "Default")
      (node (ref "IC103") (pin "25") (pinfunction "GPA4_25") (pintype "bidirectional"))
      (node (ref "R703") (pin "1") (pinfunction "1_1") (pintype "passive"))
    )
    (net (code "167") (name "STOP_Z_MIN") (class "Default")
      (node (ref "IC103") (pin "26") (pinfunction "GPA5_26") (pintype "bidirectional"))
      (node (ref "R708") (pin "1") (pinfunction "1_1") (pintype "passive"))
    )
    (net (code "168") (name "USB_SW") (class "Default")
      (node (ref "IC101") (pin "10") (pinfunction "S_10") (pintype "input"))
      (node (ref "IC103") (pin "7") (pinfunction "GPB6_7") (pintype "bidirectional"))
      (node (ref "R107") (pin "2") (pinfunction "2_2") (pintype "passive"))
    )
    (net (code "169") (name "V+") (class "Default")
      (node (ref "D501") (pin "C") (pinfunction "C_C") (pintype "passive"))
      (node (ref "D502") (pin "C") (pinfunction "C_C") (pintype "passive"))
      (node (ref "D503") (pin "C") (pinfunction "C_C") (pintype "passive"))
      (node (ref "F501") (pin "1") (pinfunction "1_1") (pintype "passive"))
      (node (ref "F501") (pin "2") (pinfunction "1_2") (pintype "passive"))
      (node (ref "LED501") (pin "C") (pinfunction "C_C") (pintype "passive"))
      (node (ref "R506") (pin "1") (pinfunction "1_1") (pintype "passive"))
      (node (ref "R507") (pin "1") (pinfunction "1_1") (pintype "passive"))
      (node (ref "R510") (pin "1") (pinfunction "1_1") (pintype "passive"))
      (node (ref "X501") (pin "2") (pinfunction "KL_2") (pintype "passive"))
      (node (ref "X502") (pin "2") (pinfunction "KL_2") (pintype "passive"))
      (node (ref "X503") (pin "2") (pinfunction "KL_2") (pintype "passive"))
    )
    (net (code "170") (name "WLAN_~{CS}") (class "Default")
      (node (ref "JP103") (pin "8") (pinfunction "8_8") (pintype "passive"))
      (node (ref "X104") (pin "14A") (pinfunction "PE5_14A") (pintype "bidirectional"))
    )
    (net (code "171") (name "WLAN_~{RST}") (class "Default")
      (node (ref "IC103") (pin "8") (pinfunction "GPB7_8") (pintype "bidirectional"))
      (node (ref "JP103") (pin "10") (pinfunction "10_10") (pintype "passive"))
    )
    (net (code "172") (name "X_DIR") (class "Default")
      (node (ref "IC301") (pin "41") (pinfunction "DIR_41") (pintype "input"))
      (node (ref "X104") (pin "33A") (pinfunction "PG9_33A") (pintype "bidirectional"))
    )
    (net (code "173") (name "X_SG_TST") (class "Default")
      (node (ref "IC104") (pin "24") (pinfunction "GPA3_24") (pintype "bidirectional"))
      (node (ref "IC301") (pin "38") (pinfunction "SG_TST_38") (pintype "output"))
    )
    (net (code "174") (name "X_STP") (class "Default")
      (node (ref "IC301") (pin "42") (pinfunction "STEP_42") (pintype "input"))
      (node (ref "X104") (pin "30B") (pinfunction "PB2/BOOT1_30B") (pintype "bidirectional"))
    )
    (net (code "175") (name "Y_DIR") (class "Default")
      (node (ref "IC303") (pin "41") (pinfunction "DIR_41") (pintype "input"))
      (node (ref "X104") (pin "52A") (pinfunction "PA9_52A") (pintype "bidirectional"))
    )
    (net (code "176") (name "Y_SG_TST") (class "Default")
      (node (ref "IC104") (pin "25") (pinfunction "GPA4_25") (pintype "bidirectional"))
      (node (ref "IC303") (pin "38") (pinfunction "SG_TST_38") (pintype "output"))
    )
    (net (code "177") (name "Y_STP") (class "Default")
      (node (ref "IC303") (pin "42") (pinfunction "STEP_42") (pintype "input"))
      (node (ref "X104") (pin "51A") (pinfunction "PA10_51A") (pintype "bidirectional"))
    )
    (net (code "178") (name "Z_DIR") (class "Default")
      (node (ref "IC302") (pin "41") (pinfunction "DIR_41") (pintype "input"))
      (node (ref "X104") (pin "62B") (pinfunction "PG2_62B") (pintype "bidirectional"))
    )
    (net (code "179") (name "Z_SG_TST") (class "Default")
      (node (ref "IC104") (pin "26") (pinfunction "GPA5_26") (pintype "bidirectional"))
      (node (ref "IC302") (pin "38") (pinfunction "SG_TST_38") (pintype "output"))
    )
    (net (code "180") (name "Z_STP") (class "Default")
      (node (ref "IC302") (pin "42") (pinfunction "STEP_42") (pintype "input"))
      (node (ref "X104") (pin "61B") (pinfunction "PG3_61B") (pintype "bidirectional"))
    )
    (net (code "181") (name "unconnected-(IC103-INTB-Pad19)") (class "Default")
      (node (ref "IC103") (pin "19") (pinfunction "INTB_19") (pintype "output"))
    )
    (net (code "182") (name "unconnected-(IC104-INTB-Pad19)") (class "Default")
      (node (ref "IC104") (pin "19") (pinfunction "INTB_19") (pintype "output"))
    )
    (net (code "183") (name "unconnected-(IC201-TST_ANA-Pad37)") (class "Default")
      (node (ref "IC201") (pin "37") (pinfunction "TST_ANA_37") (pintype "no_connect"))
    )
    (net (code "184") (name "unconnected-(IC202-TST_ANA-Pad37)") (class "Default")
      (node (ref "IC202") (pin "37") (pinfunction "TST_ANA_37") (pintype "no_connect"))
    )
    (net (code "185") (name "unconnected-(IC203-TST_ANA-Pad37)") (class "Default")
      (node (ref "IC203") (pin "37") (pinfunction "TST_ANA_37") (pintype "no_connect"))
    )
    (net (code "186") (name "unconnected-(IC301-TST_ANA-Pad37)") (class "Default")
      (node (ref "IC301") (pin "37") (pinfunction "TST_ANA_37") (pintype "no_connect"))
    )
    (net (code "187") (name "unconnected-(IC302-TST_ANA-Pad37)") (class "Default")
      (node (ref "IC302") (pin "37") (pinfunction "TST_ANA_37") (pintype "no_connect"))
    )
    (net (code "188") (name "unconnected-(IC303-TST_ANA-Pad37)") (class "Default")
      (node (ref "IC303") (pin "37") (pinfunction "TST_ANA_37") (pintype "no_connect"))
    )
    (net (code "189") (name "unconnected-(IC801-EN-Pad3)") (class "Default")
      (node (ref "IC801") (pin "3") (pinfunction "EN_3") (pintype "input"))
    )
    (net (code "190") (name "unconnected-(IC802-EN-Pad3)") (class "Default")
      (node (ref "IC802") (pin "3") (pinfunction "EN_3") (pintype "input"))
    )
    (net (code "191") (name "unconnected-(JP601-Pad3)") (class "Default")
      (node (ref "JP601") (pin "3") (pinfunction "3_3") (pintype "passive"))
    )
    (net (code "192") (name "unconnected-(JP602-Pad3)") (class "Default")
      (node (ref "JP602") (pin "3") (pinfunction "3_3") (pintype "passive"))
    )
    (net (code "193") (name "unconnected-(JP603-Pad3)") (class "Default")
      (node (ref "JP603") (pin "3") (pinfunction "3_3") (pintype "passive"))
    )
    (net (code "194") (name "unconnected-(JP604-Pad3)") (class "Default")
      (node (ref "JP604") (pin "3") (pinfunction "3_3") (pintype "passive"))
    )
    (net (code "195") (name "unconnected-(JP605-Pad3)") (class "Default")
      (node (ref "JP605") (pin "3") (pinfunction "3_3") (pintype "passive"))
    )
    (net (code "196") (name "unconnected-(X101-Pad1)") (class "Default")
      (node (ref "X101") (pin "1") (pinfunction "1_1") (pintype "passive"))
    )
    (net (code "197") (name "unconnected-(X103-DAT1-Pad8)") (class "Default")
      (node (ref "X103") (pin "8") (pinfunction "DAT1_8") (pintype "bidirectional"))
    )
    (net (code "198") (name "unconnected-(X103-DAT2-Pad9)") (class "Default")
      (node (ref "X103") (pin "9") (pinfunction "DAT2_9") (pintype "bidirectional"))
    )
    (net (code "199") (name "unconnected-(X103-~{WP}-PadWP)") (class "Default")
      (node (ref "X103") (pin "WP") (pinfunction "~{WP}_WP") (pintype "output"))
    )
    (net (code "200") (name "unconnected-(X104-3V-Pad1B)") (class "Default")
      (node (ref "X104") (pin "1B") (pinfunction "3V_1B") (pintype "output"))
    )
    (net (code "201") (name "unconnected-(X104-3V-Pad2B)") (class "Default")
      (node (ref "X104") (pin "2B") (pinfunction "3V_2B") (pintype "input"))
    )
    (net (code "202") (name "unconnected-(X104-5V-Pad1A)") (class "Default")
      (node (ref "X104") (pin "1A") (pinfunction "5V_1A") (pintype "input"))
    )
    (net (code "203") (name "unconnected-(X104-5V-Pad2A)") (class "Default")
      (node (ref "X104") (pin "2A") (pinfunction "5V_2A") (pintype "input"))
    )
    (net (code "204") (name "unconnected-(X104-BOOT0-Pad21A)") (class "Default")
      (node (ref "X104") (pin "21A") (pinfunction "BOOT0_21A") (pintype "bidirectional"))
    )
    (net (code "205") (name "unconnected-(X104-NC-Pad4B)") (class "Default")
      (node (ref "X104") (pin "4B") (pinfunction "NC_4B") (pintype "bidirectional"))
    )
    (net (code "206") (name "unconnected-(X104-PA1{slash}MEMS_INT1-Pad17B)") (class "Default")
      (node (ref "X104") (pin "17B") (pinfunction "PA1/MEMS_INT1_17B") (pintype "bidirectional"))
    )
    (net (code "207") (name "unconnected-(X104-PA2{slash}MEMS_INT2-Pad20B)") (class "Default")
      (node (ref "X104") (pin "20B") (pinfunction "PA2/MEMS_INT2_20B") (pintype "bidirectional"))
    )
    (net (code "208") (name "unconnected-(X104-PA3{slash}LCD_DB3_B5-Pad19B)") (class "Default")
      (node (ref "X104") (pin "19B") (pinfunction "PA3/LCD_DB3_B5_19B") (pintype "bidirectional"))
    )
    (net (code "209") (name "unconnected-(X104-PA4{slash}LCD_VSYNC-Pad22B)") (class "Default")
      (node (ref "X104") (pin "22B") (pinfunction "PA4/LCD_VSYNC_22B") (pintype "bidirectional"))
    )
    (net (code "210") (name "unconnected-(X104-PA6{slash}LCD_DB6_G2-Pad24B)") (class "Default")
      (node (ref "X104") (pin "24B") (pinfunction "PA6/LCD_DB6_G2_24B") (pintype "bidirectional"))
    )
    (net (code "211") (name "unconnected-(X104-PA11{slash}DB14_R4-Pad50A)") (class "Default")
      (node (ref "X104") (pin "50A") (pinfunction "PA11/DB14_R4_50A") (pintype "bidirectional"))
    )
    (net (code "212") (name "unconnected-(X104-PA12{slash}DB15{slash}R5-Pad49A)") (class "Default")
      (node (ref "X104") (pin "49A") (pinfunction "PA12/DB15/R5_49A") (pintype "bidirectional"))
    )
    (net (code "213") (name "unconnected-(X104-PA13{slash}SWDIO-Pad48A)") (class "Default")
      (node (ref "X104") (pin "48A") (pinfunction "PA13/SWDIO_48A") (pintype "bidirectional"))
    )
    (net (code "214") (name "unconnected-(X104-PA14{slash}SWCLK-Pad47A)") (class "Default")
      (node (ref "X104") (pin "47A") (pinfunction "PA14/SWCLK_47A") (pintype "bidirectional"))
    )
    (net (code "215") (name "unconnected-(X104-PA15{slash}TOUCH_INT-Pad46A)") (class "Default")
      (node (ref "X104") (pin "46A") (pinfunction "PA15/TOUCH_INT_46A") (pintype "bidirectional"))
    )
    (net (code "216") (name "unconnected-(X104-PB0{slash}LCD_DB13_R3-Pad28B)") (class "Default")
      (node (ref "X104") (pin "28B") (pinfunction "PB0/LCD_DB13_R3_28B") (pintype "bidirectional"))
    )
    (net (code "217") (name "unconnected-(X104-PB1{slash}LCD_DB16_R6-Pad27B)") (class "Default")
      (node (ref "X104") (pin "27B") (pinfunction "PB1/LCD_DB16_R6_27B") (pintype "bidirectional"))
    )
    (net (code "218") (name "unconnected-(X104-PB3{slash}SWO-Pad28A)") (class "Default")
      (node (ref "X104") (pin "28A") (pinfunction "PB3/SWO_28A") (pintype "bidirectional"))
    )
    (net (code "219") (name "unconnected-(X104-PB5{slash}SDRAM_CKE1-Pad26A)") (class "Default")
      (node (ref "X104") (pin "26A") (pinfunction "PB5/SDRAM_CKE1_26A") (pintype "bidirectional"))
    )
    (net (code "220") (name "unconnected-(X104-PB6{slash}SDNE1-Pad23A)") (class "Default")
      (node (ref "X104") (pin "23A") (pinfunction "PB6/SDNE1_23A") (pintype "bidirectional"))
    )
    (net (code "221") (name "unconnected-(X104-PB8{slash}LCD_DB4_B6-Pad19A)") (class "Default")
      (node (ref "X104") (pin "19A") (pinfunction "PB8/LCD_DB4_B6_19A") (pintype "bidirectional"))
    )
    (net (code "222") (name "unconnected-(X104-PB9{slash}LCD_DB5_B7-Pad20A)") (class "Default")
      (node (ref "X104") (pin "20A") (pinfunction "PB9/LCD_DB5_B7_20A") (pintype "bidirectional"))
    )
    (net (code "223") (name "unconnected-(X104-PB10{slash}LCD_DB8_G4-Pad48B)") (class "Default")
      (node (ref "X104") (pin "48B") (pinfunction "PB10/LCD_DB8_G4_48B") (pintype "bidirectional"))
    )
    (net (code "224") (name "unconnected-(X104-PB11{slash}LCD_DB9_G5-Pad47B)") (class "Default")
      (node (ref "X104") (pin "47B") (pinfunction "PB11/LCD_DB9_G5_47B") (pintype "bidirectional"))
    )
    (net (code "225") (name "unconnected-(X104-PC0{slash}SDRAM_~{WE}-Pad14B)") (class "Default")
      (node (ref "X104") (pin "14B") (pinfunction "PC0/SDRAM_~{WE}_14B") (pintype "bidirectional"))
    )
    (net (code "226") (name "unconnected-(X104-PC1{slash}MEMS_CS-Pad13B)") (class "Default")
      (node (ref "X104") (pin "13B") (pinfunction "PC1/MEMS_CS_13B") (pintype "bidirectional"))
    )
    (net (code "227") (name "unconnected-(X104-PC2{slash}LCD_CS-Pad16B)") (class "Default")
      (node (ref "X104") (pin "16B") (pinfunction "PC2/LCD_CS_16B") (pintype "bidirectional"))
    )
    (net (code "228") (name "unconnected-(X104-PC4_OTG_PSO-Pad26B)") (class "Default")
      (node (ref "X104") (pin "26B") (pinfunction "PC4_OTG_PSO_26B") (pintype "input"))
    )
    (net (code "229") (name "unconnected-(X104-PC5_OTG_OC-Pad25B)") (class "Default")
      (node (ref "X104") (pin "25B") (pinfunction "PC5_OTG_OC_25B") (pintype "output"))
    )
    (net (code "230") (name "unconnected-(X104-PC6{slash}LCD_HSYNC-Pad57A)") (class "Default")
      (node (ref "X104") (pin "57A") (pinfunction "PC6/LCD_HSYNC_57A") (pintype "bidirectional"))
    )
    (net (code "231") (name "unconnected-(X104-PC7{slash}LCD_DB10_G6-Pad56A)") (class "Default")
      (node (ref "X104") (pin "56A") (pinfunction "PC7/LCD_DB10_G6_56A") (pintype "bidirectional"))
    )
    (net (code "232") (name "unconnected-(X104-PC10{slash}LCD_DB12_R2-Pad45A)") (class "Default")
      (node (ref "X104") (pin "45A") (pinfunction "PC10/LCD_DB12_R2_45A") (pintype "bidirectional"))
    )
    (net (code "233") (name "unconnected-(X104-PD0{slash}SDRAM_D2-Pad42A)") (class "Default")
      (node (ref "X104") (pin "42A") (pinfunction "PD0/SDRAM_D2_42A") (pintype "bidirectional"))
    )
    (net (code "234") (name "unconnected-(X104-PD1{slash}SDRAM_D3-Pad41A)") (class "Default")
      (node (ref "X104") (pin "41A") (pinfunction "PD1/SDRAM_D3_41A") (pintype "bidirectional"))
    )
    (net (code "235") (name "unconnected-(X104-PD3{slash}LCD_DB11_G7-Pad39A)") (class "Default")
      (node (ref "X104") (pin "39A") (pinfunction "PD3/LCD_DB11_G7_39A") (pintype "bidirectional"))
    )
    (net (code "236") (name "unconnected-(X104-PD6{slash}LCD_DB0_B2-Pad36A)") (class "Default")
      (node (ref "X104") (pin "36A") (pinfunction "PD6/LCD_DB0_B2_36A") (pintype "bidirectional"))
    )
    (net (code "237") (name "unconnected-(X104-PD8{slash}SDRAM_D13-Pad54B)") (class "Default")
      (node (ref "X104") (pin "54B") (pinfunction "PD8/SDRAM_D13_54B") (pintype "bidirectional"))
    )
    (net (code "238") (name "unconnected-(X104-PD9{slash}SDRAM_D14-Pad53B)") (class "Default")
      (node (ref "X104") (pin "53B") (pinfunction "PD9/SDRAM_D14_53B") (pintype "bidirectional"))
    )
    (net (code "239") (name "unconnected-(X104-PD10{slash}SDRAM_D15-Pad56B)") (class "Default")
      (node (ref "X104") (pin "56B") (pinfunction "PD10/SDRAM_D15_56B") (pintype "bidirectional"))
    )
    (net (code "240") (name "unconnected-(X104-PD11{slash}LCD_TE-Pad55B)") (class "Default")
      (node (ref "X104") (pin "55B") (pinfunction "PD11/LCD_TE_55B") (pintype "bidirectional"))
    )
    (net (code "241") (name "unconnected-(X104-PD12{slash}LCD_RXD-Pad58B)") (class "Default")
      (node (ref "X104") (pin "58B") (pinfunction "PD12/LCD_RXD_58B") (pintype "bidirectional"))
    )
    (net (code "242") (name "unconnected-(X104-PD13{slash}LCD_WRX_DCX-Pad57B)") (class "Default")
      (node (ref "X104") (pin "57B") (pinfunction "PD13/LCD_WRX_DCX_57B") (pintype "bidirectional"))
    )
    (net (code "243") (name "unconnected-(X104-PD14{slash}SDRAM_D0-Pad60B)") (class "Default")
      (node (ref "X104") (pin "60B") (pinfunction "PD14/SDRAM_D0_60B") (pintype "bidirectional"))
    )
    (net (code "244") (name "unconnected-(X104-PD15{slash}SDRAM_D1-Pad59B)") (class "Default")
      (node (ref "X104") (pin "59B") (pinfunction "PD15/SDRAM_D1_59B") (pintype "bidirectional"))
    )
    (net (code "245") (name "unconnected-(X104-PE0{slash}SDRAM_~{BL0}-Pad17A)") (class "Default")
      (node (ref "X104") (pin "17A") (pinfunction "PE0/SDRAM_~{BL0}_17A") (pintype "bidirectional"))
    )
    (net (code "246") (name "unconnected-(X104-PE1{slash}SDRAM_~{BL1}-Pad18A)") (class "Default")
      (node (ref "X104") (pin "18A") (pinfunction "PE1/SDRAM_~{BL1}_18A") (pintype "bidirectional"))
    )
    (net (code "247") (name "unconnected-(X104-PE7{slash}SDRAM_D4-Pad37B)") (class "Default")
      (node (ref "X104") (pin "37B") (pinfunction "PE7/SDRAM_D4_37B") (pintype "bidirectional"))
    )
    (net (code "248") (name "unconnected-(X104-PE8{slash}SDRAM_D5-Pad40B)") (class "Default")
      (node (ref "X104") (pin "40B") (pinfunction "PE8/SDRAM_D5_40B") (pintype "bidirectional"))
    )
    (net (code "249") (name "unconnected-(X104-PE9{slash}SDRAM_D6-Pad39B)") (class "Default")
      (node (ref "X104") (pin "39B") (pinfunction "PE9/SDRAM_D6_39B") (pintype "bidirectional"))
    )
    (net (code "250") (name "unconnected-(X104-PE10{slash}SDRAM_D7-Pad42B)") (class "Default")
      (node (ref "X104") (pin "42B") (pinfunction "PE10/SDRAM_D7_42B") (pintype "bidirectional"))
    )
    (net (code "251") (name "unconnected-(X104-PE11{slash}SDRAM_D8-Pad41B)") (class "Default")
      (node (ref "X104") (pin "41B") (pinfunction "PE11/SDRAM_D8_41B") (pintype "bidirectional"))
    )
    (net (code "252") (name "unconnected-(X104-PE12{slash}SDRAM_D9-Pad44B)") (class "Default")
      (node (ref "X104") (pin "44B") (pinfunction "PE12/SDRAM_D9_44B") (pintype "bidirectional"))
    )
    (net (code "253") (name "unconnected-(X104-PE13{slash}SDRAM_D10-Pad43B)") (class "Default")
      (node (ref "X104") (pin "43B") (pinfunction "PE13/SDRAM_D10_43B") (pintype "bidirectional"))
    )
    (net (code "254") (name "unconnected-(X104-PE14{slash}SDRAM_D11-Pad46B)") (class "Default")
      (node (ref "X104") (pin "46B") (pinfunction "PE14/SDRAM_D11_46B") (pintype "bidirectional"))
    )
    (net (code "255") (name "unconnected-(X104-PE15{slash}SDRAM_D12-Pad45B)") (class "Default")
      (node (ref "X104") (pin "45B") (pinfunction "PE15/SDRAM_D12_45B") (pintype "bidirectional"))
    )
    (net (code "256") (name "unconnected-(X104-PF0{slash}SDRAM_A0-Pad7A)") (class "Default")
      (node (ref "X104") (pin "7A") (pinfunction "PF0/SDRAM_A0_7A") (pintype "bidirectional"))
    )
    (net (code "257") (name "unconnected-(X104-PF1{slash}SDRAM_A1-Pad8A)") (class "Default")
      (node (ref "X104") (pin "8A") (pinfunction "PF1/SDRAM_A1_8A") (pintype "bidirectional"))
    )
    (net (code "258") (name "unconnected-(X104-PF2{slash}SDRAM_A2-Pad5A)") (class "Default")
      (node (ref "X104") (pin "5A") (pinfunction "PF2/SDRAM_A2_5A") (pintype "bidirectional"))
    )
    (net (code "259") (name "unconnected-(X104-PF3{slash}SDRAM_A3-Pad6A)") (class "Default")
      (node (ref "X104") (pin "6A") (pinfunction "PF3/SDRAM_A3_6A") (pintype "bidirectional"))
    )
    (net (code "260") (name "unconnected-(X104-PF4{slash}SDRAM_A4-Pad3A)") (class "Default")
      (node (ref "X104") (pin "3A") (pinfunction "PF4/SDRAM_A4_3A") (pintype "bidirectional"))
    )
    (net (code "261") (name "unconnected-(X104-PF5{slash}SDRAM_A5-Pad4A)") (class "Default")
      (node (ref "X104") (pin "4A") (pinfunction "PF5/SDRAM_A5_4A") (pintype "bidirectional"))
    )
    (net (code "262") (name "unconnected-(X104-PF10{slash}LCD_ENB_DE-Pad7B)") (class "Default")
      (node (ref "X104") (pin "7B") (pinfunction "PF10/LCD_ENB_DE_7B") (pintype "bidirectional"))
    )
    (net (code "263") (name "unconnected-(X104-PF11{slash}SDRAM~{RAS}-Pad32B)") (class "Default")
      (node (ref "X104") (pin "32B") (pinfunction "PF11/SDRAM~{RAS}_32B") (pintype "bidirectional"))
    )
    (net (code "264") (name "unconnected-(X104-PF12{slash}SDRAM_A6-Pad31B)") (class "Default")
      (node (ref "X104") (pin "31B") (pinfunction "PF12/SDRAM_A6_31B") (pintype "bidirectional"))
    )
    (net (code "265") (name "unconnected-(X104-PF13{slash}SDRAM_A7-Pad34B)") (class "Default")
      (node (ref "X104") (pin "34B") (pinfunction "PF13/SDRAM_A7_34B") (pintype "bidirectional"))
    )
    (net (code "266") (name "unconnected-(X104-PF14{slash}SDRAM_A8-Pad33B)") (class "Default")
      (node (ref "X104") (pin "33B") (pinfunction "PF14/SDRAM_A8_33B") (pintype "bidirectional"))
    )
    (net (code "267") (name "unconnected-(X104-PF15{slash}SDRAM_A9-Pad36B)") (class "Default")
      (node (ref "X104") (pin "36B") (pinfunction "PF15/SDRAM_A9_36B") (pintype "bidirectional"))
    )
    (net (code "268") (name "unconnected-(X104-PG0{slash}SDRAM_A10-Pad35B)") (class "Default")
      (node (ref "X104") (pin "35B") (pinfunction "PG0/SDRAM_A10_35B") (pintype "bidirectional"))
    )
    (net (code "269") (name "unconnected-(X104-PG1{slash}SDRAM_A11-Pad38B)") (class "Default")
      (node (ref "X104") (pin "38B") (pinfunction "PG1/SDRAM_A11_38B") (pintype "bidirectional"))
    )
    (net (code "270") (name "unconnected-(X104-PG4{slash}SDRAM_BA0-Pad62A)") (class "Default")
      (node (ref "X104") (pin "62A") (pinfunction "PG4/SDRAM_BA0_62A") (pintype "bidirectional"))
    )
    (net (code "271") (name "unconnected-(X104-PG5{slash}SDRAM_BA1-Pad61A)") (class "Default")
      (node (ref "X104") (pin "61A") (pinfunction "PG5/SDRAM_BA1_61A") (pintype "bidirectional"))
    )
    (net (code "272") (name "unconnected-(X104-PG6{slash}LCD_DB17_R7-Pad60A)") (class "Default")
      (node (ref "X104") (pin "60A") (pinfunction "PG6/LCD_DB17_R7_60A") (pintype "bidirectional"))
    )
    (net (code "273") (name "unconnected-(X104-PG7{slash}LCD_DOTCLK_CLK-Pad59A)") (class "Default")
      (node (ref "X104") (pin "59A") (pinfunction "PG7/LCD_DOTCLK_CLK_59A") (pintype "bidirectional"))
    )
    (net (code "274") (name "unconnected-(X104-PG8{slash}SDRAM_CLK-Pad58A)") (class "Default")
      (node (ref "X104") (pin "58A") (pinfunction "PG8/SDRAM_CLK_58A") (pintype "bidirectional"))
    )
    (net (code "275") (name "unconnected-(X104-PG10{slash}LCD_DB7_G3-Pad34A)") (class "Default")
      (node (ref "X104") (pin "34A") (pinfunction "PG10/LCD_DB7_G3_34A") (pintype "bidirectional"))
    )
    (net (code "276") (name "unconnected-(X104-PG11{slash}LCD_DB1_B3-Pad31A)") (class "Default")
      (node (ref "X104") (pin "31A") (pinfunction "PG11/LCD_DB1_B3_31A") (pintype "bidirectional"))
    )
    (net (code "277") (name "unconnected-(X104-PG12{slash}LCD_DB2_B4-Pad32A)") (class "Default")
      (node (ref "X104") (pin "32A") (pinfunction "PG12/LCD_DB2_B4_32A") (pintype "bidirectional"))
    )
    (net (code "278") (name "unconnected-(X104-PG15{slash}SDRAM_~{CAS}-Pad27A)") (class "Default")
      (node (ref "X104") (pin "27A") (pinfunction "PG15/SDRAM_~{CAS}_27A") (pintype "bidirectional"))
    )
    (net (code "279") (name "unconnected-(X104-PH0{slash}OSC_IN-Pad10B)") (class "Default")
      (node (ref "X104") (pin "10B") (pinfunction "PH0/OSC_IN_10B") (pintype "bidirectional"))
    )
    (net (code "280") (name "unconnected-(X104-PH1{slash}OSC_OUT-Pad9B)") (class "Default")
      (node (ref "X104") (pin "9B") (pinfunction "PH1/OSC_OUT_9B") (pintype "bidirectional"))
    )
    (net (code "281") (name "unconnected-(X104-~{RST}-Pad12B)") (class "Default")
      (node (ref "X104") (pin "12B") (pinfunction "~{RST}_12B") (pintype "bidirectional"))
    )
    (net (code "282") (name "~{CS_PORTEX}") (class "Default")
      (node (ref "IC103") (pin "11") (pinfunction "~{CS}_11") (pintype "input"))
      (node (ref "IC104") (pin "11") (pinfunction "~{CS}_11") (pintype "input"))
      (node (ref "X104") (pin "11A") (pinfunction "PE6_11A") (pintype "bidirectional"))
    )
    (net (code "283") (name "~{ENB_EXTRUDERS}") (class "Default")
      (node (ref "IC104") (pin "7") (pinfunction "GPB6_7") (pintype "bidirectional"))
      (node (ref "IC201") (pin "19") (pinfunction "~{EN}_19") (pintype "input"))
      (node (ref "IC202") (pin "19") (pinfunction "~{EN}_19") (pintype "input"))
      (node (ref "IC203") (pin "19") (pinfunction "~{EN}_19") (pintype "input"))
    )
    (net (code "284") (name "~{SPI_EN_E0}") (class "Default")
      (node (ref "IC104") (pin "1") (pinfunction "GPB0_1") (pintype "bidirectional"))
      (node (ref "IC201") (pin "18") (pinfunction "~{CS}_18") (pintype "input"))
    )
    (net (code "285") (name "~{SPI_EN_E1}") (class "Default")
      (node (ref "IC104") (pin "2") (pinfunction "GPB1_2") (pintype "bidirectional"))
      (node (ref "IC203") (pin "18") (pinfunction "~{CS}_18") (pintype "input"))
    )
    (net (code "286") (name "~{SPI_EN_E2}") (class "Default")
      (node (ref "IC104") (pin "3") (pinfunction "GPB2_3") (pintype "bidirectional"))
      (node (ref "IC202") (pin "18") (pinfunction "~{CS}_18") (pintype "input"))
    )
    (net (code "287") (name "~{SPI_EN_X}") (class "Default")
      (node (ref "IC104") (pin "4") (pinfunction "GPB3_4") (pintype "bidirectional"))
      (node (ref "IC301") (pin "18") (pinfunction "~{CS}_18") (pintype "input"))
    )
    (net (code "288") (name "~{SPI_EN_Y}") (class "Default")
      (node (ref "IC104") (pin "5") (pinfunction "GPB4_5") (pintype "bidirectional"))
      (node (ref "IC303") (pin "18") (pinfunction "~{CS}_18") (pintype "input"))
    )
    (net (code "289") (name "~{SPI_EN_Z}") (class "Default")
      (node (ref "IC104") (pin "6") (pinfunction "GPB5_6") (pintype "bidirectional"))
      (node (ref "IC302") (pin "18") (pinfunction "~{CS}_18") (pintype "input"))
    )
    (net (code "290") (name "~{USB_OE}") (class "Default")
      (node (ref "IC101") (pin "8") (pinfunction "~{OE}_8") (pintype "input"))
      (node (ref "IC103") (pin "6") (pinfunction "GPB5_6") (pintype "bidirectional"))
    )
    (net (code "291") (name "~{X_Y_Z_EN}") (class "Default")
      (node (ref "IC104") (pin "8") (pinfunction "GPB7_8") (pintype "bidirectional"))
      (node (ref "IC301") (pin "19") (pinfunction "~{EN}_19") (pintype "input"))
      (node (ref "IC302") (pin "19") (pinfunction "~{EN}_19") (pintype "input"))
      (node (ref "IC303") (pin "19") (pinfunction "~{EN}_19") (pintype "input"))
    )
  )
)
